# ME461_F28379D.net
KiCad netlist of a schematic drawn in EAGLE
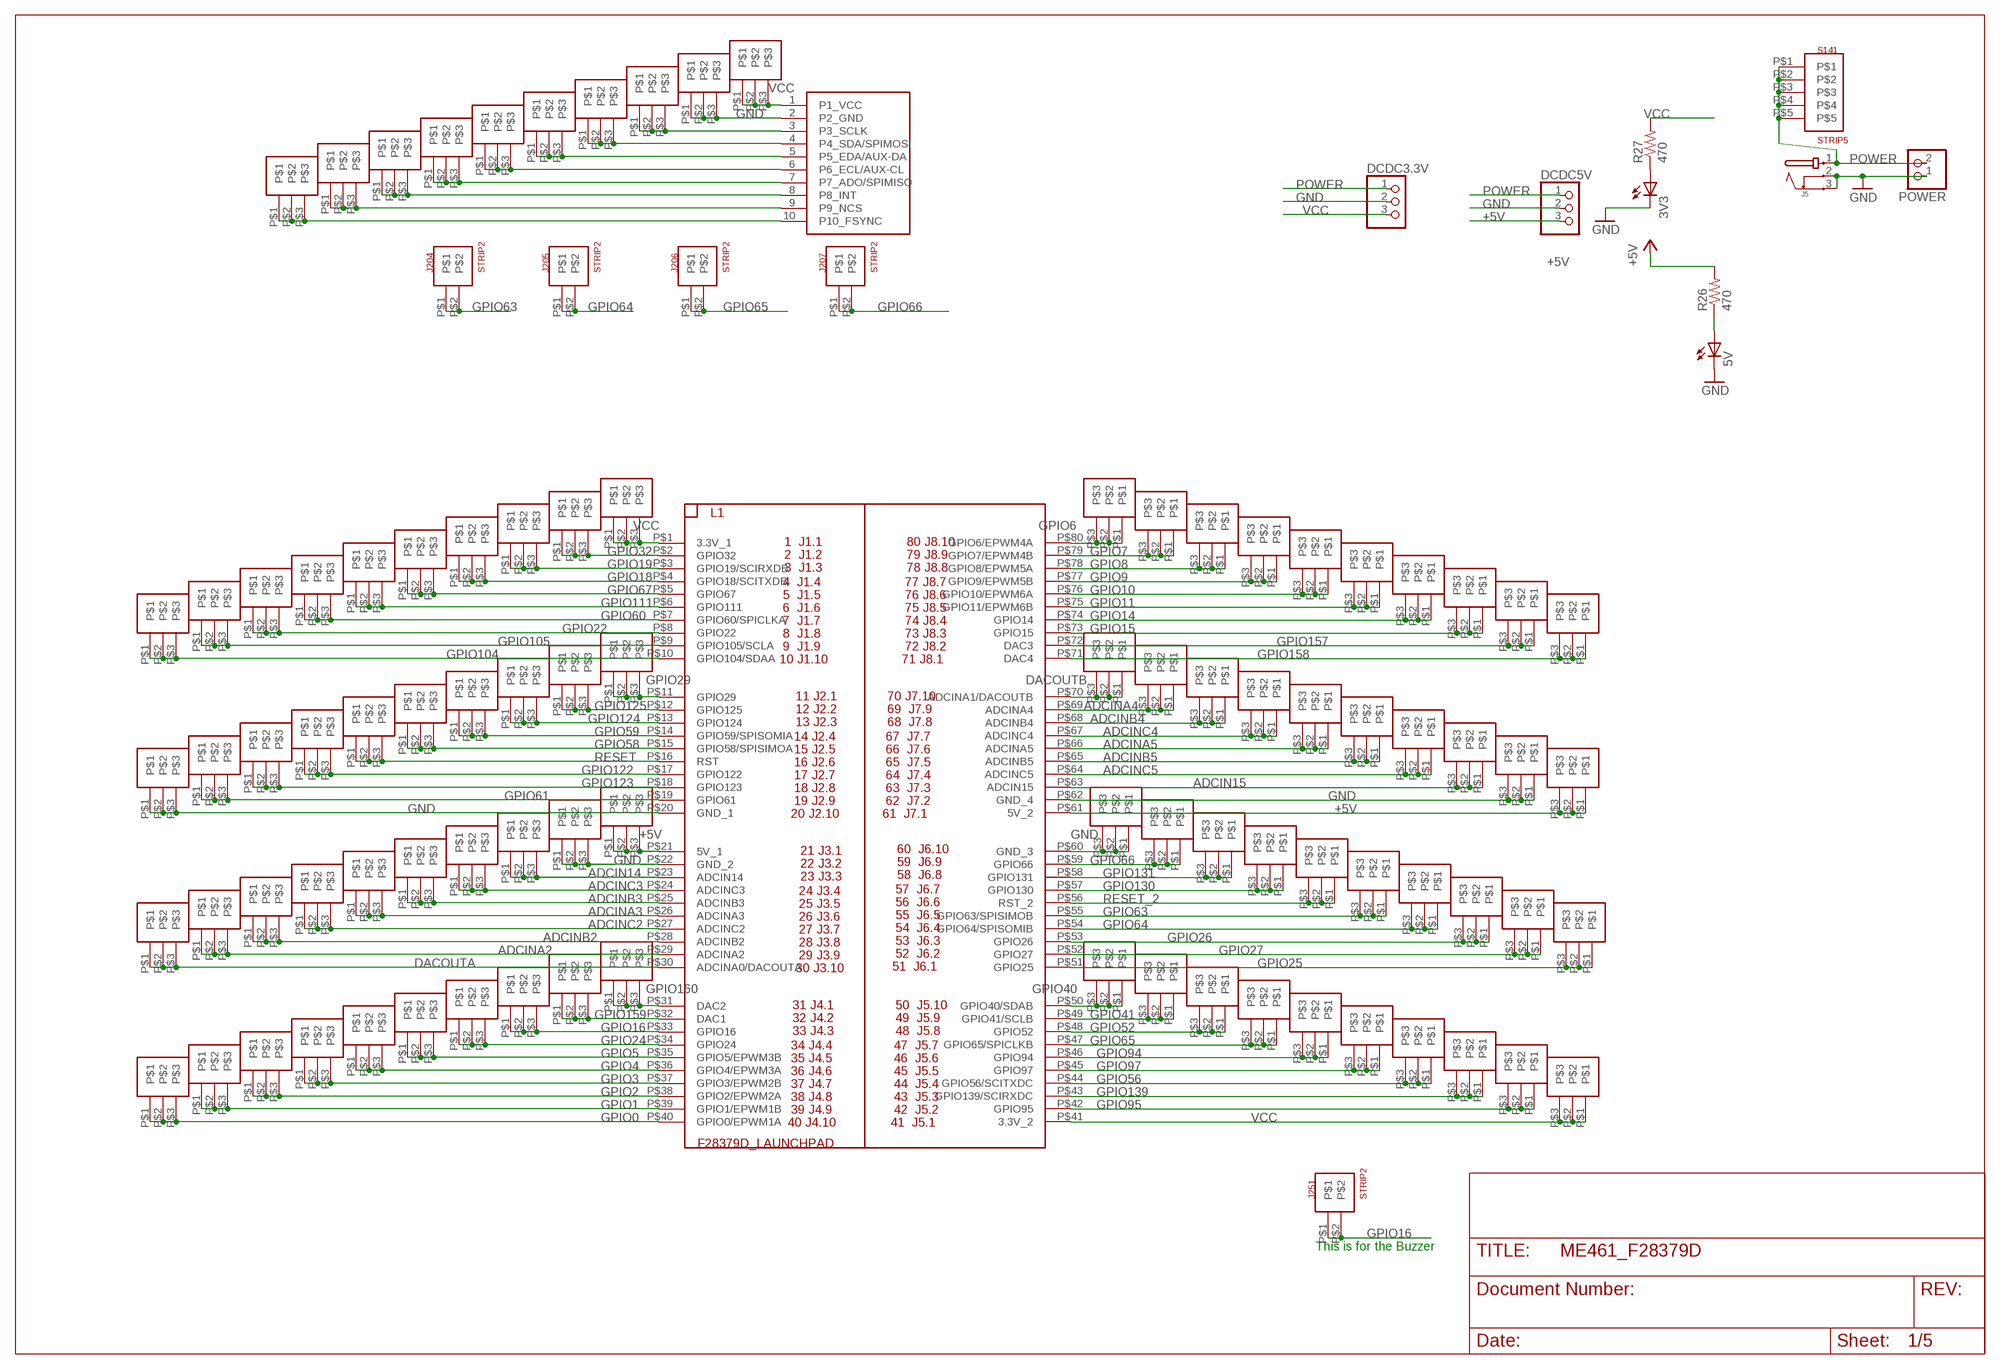
[diagram p0: schematic, sheet 1]
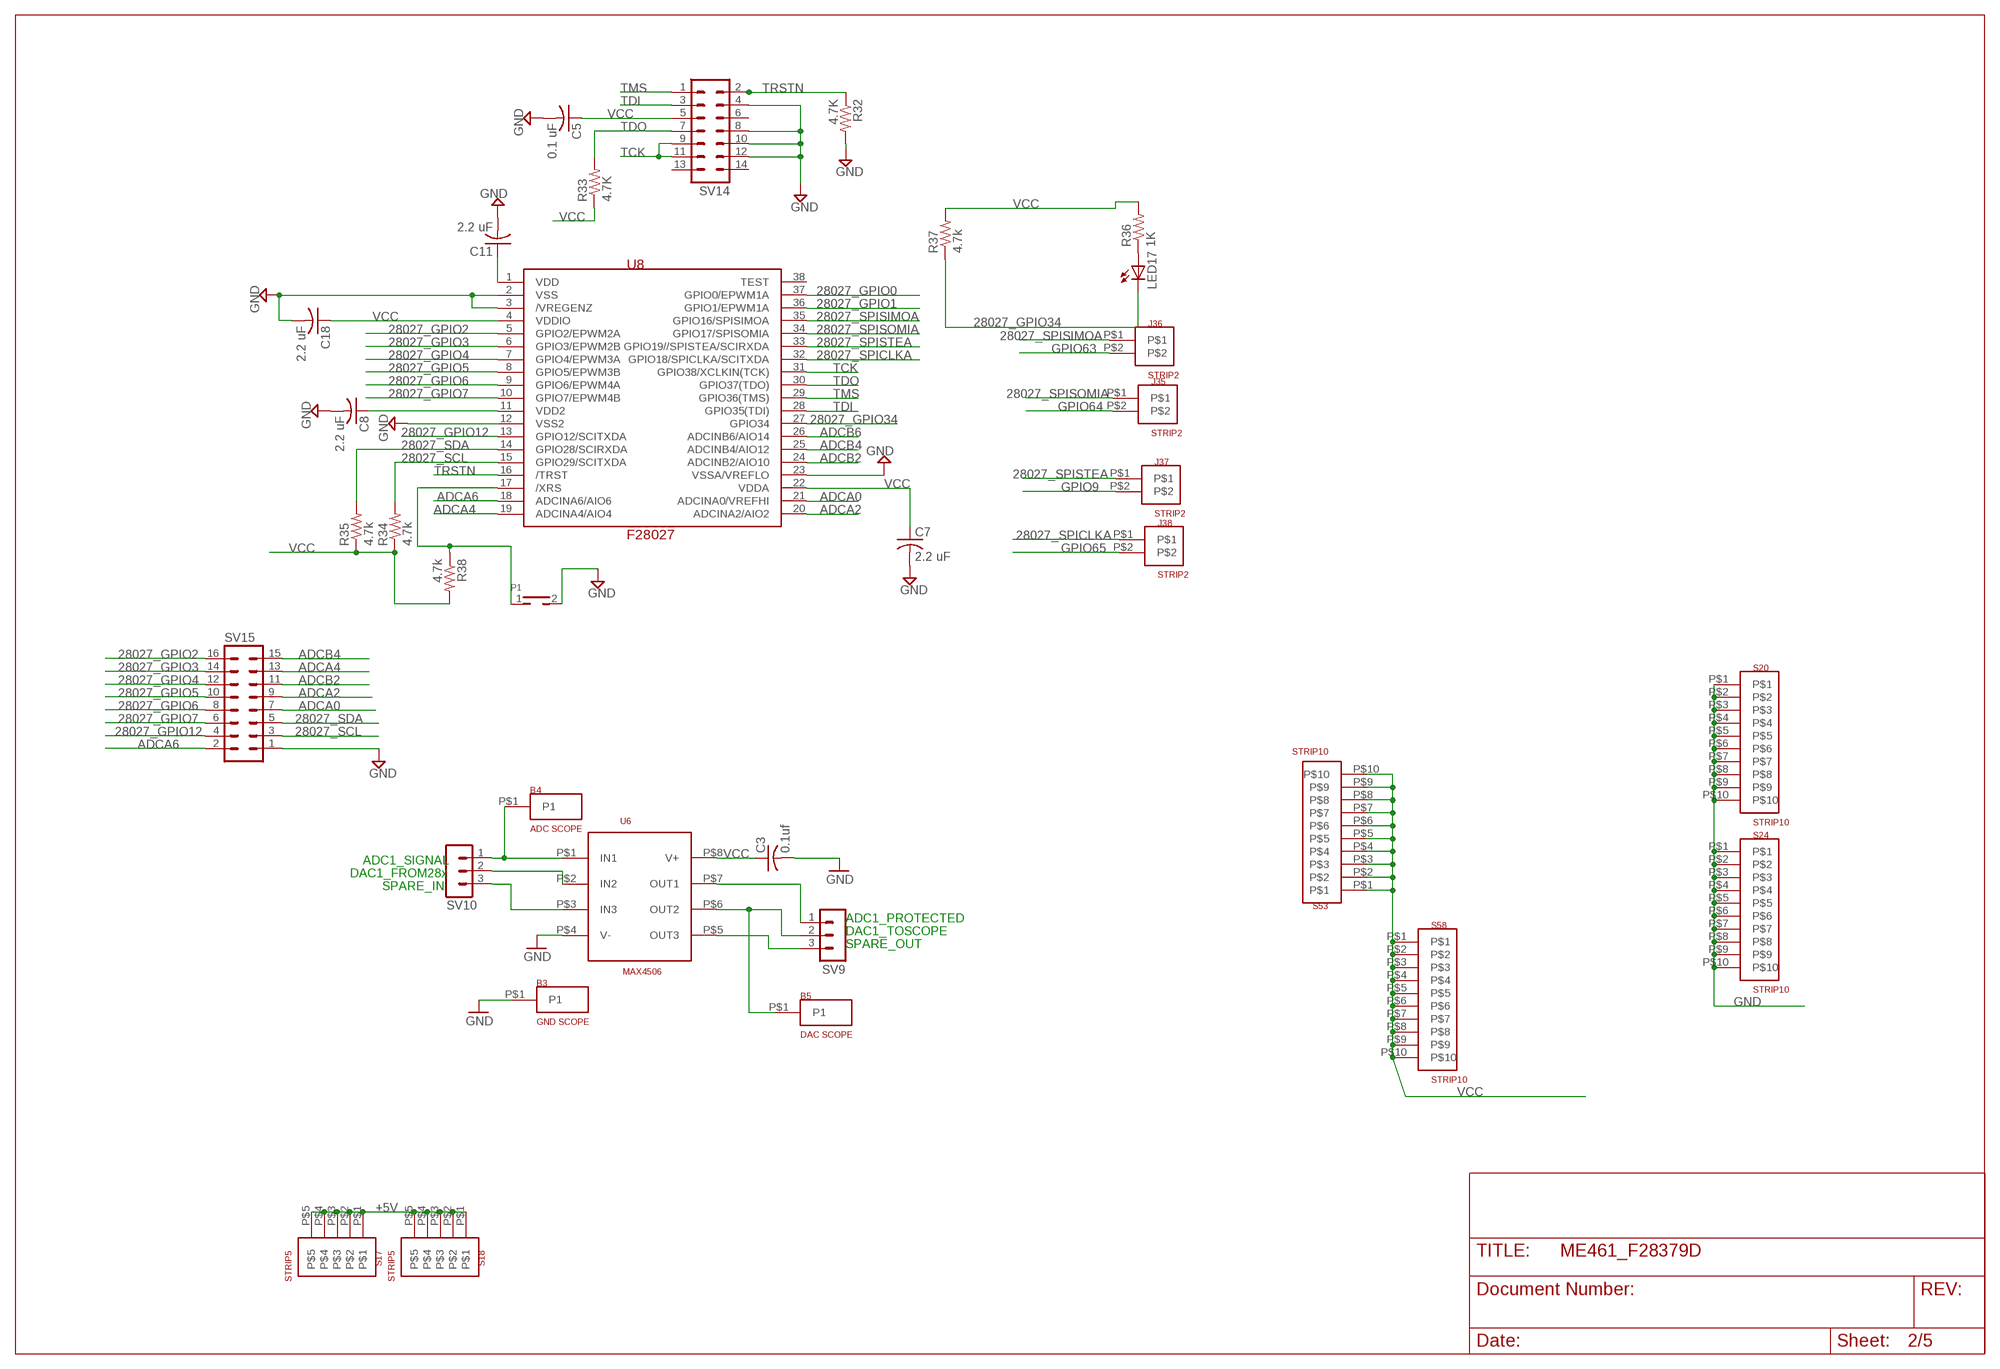
[diagram p1: schematic, sheet 2]
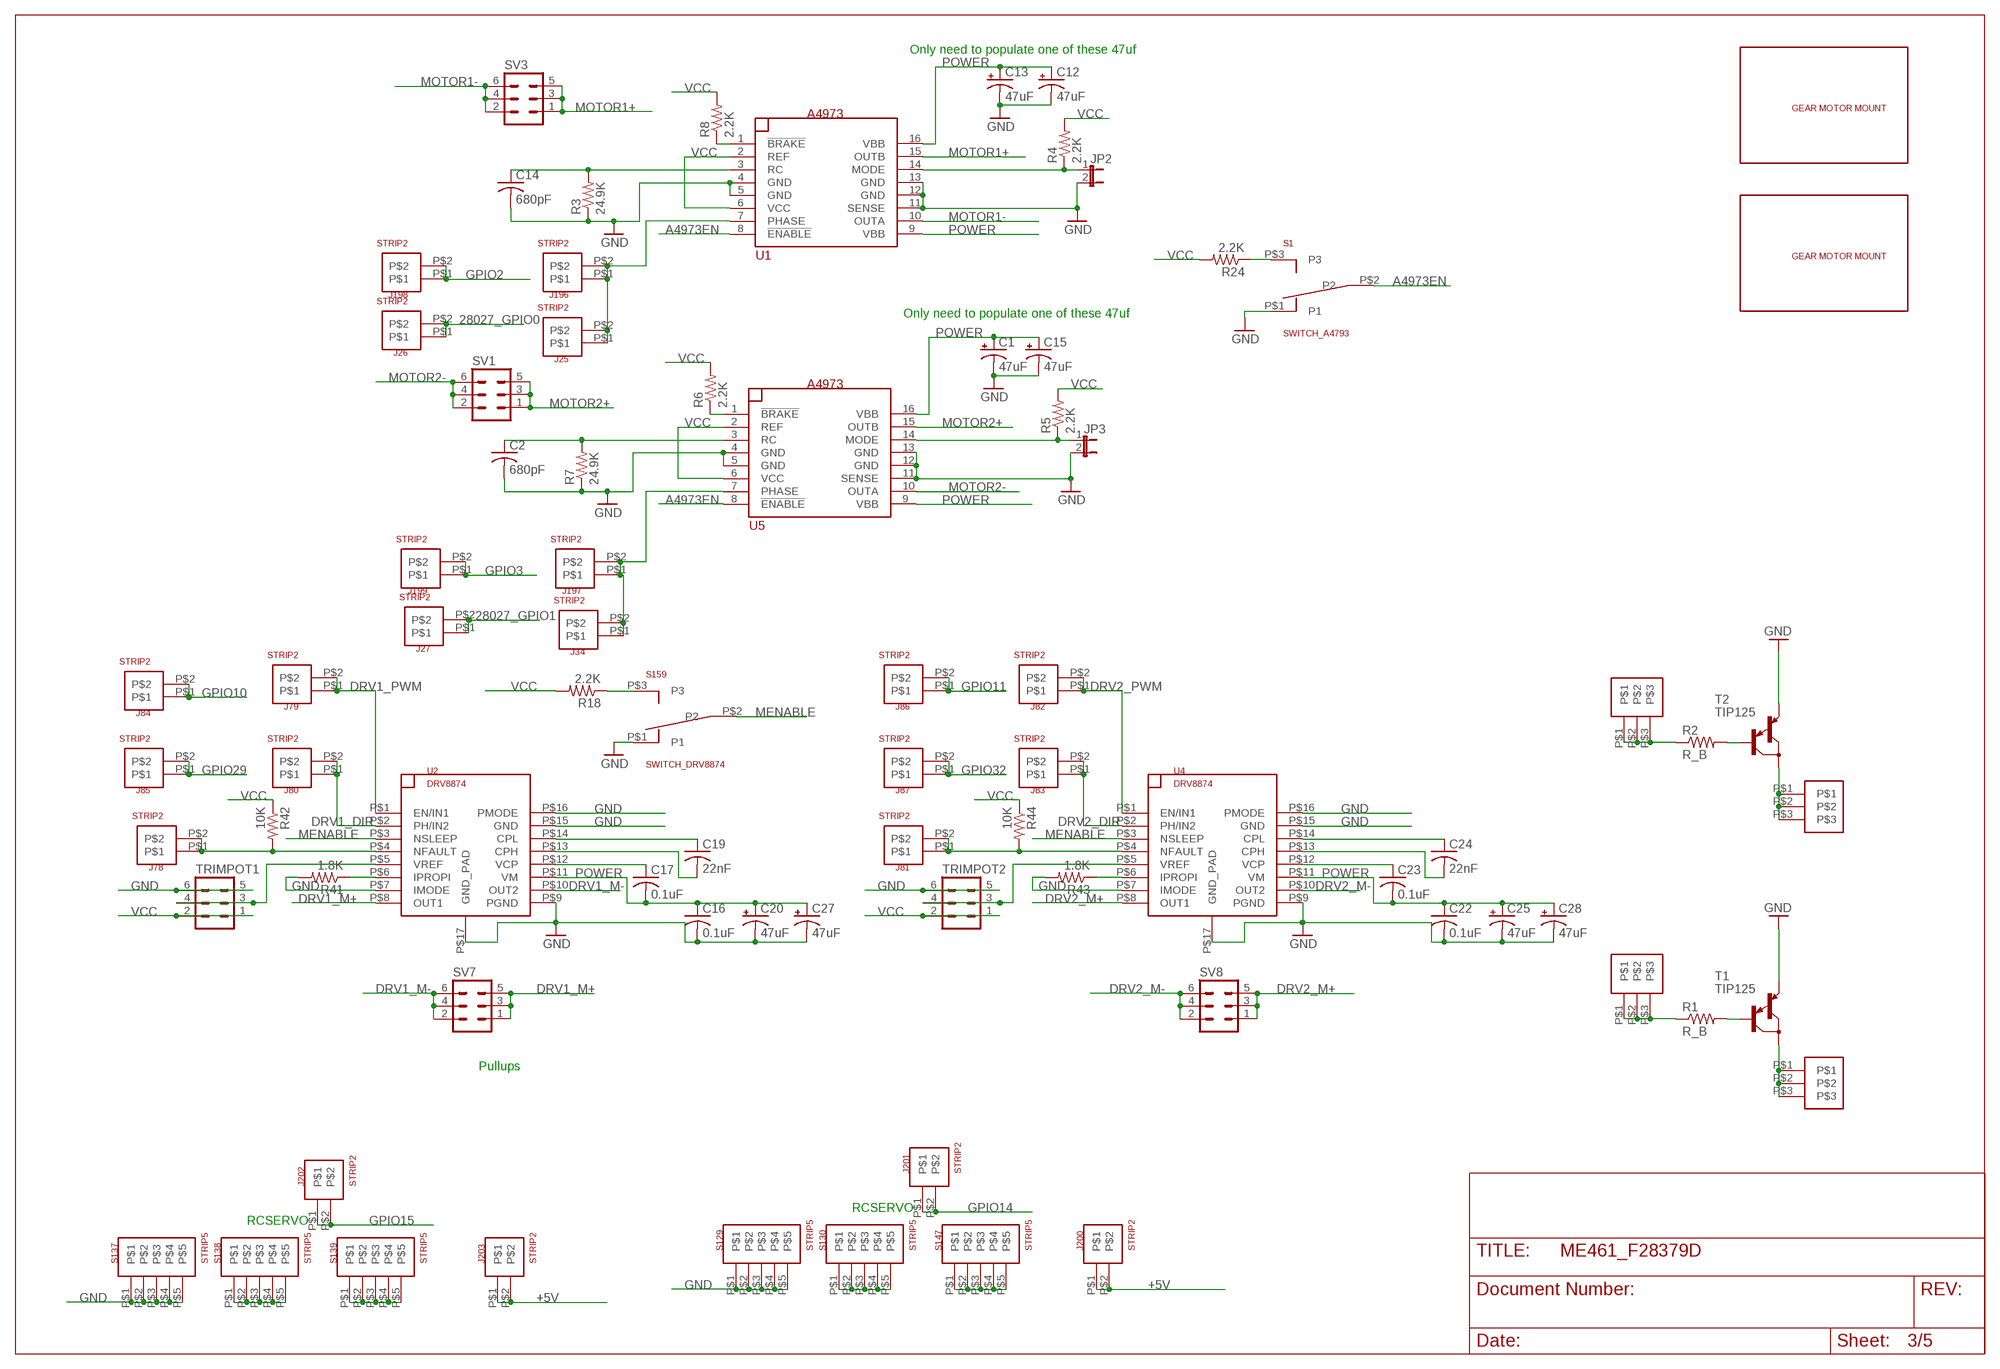
[diagram p2: schematic, sheet 3]
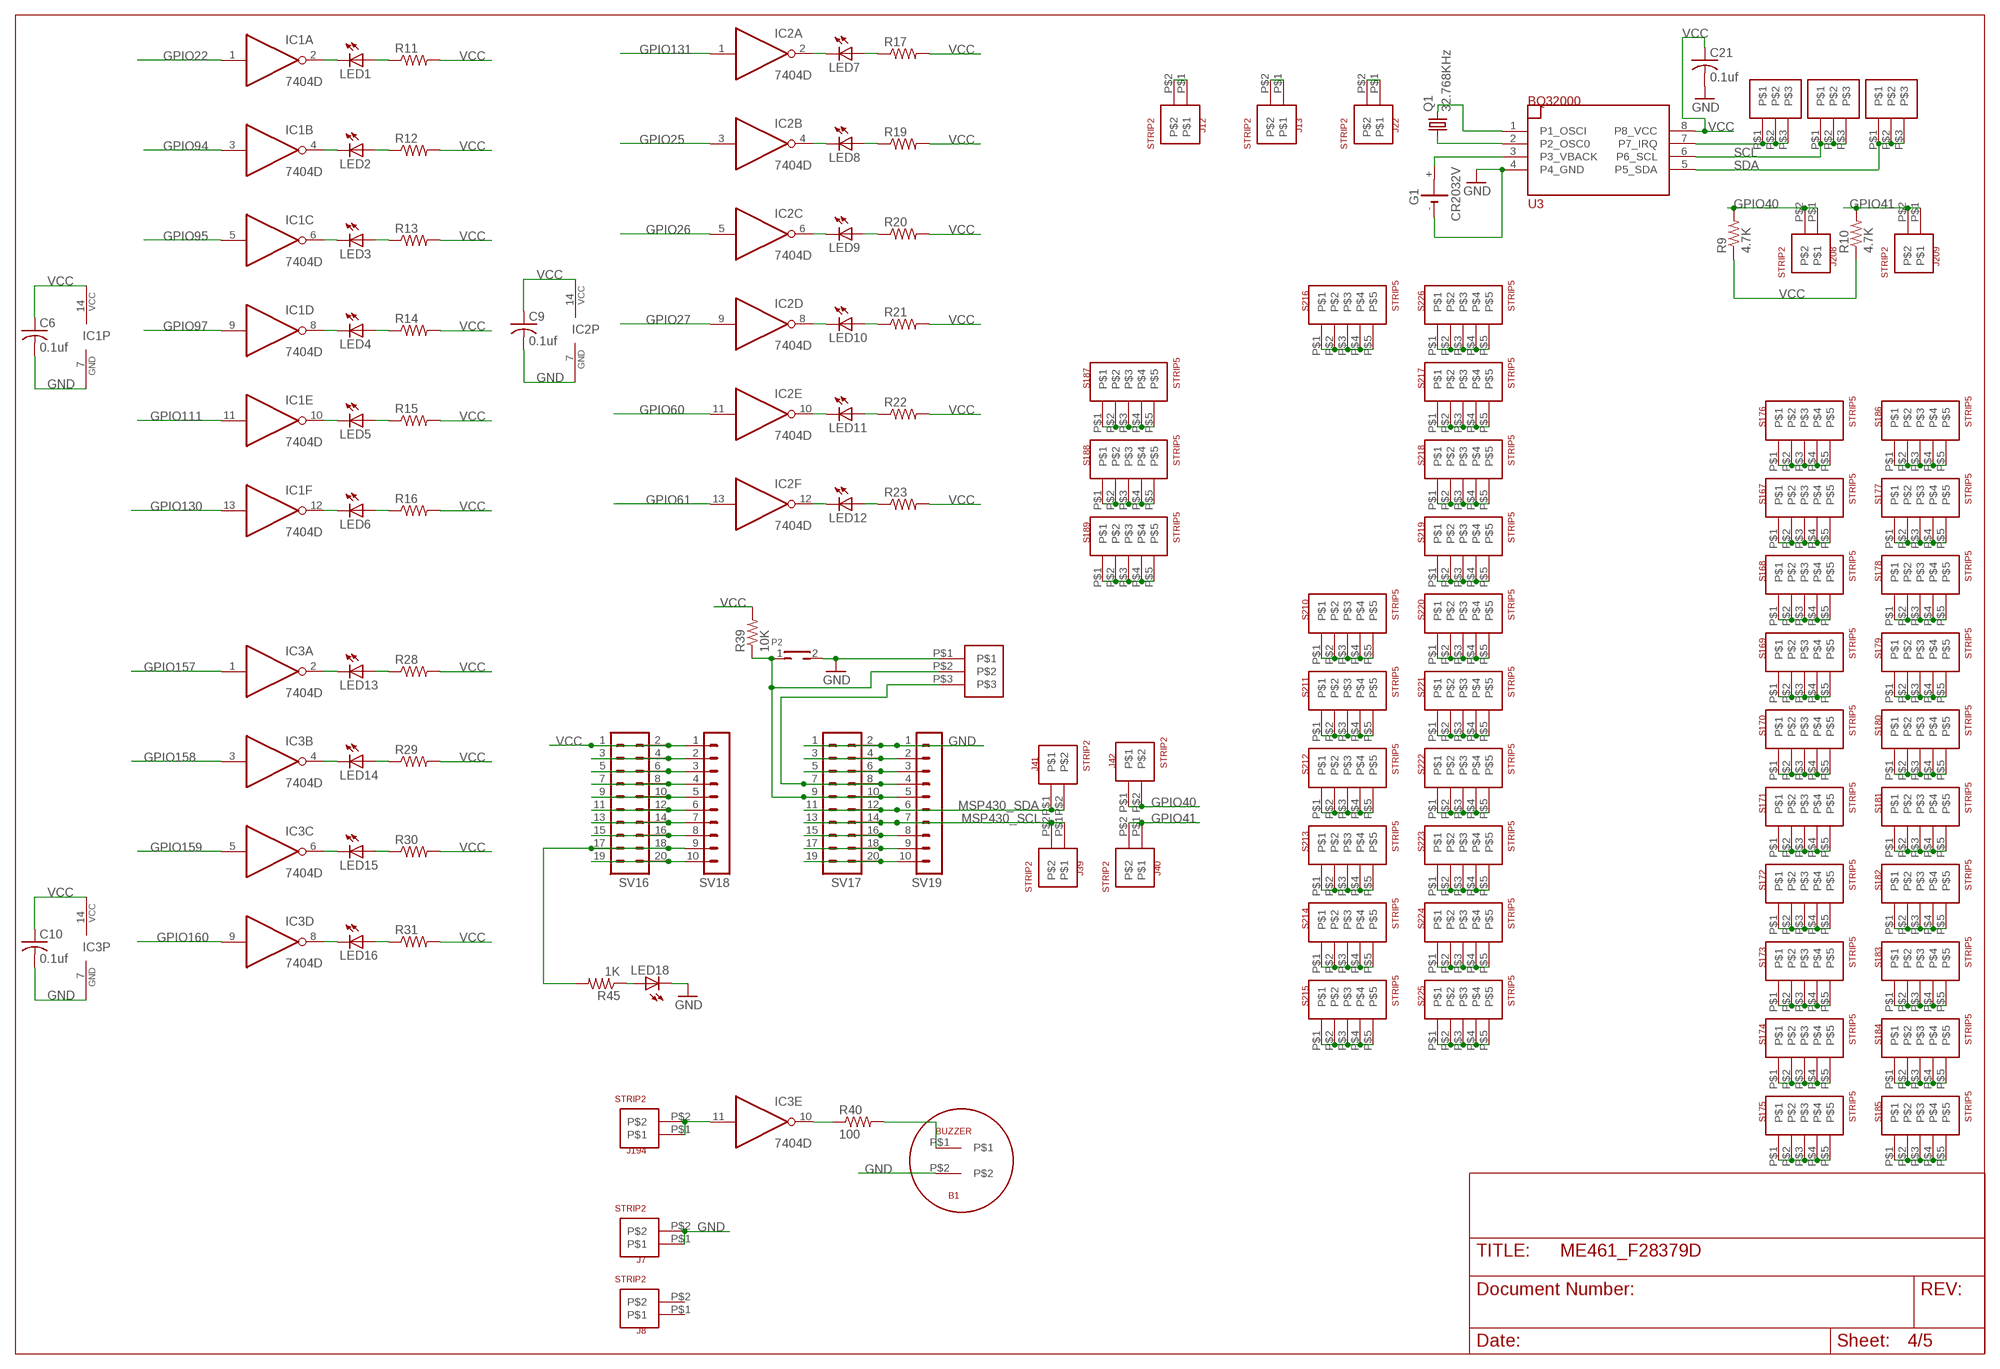
[diagram p3: schematic, sheet 4]
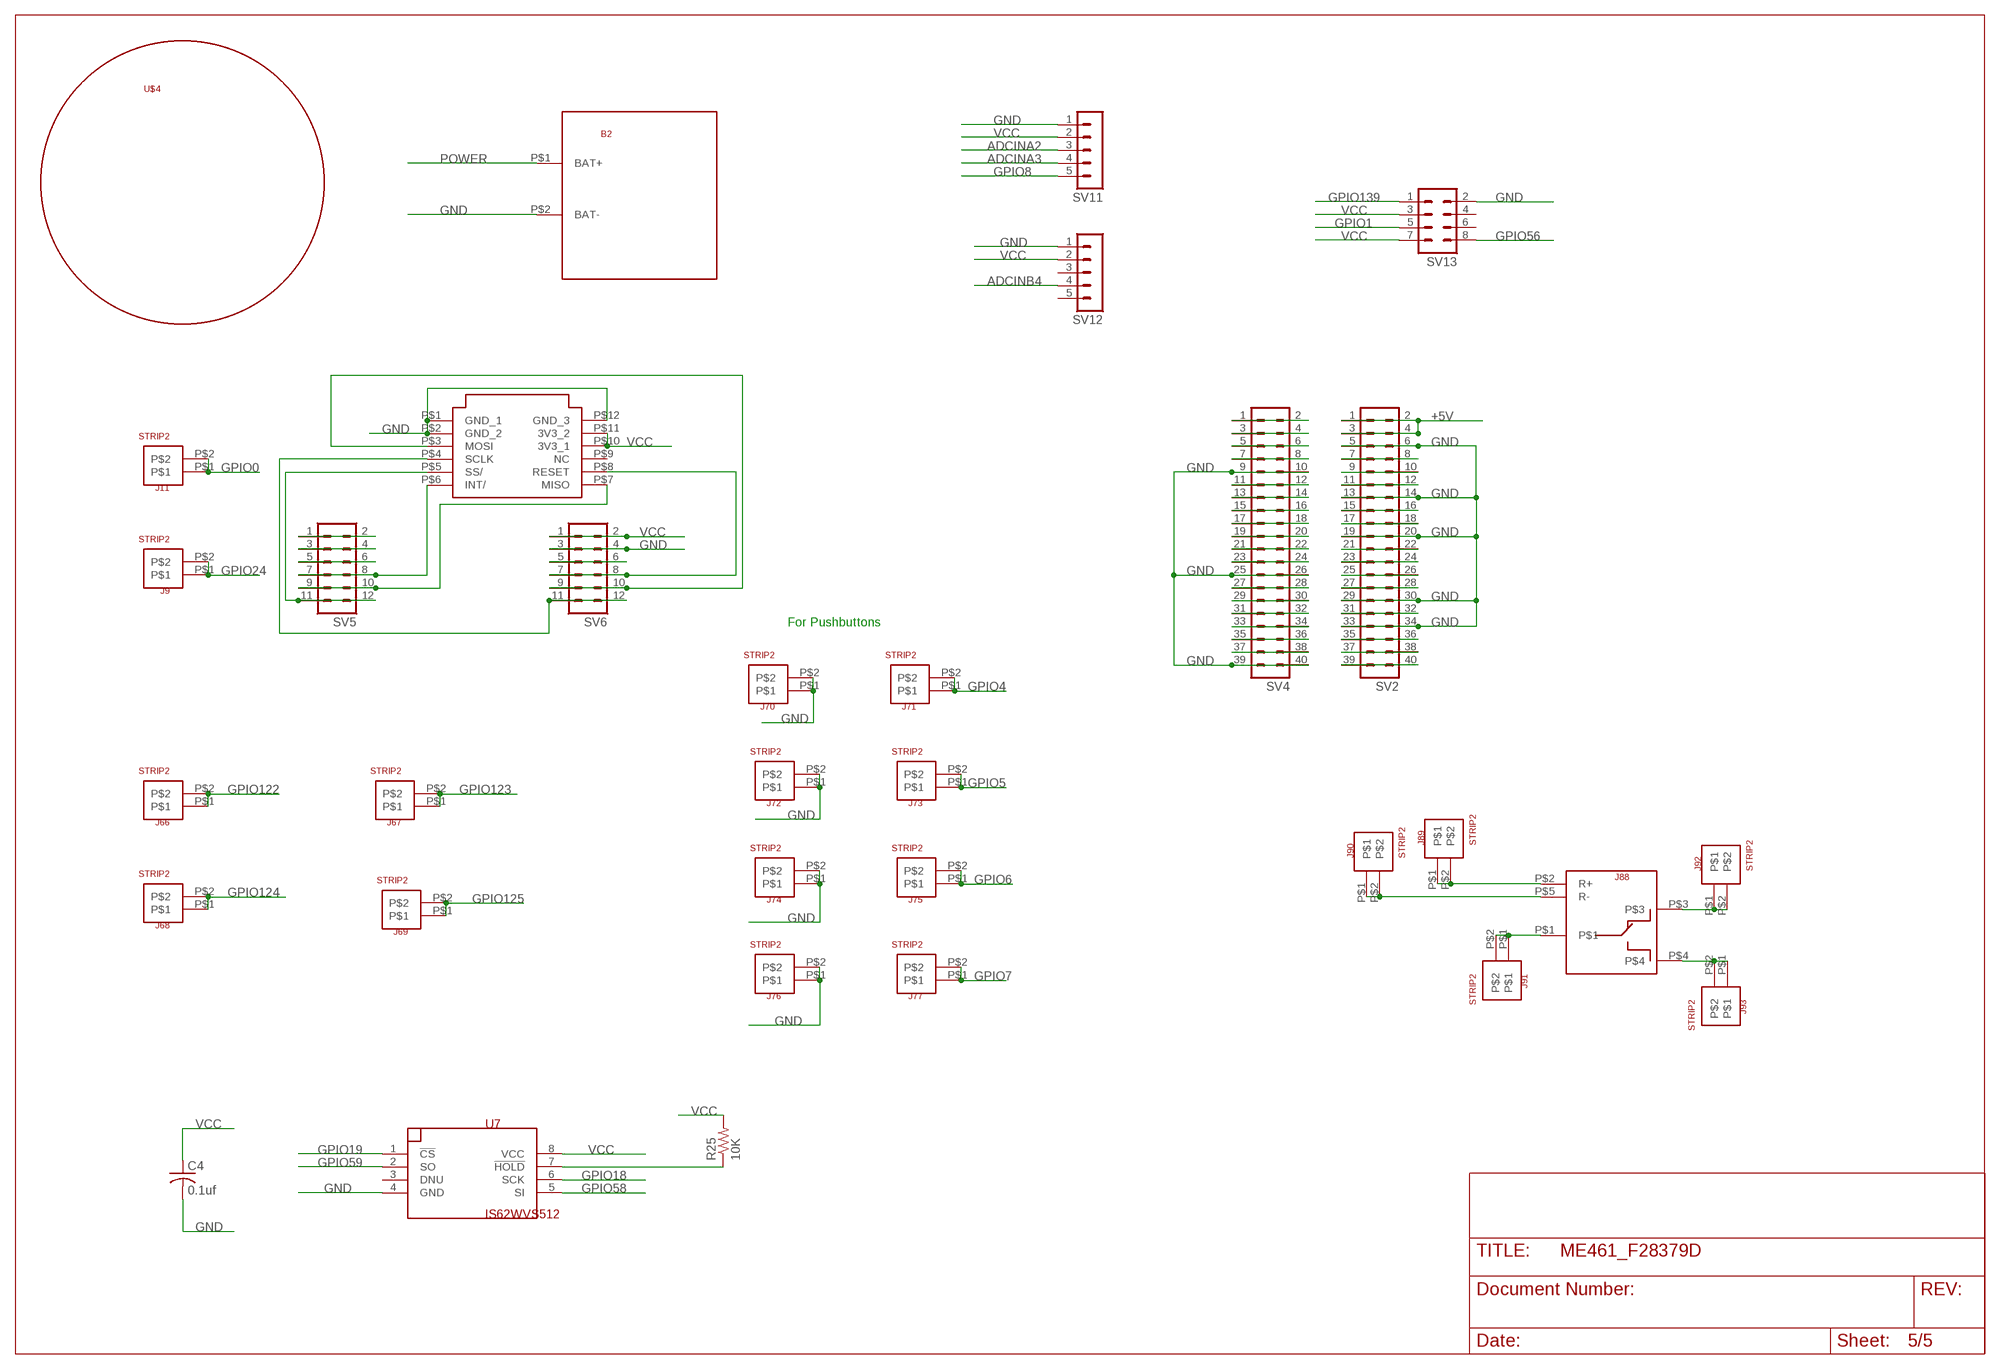
[diagram p4: schematic, sheet 5]

(export (version "E")
  (design (tool "Eeschema 10.0.6"))
  (components
    (comp (ref "B2")
      (value "BATTERY_4AA_HOLDER")
      (footprint "eagle-import:BATTERY_4AA_HOLDER")
      (libsource (lib "eagle-import") (part "BATTERY_4AA_HOLDER"))
    )
    (comp (ref "C4")
      (value "0.1uf")
      (footprint "eagle-import:C1206")
      (libsource (lib "eagle-import") (part "C-USC1206"))
    )
    (comp (ref "ETH1")
      (value "USR_ES1_W5500")
      (footprint "eagle-import:USR_ES1_W5500")
      (libsource (lib "eagle-import") (part "USR_ES1_W5500"))
    )
    (comp (ref "J9")
      (value "STRIP2")
      (footprint "eagle-import:STRIP2")
      (libsource (lib "eagle-import") (part "STRIP2"))
    )
    (comp (ref "J11")
      (value "STRIP2")
      (footprint "eagle-import:STRIP2")
      (libsource (lib "eagle-import") (part "STRIP2"))
    )
    (comp (ref "J66")
      (value "STRIP2")
      (footprint "eagle-import:STRIP2")
      (libsource (lib "eagle-import") (part "STRIP2"))
    )
    (comp (ref "J67")
      (value "STRIP2")
      (footprint "eagle-import:STRIP2")
      (libsource (lib "eagle-import") (part "STRIP2"))
    )
    (comp (ref "J68")
      (value "STRIP2")
      (footprint "eagle-import:STRIP2")
      (libsource (lib "eagle-import") (part "STRIP2"))
    )
    (comp (ref "J69")
      (value "STRIP2")
      (footprint "eagle-import:STRIP2")
      (libsource (lib "eagle-import") (part "STRIP2"))
    )
    (comp (ref "J70")
      (value "STRIP2")
      (footprint "eagle-import:STRIP2")
      (libsource (lib "eagle-import") (part "STRIP2"))
    )
    (comp (ref "J71")
      (value "STRIP2")
      (footprint "eagle-import:STRIP2")
      (libsource (lib "eagle-import") (part "STRIP2"))
    )
    (comp (ref "J72")
      (value "STRIP2")
      (footprint "eagle-import:STRIP2")
      (libsource (lib "eagle-import") (part "STRIP2"))
    )
    (comp (ref "J73")
      (value "STRIP2")
      (footprint "eagle-import:STRIP2")
      (libsource (lib "eagle-import") (part "STRIP2"))
    )
    (comp (ref "J74")
      (value "STRIP2")
      (footprint "eagle-import:STRIP2")
      (libsource (lib "eagle-import") (part "STRIP2"))
    )
    (comp (ref "J75")
      (value "STRIP2")
      (footprint "eagle-import:STRIP2")
      (libsource (lib "eagle-import") (part "STRIP2"))
    )
    (comp (ref "J76")
      (value "STRIP2")
      (footprint "eagle-import:STRIP2")
      (libsource (lib "eagle-import") (part "STRIP2"))
    )
    (comp (ref "J77")
      (value "STRIP2")
      (footprint "eagle-import:STRIP2")
      (libsource (lib "eagle-import") (part "STRIP2"))
    )
    (comp (ref "J88")
      (value "RELAY_JQC-3F_5V")
      (footprint "eagle-import:RELAY_JQC-3F_5V")
      (libsource (lib "eagle-import") (part "RELAY_JQC-3F_5V"))
    )
    (comp (ref "J89")
      (value "STRIP2")
      (footprint "eagle-import:STRIP2")
      (libsource (lib "eagle-import") (part "STRIP2"))
    )
    (comp (ref "J90")
      (value "STRIP2")
      (footprint "eagle-import:STRIP2")
      (libsource (lib "eagle-import") (part "STRIP2"))
    )
    (comp (ref "J91")
      (value "STRIP2")
      (footprint "eagle-import:STRIP2")
      (libsource (lib "eagle-import") (part "STRIP2"))
    )
    (comp (ref "J92")
      (value "STRIP2")
      (footprint "eagle-import:STRIP2")
      (libsource (lib "eagle-import") (part "STRIP2"))
    )
    (comp (ref "J93")
      (value "STRIP2")
      (footprint "eagle-import:STRIP2")
      (libsource (lib "eagle-import") (part "STRIP2"))
    )
    (comp (ref "R25")
      (value "10K")
      (footprint "eagle-import:M1206")
      (libsource (lib "eagle-import") (part "R-US_M1206"))
    )
    (comp (ref "SV2")
      (value "MA20-2")
      (footprint "eagle-import:MA20-2")
      (libsource (lib "eagle-import") (part "MA20-2"))
    )
    (comp (ref "SV4")
      (value "MA20-2")
      (footprint "eagle-import:MA20-2")
      (libsource (lib "eagle-import") (part "MA20-2"))
    )
    (comp (ref "SV5")
      (value "MA06-2")
      (footprint "eagle-import:MA06-2")
      (libsource (lib "eagle-import") (part "MA06-2"))
    )
    (comp (ref "SV6")
      (value "MA06-2")
      (footprint "eagle-import:MA06-2")
      (libsource (lib "eagle-import") (part "MA06-2"))
    )
    (comp (ref "SV11")
      (value "MA05-1")
      (footprint "eagle-import:MA05-1")
      (libsource (lib "eagle-import") (part "MA05-1"))
    )
    (comp (ref "SV12")
      (value "MA05-1")
      (footprint "eagle-import:MA05-1")
      (libsource (lib "eagle-import") (part "MA05-1"))
    )
    (comp (ref "SV13")
      (value "MA04-2")
      (footprint "eagle-import:MA04-2")
      (libsource (lib "eagle-import") (part "MA04-2"))
    )
    (comp (ref "U$4")
      (value "CASTERWHEEL")
      (footprint "eagle-import:CASTERWHEEL")
      (libsource (lib "eagle-import") (part "CASTERWHEEL"))
    )
    (comp (ref "U7")
      (value "IS62WVS512")
      (footprint "eagle-import:SO08")
      (libsource (lib "eagle-import") (part "IS62WVS512"))
    )
    (comp (ref "3V3")
      (value "LEDCHIPLED_1206")
      (footprint "eagle-import:CHIPLED_1206")
      (libsource (lib "eagle-import") (part "LEDCHIPLED_1206"))
    )
    (comp (ref "5V")
      (value "LEDCHIPLED_1206")
      (footprint "eagle-import:CHIPLED_1206")
      (libsource (lib "eagle-import") (part "LEDCHIPLED_1206"))
    )
    (comp (ref "DCDC3.3V")
      (value "PINHD-1X3")
      (footprint "eagle-import:1X03")
      (libsource (lib "eagle-import") (part "PINHD-1X3"))
    )
    (comp (ref "DCDC5V")
      (value "PINHD-1X3")
      (footprint "eagle-import:1X03")
      (libsource (lib "eagle-import") (part "PINHD-1X3"))
    )
    (comp (ref "J5")
      (value "JACK-PMS")
      (footprint "eagle-import:JACK-PMS")
      (libsource (lib "eagle-import") (part "JACK-PMS"))
    )
    (comp (ref "J10")
      (value "STRIP3")
      (footprint "eagle-import:STRIP3")
      (libsource (lib "eagle-import") (part "STRIP3"))
    )
    (comp (ref "J14")
      (value "STRIP3")
      (footprint "eagle-import:STRIP3")
      (libsource (lib "eagle-import") (part "STRIP3"))
    )
    (comp (ref "J15")
      (value "STRIP3")
      (footprint "eagle-import:STRIP3")
      (libsource (lib "eagle-import") (part "STRIP3"))
    )
    (comp (ref "J16")
      (value "STRIP3")
      (footprint "eagle-import:STRIP3")
      (libsource (lib "eagle-import") (part "STRIP3"))
    )
    (comp (ref "J17")
      (value "STRIP3")
      (footprint "eagle-import:STRIP3")
      (libsource (lib "eagle-import") (part "STRIP3"))
    )
    (comp (ref "J18")
      (value "STRIP3")
      (footprint "eagle-import:STRIP3")
      (libsource (lib "eagle-import") (part "STRIP3"))
    )
    (comp (ref "J19")
      (value "STRIP3")
      (footprint "eagle-import:STRIP3")
      (libsource (lib "eagle-import") (part "STRIP3"))
    )
    (comp (ref "J20")
      (value "STRIP3")
      (footprint "eagle-import:STRIP3")
      (libsource (lib "eagle-import") (part "STRIP3"))
    )
    (comp (ref "J21")
      (value "STRIP3")
      (footprint "eagle-import:STRIP3")
      (libsource (lib "eagle-import") (part "STRIP3"))
    )
    (comp (ref "J28")
      (value "STRIP3")
      (footprint "eagle-import:STRIP3")
      (libsource (lib "eagle-import") (part "STRIP3"))
    )
    (comp (ref "J29")
      (value "STRIP3")
      (footprint "eagle-import:STRIP3")
      (libsource (lib "eagle-import") (part "STRIP3"))
    )
    (comp (ref "J30")
      (value "STRIP3")
      (footprint "eagle-import:STRIP3")
      (libsource (lib "eagle-import") (part "STRIP3"))
    )
    (comp (ref "J31")
      (value "STRIP3")
      (footprint "eagle-import:STRIP3")
      (libsource (lib "eagle-import") (part "STRIP3"))
    )
    (comp (ref "J32")
      (value "STRIP3")
      (footprint "eagle-import:STRIP3")
      (libsource (lib "eagle-import") (part "STRIP3"))
    )
    (comp (ref "J33")
      (value "STRIP3")
      (footprint "eagle-import:STRIP3")
      (libsource (lib "eagle-import") (part "STRIP3"))
    )
    (comp (ref "J98")
      (value "STRIP3")
      (footprint "eagle-import:STRIP3")
      (libsource (lib "eagle-import") (part "STRIP3"))
    )
    (comp (ref "J99")
      (value "STRIP3")
      (footprint "eagle-import:STRIP3")
      (libsource (lib "eagle-import") (part "STRIP3"))
    )
    (comp (ref "J100")
      (value "STRIP3")
      (footprint "eagle-import:STRIP3")
      (libsource (lib "eagle-import") (part "STRIP3"))
    )
    (comp (ref "J101")
      (value "STRIP3")
      (footprint "eagle-import:STRIP3")
      (libsource (lib "eagle-import") (part "STRIP3"))
    )
    (comp (ref "J102")
      (value "STRIP3")
      (footprint "eagle-import:STRIP3")
      (libsource (lib "eagle-import") (part "STRIP3"))
    )
    (comp (ref "J103")
      (value "STRIP3")
      (footprint "eagle-import:STRIP3")
      (libsource (lib "eagle-import") (part "STRIP3"))
    )
    (comp (ref "J104")
      (value "STRIP3")
      (footprint "eagle-import:STRIP3")
      (libsource (lib "eagle-import") (part "STRIP3"))
    )
    (comp (ref "J105")
      (value "STRIP3")
      (footprint "eagle-import:STRIP3")
      (libsource (lib "eagle-import") (part "STRIP3"))
    )
    (comp (ref "J106")
      (value "STRIP3")
      (footprint "eagle-import:STRIP3")
      (libsource (lib "eagle-import") (part "STRIP3"))
    )
    (comp (ref "J107")
      (value "STRIP3")
      (footprint "eagle-import:STRIP3")
      (libsource (lib "eagle-import") (part "STRIP3"))
    )
    (comp (ref "J108")
      (value "STRIP3")
      (footprint "eagle-import:STRIP3")
      (libsource (lib "eagle-import") (part "STRIP3"))
    )
    (comp (ref "J109")
      (value "STRIP3")
      (footprint "eagle-import:STRIP3")
      (libsource (lib "eagle-import") (part "STRIP3"))
    )
    (comp (ref "J110")
      (value "STRIP3")
      (footprint "eagle-import:STRIP3")
      (libsource (lib "eagle-import") (part "STRIP3"))
    )
    (comp (ref "J111")
      (value "STRIP3")
      (footprint "eagle-import:STRIP3")
      (libsource (lib "eagle-import") (part "STRIP3"))
    )
    (comp (ref "J112")
      (value "STRIP3")
      (footprint "eagle-import:STRIP3")
      (libsource (lib "eagle-import") (part "STRIP3"))
    )
    (comp (ref "J113")
      (value "STRIP3")
      (footprint "eagle-import:STRIP3")
      (libsource (lib "eagle-import") (part "STRIP3"))
    )
    (comp (ref "J114")
      (value "STRIP3")
      (footprint "eagle-import:STRIP3")
      (libsource (lib "eagle-import") (part "STRIP3"))
    )
    (comp (ref "J115")
      (value "STRIP3")
      (footprint "eagle-import:STRIP3")
      (libsource (lib "eagle-import") (part "STRIP3"))
    )
    (comp (ref "J116")
      (value "STRIP3")
      (footprint "eagle-import:STRIP3")
      (libsource (lib "eagle-import") (part "STRIP3"))
    )
    (comp (ref "J117")
      (value "STRIP3")
      (footprint "eagle-import:STRIP3")
      (libsource (lib "eagle-import") (part "STRIP3"))
    )
    (comp (ref "J118")
      (value "STRIP3")
      (footprint "eagle-import:STRIP3")
      (libsource (lib "eagle-import") (part "STRIP3"))
    )
    (comp (ref "J119")
      (value "STRIP3")
      (footprint "eagle-import:STRIP3")
      (libsource (lib "eagle-import") (part "STRIP3"))
    )
    (comp (ref "J120")
      (value "STRIP3")
      (footprint "eagle-import:STRIP3")
      (libsource (lib "eagle-import") (part "STRIP3"))
    )
    (comp (ref "J121")
      (value "STRIP3")
      (footprint "eagle-import:STRIP3")
      (libsource (lib "eagle-import") (part "STRIP3"))
    )
    (comp (ref "J122")
      (value "STRIP3")
      (footprint "eagle-import:STRIP3")
      (libsource (lib "eagle-import") (part "STRIP3"))
    )
    (comp (ref "J123")
      (value "STRIP3")
      (footprint "eagle-import:STRIP3")
      (libsource (lib "eagle-import") (part "STRIP3"))
    )
    (comp (ref "J124")
      (value "STRIP3")
      (footprint "eagle-import:STRIP3")
      (libsource (lib "eagle-import") (part "STRIP3"))
    )
    (comp (ref "J125")
      (value "STRIP3")
      (footprint "eagle-import:STRIP3")
      (libsource (lib "eagle-import") (part "STRIP3"))
    )
    (comp (ref "J126")
      (value "STRIP3")
      (footprint "eagle-import:STRIP3")
      (libsource (lib "eagle-import") (part "STRIP3"))
    )
    (comp (ref "J127")
      (value "STRIP3")
      (footprint "eagle-import:STRIP3")
      (libsource (lib "eagle-import") (part "STRIP3"))
    )
    (comp (ref "J128")
      (value "STRIP3")
      (footprint "eagle-import:STRIP3")
      (libsource (lib "eagle-import") (part "STRIP3"))
    )
    (comp (ref "J129")
      (value "STRIP3")
      (footprint "eagle-import:STRIP3")
      (libsource (lib "eagle-import") (part "STRIP3"))
    )
    (comp (ref "J130")
      (value "STRIP3")
      (footprint "eagle-import:STRIP3")
      (libsource (lib "eagle-import") (part "STRIP3"))
    )
    (comp (ref "J131")
      (value "STRIP3")
      (footprint "eagle-import:STRIP3")
      (libsource (lib "eagle-import") (part "STRIP3"))
    )
    (comp (ref "J132")
      (value "STRIP3")
      (footprint "eagle-import:STRIP3")
      (libsource (lib "eagle-import") (part "STRIP3"))
    )
    (comp (ref "J133")
      (value "STRIP3")
      (footprint "eagle-import:STRIP3")
      (libsource (lib "eagle-import") (part "STRIP3"))
    )
    (comp (ref "J134")
      (value "STRIP3")
      (footprint "eagle-import:STRIP3")
      (libsource (lib "eagle-import") (part "STRIP3"))
    )
    (comp (ref "J135")
      (value "STRIP3")
      (footprint "eagle-import:STRIP3")
      (libsource (lib "eagle-import") (part "STRIP3"))
    )
    (comp (ref "J136")
      (value "STRIP3")
      (footprint "eagle-import:STRIP3")
      (libsource (lib "eagle-import") (part "STRIP3"))
    )
    (comp (ref "J137")
      (value "STRIP3")
      (footprint "eagle-import:STRIP3")
      (libsource (lib "eagle-import") (part "STRIP3"))
    )
    (comp (ref "J138")
      (value "STRIP3")
      (footprint "eagle-import:STRIP3")
      (libsource (lib "eagle-import") (part "STRIP3"))
    )
    (comp (ref "J139")
      (value "STRIP3")
      (footprint "eagle-import:STRIP3")
      (libsource (lib "eagle-import") (part "STRIP3"))
    )
    (comp (ref "J140")
      (value "STRIP3")
      (footprint "eagle-import:STRIP3")
      (libsource (lib "eagle-import") (part "STRIP3"))
    )
    (comp (ref "J141")
      (value "STRIP3")
      (footprint "eagle-import:STRIP3")
      (libsource (lib "eagle-import") (part "STRIP3"))
    )
    (comp (ref "J142")
      (value "STRIP3")
      (footprint "eagle-import:STRIP3")
      (libsource (lib "eagle-import") (part "STRIP3"))
    )
    (comp (ref "J143")
      (value "STRIP3")
      (footprint "eagle-import:STRIP3")
      (libsource (lib "eagle-import") (part "STRIP3"))
    )
    (comp (ref "J144")
      (value "STRIP3")
      (footprint "eagle-import:STRIP3")
      (libsource (lib "eagle-import") (part "STRIP3"))
    )
    (comp (ref "J145")
      (value "STRIP3")
      (footprint "eagle-import:STRIP3")
      (libsource (lib "eagle-import") (part "STRIP3"))
    )
    (comp (ref "J146")
      (value "STRIP3")
      (footprint "eagle-import:STRIP3")
      (libsource (lib "eagle-import") (part "STRIP3"))
    )
    (comp (ref "J147")
      (value "STRIP3")
      (footprint "eagle-import:STRIP3")
      (libsource (lib "eagle-import") (part "STRIP3"))
    )
    (comp (ref "J148")
      (value "STRIP3")
      (footprint "eagle-import:STRIP3")
      (libsource (lib "eagle-import") (part "STRIP3"))
    )
    (comp (ref "J149")
      (value "STRIP3")
      (footprint "eagle-import:STRIP3")
      (libsource (lib "eagle-import") (part "STRIP3"))
    )
    (comp (ref "J150")
      (value "STRIP3")
      (footprint "eagle-import:STRIP3")
      (libsource (lib "eagle-import") (part "STRIP3"))
    )
    (comp (ref "J151")
      (value "STRIP3")
      (footprint "eagle-import:STRIP3")
      (libsource (lib "eagle-import") (part "STRIP3"))
    )
    (comp (ref "J152")
      (value "STRIP3")
      (footprint "eagle-import:STRIP3")
      (libsource (lib "eagle-import") (part "STRIP3"))
    )
    (comp (ref "J153")
      (value "STRIP3")
      (footprint "eagle-import:STRIP3")
      (libsource (lib "eagle-import") (part "STRIP3"))
    )
    (comp (ref "J154")
      (value "STRIP3")
      (footprint "eagle-import:STRIP3")
      (libsource (lib "eagle-import") (part "STRIP3"))
    )
    (comp (ref "J155")
      (value "STRIP3")
      (footprint "eagle-import:STRIP3")
      (libsource (lib "eagle-import") (part "STRIP3"))
    )
    (comp (ref "J156")
      (value "STRIP3")
      (footprint "eagle-import:STRIP3")
      (libsource (lib "eagle-import") (part "STRIP3"))
    )
    (comp (ref "J157")
      (value "STRIP3")
      (footprint "eagle-import:STRIP3")
      (libsource (lib "eagle-import") (part "STRIP3"))
    )
    (comp (ref "J158")
      (value "STRIP3")
      (footprint "eagle-import:STRIP3")
      (libsource (lib "eagle-import") (part "STRIP3"))
    )
    (comp (ref "J159")
      (value "STRIP3")
      (footprint "eagle-import:STRIP3")
      (libsource (lib "eagle-import") (part "STRIP3"))
    )
    (comp (ref "J160")
      (value "STRIP3")
      (footprint "eagle-import:STRIP3")
      (libsource (lib "eagle-import") (part "STRIP3"))
    )
    (comp (ref "J161")
      (value "STRIP3")
      (footprint "eagle-import:STRIP3")
      (libsource (lib "eagle-import") (part "STRIP3"))
    )
    (comp (ref "J162")
      (value "STRIP3")
      (footprint "eagle-import:STRIP3")
      (libsource (lib "eagle-import") (part "STRIP3"))
    )
    (comp (ref "J163")
      (value "STRIP3")
      (footprint "eagle-import:STRIP3")
      (libsource (lib "eagle-import") (part "STRIP3"))
    )
    (comp (ref "J164")
      (value "STRIP3")
      (footprint "eagle-import:STRIP3")
      (libsource (lib "eagle-import") (part "STRIP3"))
    )
    (comp (ref "J165")
      (value "STRIP3")
      (footprint "eagle-import:STRIP3")
      (libsource (lib "eagle-import") (part "STRIP3"))
    )
    (comp (ref "J166")
      (value "STRIP3")
      (footprint "eagle-import:STRIP3")
      (libsource (lib "eagle-import") (part "STRIP3"))
    )
    (comp (ref "J167")
      (value "STRIP3")
      (footprint "eagle-import:STRIP3")
      (libsource (lib "eagle-import") (part "STRIP3"))
    )
    (comp (ref "J168")
      (value "STRIP3")
      (footprint "eagle-import:STRIP3")
      (libsource (lib "eagle-import") (part "STRIP3"))
    )
    (comp (ref "J169")
      (value "STRIP3")
      (footprint "eagle-import:STRIP3")
      (libsource (lib "eagle-import") (part "STRIP3"))
    )
    (comp (ref "J170")
      (value "STRIP3")
      (footprint "eagle-import:STRIP3")
      (libsource (lib "eagle-import") (part "STRIP3"))
    )
    (comp (ref "J176")
      (value "STRIP3")
      (footprint "eagle-import:STRIP3")
      (libsource (lib "eagle-import") (part "STRIP3"))
    )
    (comp (ref "J177")
      (value "STRIP3")
      (footprint "eagle-import:STRIP3")
      (libsource (lib "eagle-import") (part "STRIP3"))
    )
    (comp (ref "J204")
      (value "STRIP2")
      (footprint "eagle-import:STRIP2")
      (libsource (lib "eagle-import") (part "STRIP2"))
    )
    (comp (ref "J205")
      (value "STRIP2")
      (footprint "eagle-import:STRIP2")
      (libsource (lib "eagle-import") (part "STRIP2"))
    )
    (comp (ref "J206")
      (value "STRIP2")
      (footprint "eagle-import:STRIP2")
      (libsource (lib "eagle-import") (part "STRIP2"))
    )
    (comp (ref "J207")
      (value "STRIP2")
      (footprint "eagle-import:STRIP2")
      (libsource (lib "eagle-import") (part "STRIP2"))
    )
    (comp (ref "J251")
      (value "STRIP2")
      (footprint "eagle-import:STRIP2")
      (libsource (lib "eagle-import") (part "STRIP2"))
    )
    (comp (ref "L1")
      (value "F28379D_LAUNCHPAD")
      (footprint "eagle-import:F28379D_LAUNCHPAD")
      (libsource (lib "eagle-import") (part "F28379D_LAUNCHPAD"))
    )
    (comp (ref "POWER")
      (value "PINHD-1X2")
      (footprint "eagle-import:1X02")
      (libsource (lib "eagle-import") (part "PINHD-1X2"))
    )
    (comp (ref "R26")
      (value "470")
      (footprint "eagle-import:M1206")
      (libsource (lib "eagle-import") (part "R-US_M1206"))
    )
    (comp (ref "R27")
      (value "470")
      (footprint "eagle-import:M1206")
      (libsource (lib "eagle-import") (part "R-US_M1206"))
    )
    (comp (ref "S141")
      (value "STRIP5")
      (footprint "eagle-import:STRIP5")
      (libsource (lib "eagle-import") (part "STRIP5"))
    )
    (comp (ref "U$1")
      (value "MPU-9250-BB")
      (footprint "eagle-import:MPU-9250-BB")
      (libsource (lib "eagle-import") (part "MPU-9250-BB"))
    )
    (comp (ref "B3")
      (value "GND SCOPE")
      (footprint "eagle-import:BANANA_MALE")
      (libsource (lib "eagle-import") (part "BANANA_MALE"))
    )
    (comp (ref "B4")
      (value "ADC SCOPE")
      (footprint "eagle-import:BANANA_MALE")
      (libsource (lib "eagle-import") (part "BANANA_MALE"))
    )
    (comp (ref "B5")
      (value "DAC SCOPE")
      (footprint "eagle-import:BANANA_MALE")
      (libsource (lib "eagle-import") (part "BANANA_MALE"))
    )
    (comp (ref "C3")
      (value "0.1uf")
      (footprint "eagle-import:C1206")
      (libsource (lib "eagle-import") (part "C-USC1206"))
    )
    (comp (ref "C5")
      (value "0.1 uF")
      (footprint "eagle-import:C1206")
      (libsource (lib "eagle-import") (part "C-USC1206"))
    )
    (comp (ref "C7")
      (value "2.2 uF")
      (footprint "eagle-import:C1206")
      (libsource (lib "eagle-import") (part "C-USC1206"))
    )
    (comp (ref "C8")
      (value "2.2 uF")
      (footprint "eagle-import:C1206")
      (libsource (lib "eagle-import") (part "C-USC1206"))
    )
    (comp (ref "C11")
      (value "2.2 uF")
      (footprint "eagle-import:C1206")
      (libsource (lib "eagle-import") (part "C-USC1206"))
    )
    (comp (ref "C18")
      (value "2.2 uF")
      (footprint "eagle-import:C1206")
      (libsource (lib "eagle-import") (part "C-USC1206"))
    )
    (comp (ref "J35")
      (value "STRIP2")
      (footprint "eagle-import:STRIP2")
      (libsource (lib "eagle-import") (part "STRIP2"))
    )
    (comp (ref "J36")
      (value "STRIP2")
      (footprint "eagle-import:STRIP2")
      (libsource (lib "eagle-import") (part "STRIP2"))
    )
    (comp (ref "J37")
      (value "STRIP2")
      (footprint "eagle-import:STRIP2")
      (libsource (lib "eagle-import") (part "STRIP2"))
    )
    (comp (ref "J38")
      (value "STRIP2")
      (footprint "eagle-import:STRIP2")
      (libsource (lib "eagle-import") (part "STRIP2"))
    )
    (comp (ref "LED17")
      (value "LEDCHIPLED_1206")
      (footprint "eagle-import:CHIPLED_1206")
      (libsource (lib "eagle-import") (part "LEDCHIPLED_1206"))
    )
    (comp (ref "P1")
      (value "TH_PUSHBOTTON")
      (footprint "eagle-import:TH_PUSHBUTTON")
      (libsource (lib "eagle-import") (part "TH_PUSHBOTTON"))
    )
    (comp (ref "R32")
      (value "4.7K")
      (footprint "eagle-import:M1206")
      (libsource (lib "eagle-import") (part "R-US_M1206"))
    )
    (comp (ref "R33")
      (value "4.7K")
      (footprint "eagle-import:M1206")
      (libsource (lib "eagle-import") (part "R-US_M1206"))
    )
    (comp (ref "R34")
      (value "4.7k")
      (footprint "eagle-import:M1206")
      (libsource (lib "eagle-import") (part "R-US_M1206"))
    )
    (comp (ref "R35")
      (value "4.7k")
      (footprint "eagle-import:M1206")
      (libsource (lib "eagle-import") (part "R-US_M1206"))
    )
    (comp (ref "R36")
      (value "1K")
      (footprint "eagle-import:M1206")
      (libsource (lib "eagle-import") (part "R-US_M1206"))
    )
    (comp (ref "R37")
      (value "4.7k")
      (footprint "eagle-import:M1206")
      (libsource (lib "eagle-import") (part "R-US_M1206"))
    )
    (comp (ref "R38")
      (value "4.7k")
      (footprint "eagle-import:M1206")
      (libsource (lib "eagle-import") (part "R-US_M1206"))
    )
    (comp (ref "S17")
      (value "STRIP5")
      (footprint "eagle-import:STRIP5")
      (libsource (lib "eagle-import") (part "STRIP5"))
    )
    (comp (ref "S18")
      (value "STRIP5")
      (footprint "eagle-import:STRIP5")
      (libsource (lib "eagle-import") (part "STRIP5"))
    )
    (comp (ref "S20")
      (value "STRIP10")
      (footprint "eagle-import:STRIP10")
      (libsource (lib "eagle-import") (part "STRIP10"))
    )
    (comp (ref "S24")
      (value "STRIP10")
      (footprint "eagle-import:STRIP10")
      (libsource (lib "eagle-import") (part "STRIP10"))
    )
    (comp (ref "S53")
      (value "STRIP10")
      (footprint "eagle-import:STRIP10")
      (libsource (lib "eagle-import") (part "STRIP10"))
    )
    (comp (ref "S58")
      (value "STRIP10")
      (footprint "eagle-import:STRIP10")
      (libsource (lib "eagle-import") (part "STRIP10"))
    )
    (comp (ref "SV9")
      (value "MA03-1")
      (footprint "eagle-import:MA03-1")
      (libsource (lib "eagle-import") (part "MA03-1"))
    )
    (comp (ref "SV10")
      (value "MA03-1")
      (footprint "eagle-import:MA03-1")
      (libsource (lib "eagle-import") (part "MA03-1"))
    )
    (comp (ref "SV14")
      (value "MA07-2")
      (footprint "eagle-import:MA07-2")
      (libsource (lib "eagle-import") (part "MA07-2"))
    )
    (comp (ref "SV15")
      (value "MA08-2")
      (footprint "eagle-import:MA08-2")
      (libsource (lib "eagle-import") (part "MA08-2"))
    )
    (comp (ref "U6")
      (value "MAX4506")
      (footprint "eagle-import:SOIC-8")
      (libsource (lib "eagle-import") (part "MAX4506-SOIC8"))
    )
    (comp (ref "U8")
      (value "F28027")
      (footprint "eagle-import:DA38")
      (libsource (lib "eagle-import") (part "TMS320F28027DAS"))
    )
    (comp (ref "C1")
      (value "47uF")
      (footprint "eagle-import:153CLV-0810")
      (libsource (lib "eagle-import") (part "CPOL-US153CLV-0810"))
    )
    (comp (ref "C2")
      (value "680pF")
      (footprint "eagle-import:C1206")
      (libsource (lib "eagle-import") (part "C-USC1206"))
    )
    (comp (ref "C12")
      (value "47uF")
      (footprint "eagle-import:153CLV-0810")
      (libsource (lib "eagle-import") (part "CPOL-US153CLV-0810"))
    )
    (comp (ref "C13")
      (value "47uF")
      (footprint "eagle-import:153CLV-0810")
      (libsource (lib "eagle-import") (part "CPOL-US153CLV-0810"))
    )
    (comp (ref "C14")
      (value "680pF")
      (footprint "eagle-import:C1206")
      (libsource (lib "eagle-import") (part "C-USC1206"))
    )
    (comp (ref "C15")
      (value "47uF")
      (footprint "eagle-import:153CLV-0810")
      (libsource (lib "eagle-import") (part "CPOL-US153CLV-0810"))
    )
    (comp (ref "C16")
      (value "0.1uF")
      (footprint "eagle-import:C1206")
      (libsource (lib "eagle-import") (part "C-USC1206"))
    )
    (comp (ref "C17")
      (value "0.1uF")
      (footprint "eagle-import:C1206")
      (libsource (lib "eagle-import") (part "C-USC1206"))
    )
    (comp (ref "C19")
      (value "22nF")
      (footprint "eagle-import:C1206")
      (libsource (lib "eagle-import") (part "C-USC1206"))
    )
    (comp (ref "C20")
      (value "47uF")
      (footprint "eagle-import:153CLV-0810")
      (libsource (lib "eagle-import") (part "CPOL-US153CLV-0810"))
    )
    (comp (ref "C22")
      (value "0.1uF")
      (footprint "eagle-import:C1206")
      (libsource (lib "eagle-import") (part "C-USC1206"))
    )
    (comp (ref "C23")
      (value "0.1uF")
      (footprint "eagle-import:C1206")
      (libsource (lib "eagle-import") (part "C-USC1206"))
    )
    (comp (ref "C24")
      (value "22nF")
      (footprint "eagle-import:C1206")
      (libsource (lib "eagle-import") (part "C-USC1206"))
    )
    (comp (ref "C25")
      (value "47uF")
      (footprint "eagle-import:153CLV-0810")
      (libsource (lib "eagle-import") (part "CPOL-US153CLV-0810"))
    )
    (comp (ref "C27")
      (value "47uF")
      (footprint "eagle-import:153CLV-0810")
      (libsource (lib "eagle-import") (part "CPOL-US153CLV-0810"))
    )
    (comp (ref "C28")
      (value "47uF")
      (footprint "eagle-import:153CLV-0810")
      (libsource (lib "eagle-import") (part "CPOL-US153CLV-0810"))
    )
    (comp (ref "J4")
      (value "STRIP3")
      (footprint "eagle-import:STRIP3")
      (libsource (lib "eagle-import") (part "STRIP3"))
    )
    (comp (ref "J6")
      (value "STRIP3")
      (footprint "eagle-import:STRIP3")
      (libsource (lib "eagle-import") (part "STRIP3"))
    )
    (comp (ref "J23")
      (value "STRIP3")
      (footprint "eagle-import:STRIP3")
      (libsource (lib "eagle-import") (part "STRIP3"))
    )
    (comp (ref "J24")
      (value "STRIP3")
      (footprint "eagle-import:STRIP3")
      (libsource (lib "eagle-import") (part "STRIP3"))
    )
    (comp (ref "J25")
      (value "STRIP2")
      (footprint "eagle-import:STRIP2")
      (libsource (lib "eagle-import") (part "STRIP2"))
    )
    (comp (ref "J26")
      (value "STRIP2")
      (footprint "eagle-import:STRIP2")
      (libsource (lib "eagle-import") (part "STRIP2"))
    )
    (comp (ref "J27")
      (value "STRIP2")
      (footprint "eagle-import:STRIP2")
      (libsource (lib "eagle-import") (part "STRIP2"))
    )
    (comp (ref "J34")
      (value "STRIP2")
      (footprint "eagle-import:STRIP2")
      (libsource (lib "eagle-import") (part "STRIP2"))
    )
    (comp (ref "J78")
      (value "STRIP2")
      (footprint "eagle-import:STRIP2")
      (libsource (lib "eagle-import") (part "STRIP2"))
    )
    (comp (ref "J79")
      (value "STRIP2")
      (footprint "eagle-import:STRIP2")
      (libsource (lib "eagle-import") (part "STRIP2"))
    )
    (comp (ref "J80")
      (value "STRIP2")
      (footprint "eagle-import:STRIP2")
      (libsource (lib "eagle-import") (part "STRIP2"))
    )
    (comp (ref "J81")
      (value "STRIP2")
      (footprint "eagle-import:STRIP2")
      (libsource (lib "eagle-import") (part "STRIP2"))
    )
    (comp (ref "J82")
      (value "STRIP2")
      (footprint "eagle-import:STRIP2")
      (libsource (lib "eagle-import") (part "STRIP2"))
    )
    (comp (ref "J83")
      (value "STRIP2")
      (footprint "eagle-import:STRIP2")
      (libsource (lib "eagle-import") (part "STRIP2"))
    )
    (comp (ref "J84")
      (value "STRIP2")
      (footprint "eagle-import:STRIP2")
      (libsource (lib "eagle-import") (part "STRIP2"))
    )
    (comp (ref "J85")
      (value "STRIP2")
      (footprint "eagle-import:STRIP2")
      (libsource (lib "eagle-import") (part "STRIP2"))
    )
    (comp (ref "J86")
      (value "STRIP2")
      (footprint "eagle-import:STRIP2")
      (libsource (lib "eagle-import") (part "STRIP2"))
    )
    (comp (ref "J87")
      (value "STRIP2")
      (footprint "eagle-import:STRIP2")
      (libsource (lib "eagle-import") (part "STRIP2"))
    )
    (comp (ref "J196")
      (value "STRIP2")
      (footprint "eagle-import:STRIP2")
      (libsource (lib "eagle-import") (part "STRIP2"))
    )
    (comp (ref "J197")
      (value "STRIP2")
      (footprint "eagle-import:STRIP2")
      (libsource (lib "eagle-import") (part "STRIP2"))
    )
    (comp (ref "J198")
      (value "STRIP2")
      (footprint "eagle-import:STRIP2")
      (libsource (lib "eagle-import") (part "STRIP2"))
    )
    (comp (ref "J199")
      (value "STRIP2")
      (footprint "eagle-import:STRIP2")
      (libsource (lib "eagle-import") (part "STRIP2"))
    )
    (comp (ref "J200")
      (value "STRIP2")
      (footprint "eagle-import:STRIP2")
      (libsource (lib "eagle-import") (part "STRIP2"))
    )
    (comp (ref "J201")
      (value "STRIP2")
      (footprint "eagle-import:STRIP2")
      (libsource (lib "eagle-import") (part "STRIP2"))
    )
    (comp (ref "J202")
      (value "STRIP2")
      (footprint "eagle-import:STRIP2")
      (libsource (lib "eagle-import") (part "STRIP2"))
    )
    (comp (ref "J203")
      (value "STRIP2")
      (footprint "eagle-import:STRIP2")
      (libsource (lib "eagle-import") (part "STRIP2"))
    )
    (comp (ref "JP2")
      (value "JP1E")
      (footprint "eagle-import:JP1")
      (libsource (lib "eagle-import") (part "JP1E"))
    )
    (comp (ref "JP3")
      (value "JP1E")
      (footprint "eagle-import:JP1")
      (libsource (lib "eagle-import") (part "JP1E"))
    )
    (comp (ref "R1")
      (value "R_B")
      (footprint "eagle-import:0207_10")
      (libsource (lib "eagle-import") (part "R-US_0207/10"))
    )
    (comp (ref "R2")
      (value "R_B")
      (footprint "eagle-import:0207_10")
      (libsource (lib "eagle-import") (part "R-US_0207/10"))
    )
    (comp (ref "R3")
      (value "24.9K")
      (footprint "eagle-import:M1206")
      (libsource (lib "eagle-import") (part "R-US_M1206"))
    )
    (comp (ref "R4")
      (value "2.2K")
      (footprint "eagle-import:M1206")
      (libsource (lib "eagle-import") (part "R-US_M1206"))
    )
    (comp (ref "R5")
      (value "2.2K")
      (footprint "eagle-import:M1206")
      (libsource (lib "eagle-import") (part "R-US_M1206"))
    )
    (comp (ref "R6")
      (value "2.2K")
      (footprint "eagle-import:M1206")
      (libsource (lib "eagle-import") (part "R-US_M1206"))
    )
    (comp (ref "R7")
      (value "24.9K")
      (footprint "eagle-import:M1206")
      (libsource (lib "eagle-import") (part "R-US_M1206"))
    )
    (comp (ref "R8")
      (value "2.2K")
      (footprint "eagle-import:M1206")
      (libsource (lib "eagle-import") (part "R-US_M1206"))
    )
    (comp (ref "R18")
      (value "2.2K")
      (footprint "eagle-import:M1206")
      (libsource (lib "eagle-import") (part "R-US_M1206"))
    )
    (comp (ref "R24")
      (value "2.2K")
      (footprint "eagle-import:M1206")
      (libsource (lib "eagle-import") (part "R-US_M1206"))
    )
    (comp (ref "R41")
      (value "1.8K")
      (footprint "eagle-import:M1206")
      (libsource (lib "eagle-import") (part "R-US_M1206"))
    )
    (comp (ref "R42")
      (value "10K")
      (footprint "eagle-import:M1206")
      (libsource (lib "eagle-import") (part "R-US_M1206"))
    )
    (comp (ref "R43")
      (value "1.8K")
      (footprint "eagle-import:M1206")
      (libsource (lib "eagle-import") (part "R-US_M1206"))
    )
    (comp (ref "R44")
      (value "10K")
      (footprint "eagle-import:M1206")
      (libsource (lib "eagle-import") (part "R-US_M1206"))
    )
    (comp (ref "S1")
      (value "SWITCH_A4793")
      (footprint "eagle-import:SWITCH_SLIDE")
      (libsource (lib "eagle-import") (part "SWITCH_SLIDE"))
    )
    (comp (ref "S129")
      (value "STRIP5")
      (footprint "eagle-import:STRIP5")
      (libsource (lib "eagle-import") (part "STRIP5"))
    )
    (comp (ref "S130")
      (value "STRIP5")
      (footprint "eagle-import:STRIP5")
      (libsource (lib "eagle-import") (part "STRIP5"))
    )
    (comp (ref "S137")
      (value "STRIP5")
      (footprint "eagle-import:STRIP5")
      (libsource (lib "eagle-import") (part "STRIP5"))
    )
    (comp (ref "S138")
      (value "STRIP5")
      (footprint "eagle-import:STRIP5")
      (libsource (lib "eagle-import") (part "STRIP5"))
    )
    (comp (ref "S139")
      (value "STRIP5")
      (footprint "eagle-import:STRIP5")
      (libsource (lib "eagle-import") (part "STRIP5"))
    )
    (comp (ref "S147")
      (value "STRIP5")
      (footprint "eagle-import:STRIP5")
      (libsource (lib "eagle-import") (part "STRIP5"))
    )
    (comp (ref "S159")
      (value "SWITCH_DRV8874")
      (footprint "eagle-import:SWITCH_SLIDE")
      (libsource (lib "eagle-import") (part "SWITCH_SLIDE"))
    )
    (comp (ref "SV1")
      (value "MA03-2")
      (footprint "eagle-import:MA03-2")
      (libsource (lib "eagle-import") (part "MA03-2"))
    )
    (comp (ref "SV3")
      (value "MA03-2")
      (footprint "eagle-import:MA03-2")
      (libsource (lib "eagle-import") (part "MA03-2"))
    )
    (comp (ref "SV7")
      (value "MA03-2")
      (footprint "eagle-import:MA03-2")
      (libsource (lib "eagle-import") (part "MA03-2"))
    )
    (comp (ref "SV8")
      (value "MA03-2")
      (footprint "eagle-import:MA03-2")
      (libsource (lib "eagle-import") (part "MA03-2"))
    )
    (comp (ref "T1")
      (value "TIP125")
      (footprint "eagle-import:TO220")
      (libsource (lib "eagle-import") (part "TIP125"))
    )
    (comp (ref "T2")
      (value "TIP125")
      (footprint "eagle-import:TO220")
      (libsource (lib "eagle-import") (part "TIP125"))
    )
    (comp (ref "TRIMPOT1")
      (value "MA03-2")
      (footprint "eagle-import:MA03-2")
      (libsource (lib "eagle-import") (part "MA03-2"))
    )
    (comp (ref "TRIMPOT2")
      (value "MA03-2")
      (footprint "eagle-import:MA03-2")
      (libsource (lib "eagle-import") (part "MA03-2"))
    )
    (comp (ref "U$2")
      (value "GEARMOTOR_MOUNT")
      (footprint "eagle-import:GEARMOTOR_MOUNT")
      (libsource (lib "eagle-import") (part "GEARMOTOR_MOUNT"))
    )
    (comp (ref "U$3")
      (value "GEARMOTOR_MOUNT")
      (footprint "eagle-import:GEARMOTOR_MOUNT")
      (libsource (lib "eagle-import") (part "GEARMOTOR_MOUNT"))
    )
    (comp (ref "U1")
      (value "A4973")
      (footprint "eagle-import:SO16W_LONGERPINS")
      (libsource (lib "eagle-import") (part "A3953"))
    )
    (comp (ref "U2")
      (value "DRV8874")
      (footprint "eagle-import:HTSSOP16")
      (libsource (lib "eagle-import") (part "DRV8874"))
    )
    (comp (ref "U4")
      (value "DRV8874")
      (footprint "eagle-import:HTSSOP16")
      (libsource (lib "eagle-import") (part "DRV8874"))
    )
    (comp (ref "U5")
      (value "A4973")
      (footprint "eagle-import:SO16W_LONGERPINS")
      (libsource (lib "eagle-import") (part "A3953"))
    )
    (comp (ref "B1")
      (value "BUZZER")
      (footprint "eagle-import:BUZZER")
      (libsource (lib "eagle-import") (part "BUZZER"))
    )
    (comp (ref "C6")
      (value "0.1uf")
      (footprint "eagle-import:C1206")
      (libsource (lib "eagle-import") (part "C-USC1206"))
    )
    (comp (ref "C9")
      (value "0.1uf")
      (footprint "eagle-import:C1206")
      (libsource (lib "eagle-import") (part "C-USC1206"))
    )
    (comp (ref "C10")
      (value "0.1uf")
      (footprint "eagle-import:C1206")
      (libsource (lib "eagle-import") (part "C-USC1206"))
    )
    (comp (ref "C21")
      (value "0.1uf")
      (footprint "eagle-import:C1206")
      (libsource (lib "eagle-import") (part "C-USC1206"))
    )
    (comp (ref "G1")
      (value "CR2032V")
      (footprint "eagle-import:CR2032V")
      (libsource (lib "eagle-import") (part "CR2032V"))
    )
    (comp (ref "IC1")
      (value "7404D")
      (footprint "eagle-import:SO14")
      (libsource (lib "eagle-import") (part "7404D"))
    )
    (comp (ref "IC2")
      (value "7404D")
      (footprint "eagle-import:SO14")
      (libsource (lib "eagle-import") (part "7404D"))
    )
    (comp (ref "IC3")
      (value "7404D")
      (footprint "eagle-import:SO14")
      (libsource (lib "eagle-import") (part "7404D"))
    )
    (comp (ref "J1")
      (value "STRIP3")
      (footprint "eagle-import:STRIP3")
      (libsource (lib "eagle-import") (part "STRIP3"))
    )
    (comp (ref "J2")
      (value "STRIP3")
      (footprint "eagle-import:STRIP3")
      (libsource (lib "eagle-import") (part "STRIP3"))
    )
    (comp (ref "J3")
      (value "STRIP3")
      (footprint "eagle-import:STRIP3")
      (libsource (lib "eagle-import") (part "STRIP3"))
    )
    (comp (ref "J7")
      (value "STRIP2")
      (footprint "eagle-import:STRIP2")
      (libsource (lib "eagle-import") (part "STRIP2"))
    )
    (comp (ref "J8")
      (value "STRIP2")
      (footprint "eagle-import:STRIP2")
      (libsource (lib "eagle-import") (part "STRIP2"))
    )
    (comp (ref "J12")
      (value "STRIP2")
      (footprint "eagle-import:STRIP2")
      (libsource (lib "eagle-import") (part "STRIP2"))
    )
    (comp (ref "J13")
      (value "STRIP2")
      (footprint "eagle-import:STRIP2")
      (libsource (lib "eagle-import") (part "STRIP2"))
    )
    (comp (ref "J22")
      (value "STRIP2")
      (footprint "eagle-import:STRIP2")
      (libsource (lib "eagle-import") (part "STRIP2"))
    )
    (comp (ref "J39")
      (value "STRIP2")
      (footprint "eagle-import:STRIP2")
      (libsource (lib "eagle-import") (part "STRIP2"))
    )
    (comp (ref "J40")
      (value "STRIP2")
      (footprint "eagle-import:STRIP2")
      (libsource (lib "eagle-import") (part "STRIP2"))
    )
    (comp (ref "J41")
      (value "STRIP2")
      (footprint "eagle-import:STRIP2")
      (libsource (lib "eagle-import") (part "STRIP2"))
    )
    (comp (ref "J42")
      (value "STRIP2")
      (footprint "eagle-import:STRIP2")
      (libsource (lib "eagle-import") (part "STRIP2"))
    )
    (comp (ref "J43")
      (value "STRIP3")
      (footprint "eagle-import:STRIP3")
      (libsource (lib "eagle-import") (part "STRIP3"))
    )
    (comp (ref "J194")
      (value "STRIP2")
      (footprint "eagle-import:STRIP2")
      (libsource (lib "eagle-import") (part "STRIP2"))
    )
    (comp (ref "J208")
      (value "STRIP2")
      (footprint "eagle-import:STRIP2")
      (libsource (lib "eagle-import") (part "STRIP2"))
    )
    (comp (ref "J209")
      (value "STRIP2")
      (footprint "eagle-import:STRIP2")
      (libsource (lib "eagle-import") (part "STRIP2"))
    )
    (comp (ref "LED1")
      (value "LEDCHIPLED_1206")
      (footprint "eagle-import:CHIPLED_1206")
      (libsource (lib "eagle-import") (part "LEDCHIPLED_1206"))
    )
    (comp (ref "LED2")
      (value "LEDCHIPLED_1206")
      (footprint "eagle-import:CHIPLED_1206")
      (libsource (lib "eagle-import") (part "LEDCHIPLED_1206"))
    )
    (comp (ref "LED3")
      (value "LEDCHIPLED_1206")
      (footprint "eagle-import:CHIPLED_1206")
      (libsource (lib "eagle-import") (part "LEDCHIPLED_1206"))
    )
    (comp (ref "LED4")
      (value "LEDCHIPLED_1206")
      (footprint "eagle-import:CHIPLED_1206")
      (libsource (lib "eagle-import") (part "LEDCHIPLED_1206"))
    )
    (comp (ref "LED5")
      (value "LEDCHIPLED_1206")
      (footprint "eagle-import:CHIPLED_1206")
      (libsource (lib "eagle-import") (part "LEDCHIPLED_1206"))
    )
    (comp (ref "LED6")
      (value "LEDCHIPLED_1206")
      (footprint "eagle-import:CHIPLED_1206")
      (libsource (lib "eagle-import") (part "LEDCHIPLED_1206"))
    )
    (comp (ref "LED7")
      (value "LEDCHIPLED_1206")
      (footprint "eagle-import:CHIPLED_1206")
      (libsource (lib "eagle-import") (part "LEDCHIPLED_1206"))
    )
    (comp (ref "LED8")
      (value "LEDCHIPLED_1206")
      (footprint "eagle-import:CHIPLED_1206")
      (libsource (lib "eagle-import") (part "LEDCHIPLED_1206"))
    )
    (comp (ref "LED9")
      (value "LEDCHIPLED_1206")
      (footprint "eagle-import:CHIPLED_1206")
      (libsource (lib "eagle-import") (part "LEDCHIPLED_1206"))
    )
    (comp (ref "LED10")
      (value "LEDCHIPLED_1206")
      (footprint "eagle-import:CHIPLED_1206")
      (libsource (lib "eagle-import") (part "LEDCHIPLED_1206"))
    )
    (comp (ref "LED11")
      (value "LEDCHIPLED_1206")
      (footprint "eagle-import:CHIPLED_1206")
      (libsource (lib "eagle-import") (part "LEDCHIPLED_1206"))
    )
    (comp (ref "LED12")
      (value "LEDCHIPLED_1206")
      (footprint "eagle-import:CHIPLED_1206")
      (libsource (lib "eagle-import") (part "LEDCHIPLED_1206"))
    )
    (comp (ref "LED13")
      (value "LEDCHIPLED_1206")
      (footprint "eagle-import:CHIPLED_1206")
      (libsource (lib "eagle-import") (part "LEDCHIPLED_1206"))
    )
    (comp (ref "LED14")
      (value "LEDCHIPLED_1206")
      (footprint "eagle-import:CHIPLED_1206")
      (libsource (lib "eagle-import") (part "LEDCHIPLED_1206"))
    )
    (comp (ref "LED15")
      (value "LEDCHIPLED_1206")
      (footprint "eagle-import:CHIPLED_1206")
      (libsource (lib "eagle-import") (part "LEDCHIPLED_1206"))
    )
    (comp (ref "LED16")
      (value "LEDCHIPLED_1206")
      (footprint "eagle-import:CHIPLED_1206")
      (libsource (lib "eagle-import") (part "LEDCHIPLED_1206"))
    )
    (comp (ref "LED18")
      (value "LEDCHIPLED_1206")
      (footprint "eagle-import:CHIPLED_1206")
      (libsource (lib "eagle-import") (part "LEDCHIPLED_1206"))
    )
    (comp (ref "P2")
      (value "TH_PUSHBOTTON")
      (footprint "eagle-import:TH_PUSHBUTTON")
      (libsource (lib "eagle-import") (part "TH_PUSHBOTTON"))
    )
    (comp (ref "Q1")
      (value "32.768KHz")
      (footprint "eagle-import:TC26H")
      (libsource (lib "eagle-import") (part "CRYTALTC26H"))
    )
    (comp (ref "R9")
      (value "4.7K")
      (footprint "eagle-import:R1206")
      (libsource (lib "eagle-import") (part "R-US_R1206"))
    )
    (comp (ref "R10")
      (value "4.7K")
      (footprint "eagle-import:R1206")
      (libsource (lib "eagle-import") (part "R-US_R1206"))
    )
    (comp (ref "R11")
      (value "R-US_R1206")
      (footprint "eagle-import:R1206")
      (libsource (lib "eagle-import") (part "R-US_R1206"))
    )
    (comp (ref "R12")
      (value "R-US_R1206")
      (footprint "eagle-import:R1206")
      (libsource (lib "eagle-import") (part "R-US_R1206"))
    )
    (comp (ref "R13")
      (value "R-US_R1206")
      (footprint "eagle-import:R1206")
      (libsource (lib "eagle-import") (part "R-US_R1206"))
    )
    (comp (ref "R14")
      (value "R-US_R1206")
      (footprint "eagle-import:R1206")
      (libsource (lib "eagle-import") (part "R-US_R1206"))
    )
    (comp (ref "R15")
      (value "R-US_R1206")
      (footprint "eagle-import:R1206")
      (libsource (lib "eagle-import") (part "R-US_R1206"))
    )
    (comp (ref "R16")
      (value "R-US_R1206")
      (footprint "eagle-import:R1206")
      (libsource (lib "eagle-import") (part "R-US_R1206"))
    )
    (comp (ref "R17")
      (value "R-US_R1206")
      (footprint "eagle-import:R1206")
      (libsource (lib "eagle-import") (part "R-US_R1206"))
    )
    (comp (ref "R19")
      (value "R-US_R1206")
      (footprint "eagle-import:R1206")
      (libsource (lib "eagle-import") (part "R-US_R1206"))
    )
    (comp (ref "R20")
      (value "R-US_R1206")
      (footprint "eagle-import:R1206")
      (libsource (lib "eagle-import") (part "R-US_R1206"))
    )
    (comp (ref "R21")
      (value "R-US_R1206")
      (footprint "eagle-import:R1206")
      (libsource (lib "eagle-import") (part "R-US_R1206"))
    )
    (comp (ref "R22")
      (value "R-US_R1206")
      (footprint "eagle-import:R1206")
      (libsource (lib "eagle-import") (part "R-US_R1206"))
    )
    (comp (ref "R23")
      (value "R-US_R1206")
      (footprint "eagle-import:R1206")
      (libsource (lib "eagle-import") (part "R-US_R1206"))
    )
    (comp (ref "R28")
      (value "R-US_R1206")
      (footprint "eagle-import:R1206")
      (libsource (lib "eagle-import") (part "R-US_R1206"))
    )
    (comp (ref "R29")
      (value "R-US_R1206")
      (footprint "eagle-import:R1206")
      (libsource (lib "eagle-import") (part "R-US_R1206"))
    )
    (comp (ref "R30")
      (value "R-US_R1206")
      (footprint "eagle-import:R1206")
      (libsource (lib "eagle-import") (part "R-US_R1206"))
    )
    (comp (ref "R31")
      (value "R-US_R1206")
      (footprint "eagle-import:R1206")
      (libsource (lib "eagle-import") (part "R-US_R1206"))
    )
    (comp (ref "R39")
      (value "10K")
      (footprint "eagle-import:R1206")
      (libsource (lib "eagle-import") (part "R-US_R1206"))
    )
    (comp (ref "R40")
      (value "100")
      (footprint "eagle-import:R1206")
      (libsource (lib "eagle-import") (part "R-US_R1206"))
    )
    (comp (ref "R45")
      (value "1K")
      (footprint "eagle-import:R1206")
      (libsource (lib "eagle-import") (part "R-US_R1206"))
    )
    (comp (ref "S167")
      (value "STRIP5")
      (footprint "eagle-import:STRIP5")
      (libsource (lib "eagle-import") (part "STRIP5"))
    )
    (comp (ref "S168")
      (value "STRIP5")
      (footprint "eagle-import:STRIP5")
      (libsource (lib "eagle-import") (part "STRIP5"))
    )
    (comp (ref "S169")
      (value "STRIP5")
      (footprint "eagle-import:STRIP5")
      (libsource (lib "eagle-import") (part "STRIP5"))
    )
    (comp (ref "S170")
      (value "STRIP5")
      (footprint "eagle-import:STRIP5")
      (libsource (lib "eagle-import") (part "STRIP5"))
    )
    (comp (ref "S171")
      (value "STRIP5")
      (footprint "eagle-import:STRIP5")
      (libsource (lib "eagle-import") (part "STRIP5"))
    )
    (comp (ref "S172")
      (value "STRIP5")
      (footprint "eagle-import:STRIP5")
      (libsource (lib "eagle-import") (part "STRIP5"))
    )
    (comp (ref "S173")
      (value "STRIP5")
      (footprint "eagle-import:STRIP5")
      (libsource (lib "eagle-import") (part "STRIP5"))
    )
    (comp (ref "S174")
      (value "STRIP5")
      (footprint "eagle-import:STRIP5")
      (libsource (lib "eagle-import") (part "STRIP5"))
    )
    (comp (ref "S175")
      (value "STRIP5")
      (footprint "eagle-import:STRIP5")
      (libsource (lib "eagle-import") (part "STRIP5"))
    )
    (comp (ref "S176")
      (value "STRIP5")
      (footprint "eagle-import:STRIP5")
      (libsource (lib "eagle-import") (part "STRIP5"))
    )
    (comp (ref "S177")
      (value "STRIP5")
      (footprint "eagle-import:STRIP5")
      (libsource (lib "eagle-import") (part "STRIP5"))
    )
    (comp (ref "S178")
      (value "STRIP5")
      (footprint "eagle-import:STRIP5")
      (libsource (lib "eagle-import") (part "STRIP5"))
    )
    (comp (ref "S179")
      (value "STRIP5")
      (footprint "eagle-import:STRIP5")
      (libsource (lib "eagle-import") (part "STRIP5"))
    )
    (comp (ref "S180")
      (value "STRIP5")
      (footprint "eagle-import:STRIP5")
      (libsource (lib "eagle-import") (part "STRIP5"))
    )
    (comp (ref "S181")
      (value "STRIP5")
      (footprint "eagle-import:STRIP5")
      (libsource (lib "eagle-import") (part "STRIP5"))
    )
    (comp (ref "S182")
      (value "STRIP5")
      (footprint "eagle-import:STRIP5")
      (libsource (lib "eagle-import") (part "STRIP5"))
    )
    (comp (ref "S183")
      (value "STRIP5")
      (footprint "eagle-import:STRIP5")
      (libsource (lib "eagle-import") (part "STRIP5"))
    )
    (comp (ref "S184")
      (value "STRIP5")
      (footprint "eagle-import:STRIP5")
      (libsource (lib "eagle-import") (part "STRIP5"))
    )
    (comp (ref "S185")
      (value "STRIP5")
      (footprint "eagle-import:STRIP5")
      (libsource (lib "eagle-import") (part "STRIP5"))
    )
    (comp (ref "S186")
      (value "STRIP5")
      (footprint "eagle-import:STRIP5")
      (libsource (lib "eagle-import") (part "STRIP5"))
    )
    (comp (ref "S187")
      (value "STRIP5")
      (footprint "eagle-import:STRIP5")
      (libsource (lib "eagle-import") (part "STRIP5"))
    )
    (comp (ref "S188")
      (value "STRIP5")
      (footprint "eagle-import:STRIP5")
      (libsource (lib "eagle-import") (part "STRIP5"))
    )
    (comp (ref "S189")
      (value "STRIP5")
      (footprint "eagle-import:STRIP5")
      (libsource (lib "eagle-import") (part "STRIP5"))
    )
    (comp (ref "S210")
      (value "STRIP5")
      (footprint "eagle-import:STRIP5")
      (libsource (lib "eagle-import") (part "STRIP5"))
    )
    (comp (ref "S211")
      (value "STRIP5")
      (footprint "eagle-import:STRIP5")
      (libsource (lib "eagle-import") (part "STRIP5"))
    )
    (comp (ref "S212")
      (value "STRIP5")
      (footprint "eagle-import:STRIP5")
      (libsource (lib "eagle-import") (part "STRIP5"))
    )
    (comp (ref "S213")
      (value "STRIP5")
      (footprint "eagle-import:STRIP5")
      (libsource (lib "eagle-import") (part "STRIP5"))
    )
    (comp (ref "S214")
      (value "STRIP5")
      (footprint "eagle-import:STRIP5")
      (libsource (lib "eagle-import") (part "STRIP5"))
    )
    (comp (ref "S215")
      (value "STRIP5")
      (footprint "eagle-import:STRIP5")
      (libsource (lib "eagle-import") (part "STRIP5"))
    )
    (comp (ref "S216")
      (value "STRIP5")
      (footprint "eagle-import:STRIP5")
      (libsource (lib "eagle-import") (part "STRIP5"))
    )
    (comp (ref "S217")
      (value "STRIP5")
      (footprint "eagle-import:STRIP5")
      (libsource (lib "eagle-import") (part "STRIP5"))
    )
    (comp (ref "S218")
      (value "STRIP5")
      (footprint "eagle-import:STRIP5")
      (libsource (lib "eagle-import") (part "STRIP5"))
    )
    (comp (ref "S219")
      (value "STRIP5")
      (footprint "eagle-import:STRIP5")
      (libsource (lib "eagle-import") (part "STRIP5"))
    )
    (comp (ref "S220")
      (value "STRIP5")
      (footprint "eagle-import:STRIP5")
      (libsource (lib "eagle-import") (part "STRIP5"))
    )
    (comp (ref "S221")
      (value "STRIP5")
      (footprint "eagle-import:STRIP5")
      (libsource (lib "eagle-import") (part "STRIP5"))
    )
    (comp (ref "S222")
      (value "STRIP5")
      (footprint "eagle-import:STRIP5")
      (libsource (lib "eagle-import") (part "STRIP5"))
    )
    (comp (ref "S223")
      (value "STRIP5")
      (footprint "eagle-import:STRIP5")
      (libsource (lib "eagle-import") (part "STRIP5"))
    )
    (comp (ref "S224")
      (value "STRIP5")
      (footprint "eagle-import:STRIP5")
      (libsource (lib "eagle-import") (part "STRIP5"))
    )
    (comp (ref "S225")
      (value "STRIP5")
      (footprint "eagle-import:STRIP5")
      (libsource (lib "eagle-import") (part "STRIP5"))
    )
    (comp (ref "S226")
      (value "STRIP5")
      (footprint "eagle-import:STRIP5")
      (libsource (lib "eagle-import") (part "STRIP5"))
    )
    (comp (ref "SV16")
      (value "MA10-2")
      (footprint "eagle-import:MA10-2")
      (libsource (lib "eagle-import") (part "MA10-2"))
    )
    (comp (ref "SV17")
      (value "MA10-2")
      (footprint "eagle-import:MA10-2")
      (libsource (lib "eagle-import") (part "MA10-2"))
    )
    (comp (ref "SV18")
      (value "MA10-1")
      (footprint "eagle-import:MA10-1")
      (libsource (lib "eagle-import") (part "MA10-1"))
    )
    (comp (ref "SV19")
      (value "MA10-1")
      (footprint "eagle-import:MA10-1")
      (libsource (lib "eagle-import") (part "MA10-1"))
    )
    (comp (ref "U3")
      (value "BQ32000")
      (footprint "eagle-import:SO08")
      (libsource (lib "eagle-import") (part "BQ32000"))
    )
  )
  (nets
    (net (code "1") (name "+5V") (class "Default")
      (node (ref "DCDC5V") (pin "3") (pinfunction "3_3") (pintype "passive"))
      (node (ref "J103") (pin "P$1") (pinfunction "P$1_P$1") (pintype "bidirectional"))
      (node (ref "J103") (pin "P$2") (pinfunction "P$2_P$2") (pintype "bidirectional"))
      (node (ref "J103") (pin "P$3") (pinfunction "P$3_P$3") (pintype "bidirectional"))
      (node (ref "J152") (pin "P$1") (pinfunction "P$1_P$1") (pintype "bidirectional"))
      (node (ref "J152") (pin "P$2") (pinfunction "P$2_P$2") (pintype "bidirectional"))
      (node (ref "J152") (pin "P$3") (pinfunction "P$3_P$3") (pintype "bidirectional"))
      (node (ref "J200") (pin "P$1") (pinfunction "P$1_P$1") (pintype "bidirectional"))
      (node (ref "J200") (pin "P$2") (pinfunction "P$2_P$2") (pintype "bidirectional"))
      (node (ref "J203") (pin "P$1") (pinfunction "P$1_P$1") (pintype "bidirectional"))
      (node (ref "J203") (pin "P$2") (pinfunction "P$2_P$2") (pintype "bidirectional"))
      (node (ref "L1") (pin "P$21") (pinfunction "5V_1_P$21") (pintype "bidirectional"))
      (node (ref "L1") (pin "P$61") (pinfunction "5V_2_P$61") (pintype "bidirectional"))
      (node (ref "R26") (pin "2") (pinfunction "2_2") (pintype "passive"))
      (node (ref "S17") (pin "P$1") (pinfunction "P$1_P$1") (pintype "bidirectional"))
      (node (ref "S17") (pin "P$2") (pinfunction "P$2_P$2") (pintype "bidirectional"))
      (node (ref "S17") (pin "P$3") (pinfunction "P$3_P$3") (pintype "bidirectional"))
      (node (ref "S17") (pin "P$4") (pinfunction "P$4_P$4") (pintype "bidirectional"))
      (node (ref "S17") (pin "P$5") (pinfunction "P$5_P$5") (pintype "bidirectional"))
      (node (ref "S18") (pin "P$1") (pinfunction "P$1_P$1") (pintype "bidirectional"))
      (node (ref "S18") (pin "P$2") (pinfunction "P$2_P$2") (pintype "bidirectional"))
      (node (ref "S18") (pin "P$3") (pinfunction "P$3_P$3") (pintype "bidirectional"))
      (node (ref "S18") (pin "P$4") (pinfunction "P$4_P$4") (pintype "bidirectional"))
      (node (ref "S18") (pin "P$5") (pinfunction "P$5_P$5") (pintype "bidirectional"))
      (node (ref "SV2") (pin "1") (pinfunction "1_1") (pintype "passive"))
      (node (ref "SV2") (pin "2") (pinfunction "2_2") (pintype "passive"))
      (node (ref "SV2") (pin "3") (pinfunction "3_3") (pintype "passive"))
      (node (ref "SV2") (pin "4") (pinfunction "4_4") (pintype "passive"))
    )
    (net (code "2") (name "28027_GPIO0") (class "Default")
      (node (ref "J26") (pin "P$1") (pinfunction "P$1_P$1") (pintype "bidirectional"))
      (node (ref "J26") (pin "P$2") (pinfunction "P$2_P$2") (pintype "bidirectional"))
      (node (ref "U8") (pin "37") (pinfunction "GPIO0/EPWM1A_37") (pintype "bidirectional"))
    )
    (net (code "3") (name "28027_GPIO1") (class "Default")
      (node (ref "J27") (pin "P$1") (pinfunction "P$1_P$1") (pintype "bidirectional"))
      (node (ref "J27") (pin "P$2") (pinfunction "P$2_P$2") (pintype "bidirectional"))
      (node (ref "U8") (pin "36") (pinfunction "GPIO1/EPWM1A_36") (pintype "bidirectional"))
    )
    (net (code "4") (name "28027_GPIO2") (class "Default")
      (node (ref "SV15") (pin "16") (pinfunction "16_16") (pintype "passive"))
      (node (ref "U8") (pin "5") (pinfunction "GPIO2/EPWM2A_5") (pintype "bidirectional"))
    )
    (net (code "5") (name "28027_GPIO3") (class "Default")
      (node (ref "SV15") (pin "14") (pinfunction "14_14") (pintype "passive"))
      (node (ref "U8") (pin "6") (pinfunction "GPIO3/EPWM2B_6") (pintype "bidirectional"))
    )
    (net (code "6") (name "28027_GPIO4") (class "Default")
      (node (ref "SV15") (pin "12") (pinfunction "12_12") (pintype "passive"))
      (node (ref "U8") (pin "7") (pinfunction "GPIO4/EPWM3A_7") (pintype "bidirectional"))
    )
    (net (code "7") (name "28027_GPIO5") (class "Default")
      (node (ref "SV15") (pin "10") (pinfunction "10_10") (pintype "passive"))
      (node (ref "U8") (pin "8") (pinfunction "GPIO5/EPWM3B_8") (pintype "bidirectional"))
    )
    (net (code "8") (name "28027_GPIO6") (class "Default")
      (node (ref "SV15") (pin "8") (pinfunction "8_8") (pintype "passive"))
      (node (ref "U8") (pin "9") (pinfunction "GPIO6/EPWM4A_9") (pintype "bidirectional"))
    )
    (net (code "9") (name "28027_GPIO7") (class "Default")
      (node (ref "SV15") (pin "6") (pinfunction "6_6") (pintype "passive"))
      (node (ref "U8") (pin "10") (pinfunction "GPIO7/EPWM4B_10") (pintype "bidirectional"))
    )
    (net (code "10") (name "28027_GPIO12") (class "Default")
      (node (ref "SV15") (pin "4") (pinfunction "4_4") (pintype "passive"))
      (node (ref "U8") (pin "13") (pinfunction "GPIO12/SCITXDA_13") (pintype "bidirectional"))
    )
    (net (code "11") (name "28027_GPIO34") (class "Default")
      (node (ref "LED17") (pin "C") (pinfunction "C_C") (pintype "passive"))
      (node (ref "R37") (pin "1") (pinfunction "1_1") (pintype "passive"))
      (node (ref "U8") (pin "27") (pinfunction "GPIO34_27") (pintype "bidirectional"))
    )
    (net (code "12") (name "28027_SCL") (class "Default")
      (node (ref "R34") (pin "2") (pinfunction "2_2") (pintype "passive"))
      (node (ref "SV15") (pin "3") (pinfunction "3_3") (pintype "passive"))
      (node (ref "U8") (pin "15") (pinfunction "GPIO29/SCITXDA_15") (pintype "bidirectional"))
    )
    (net (code "13") (name "28027_SDA") (class "Default")
      (node (ref "R35") (pin "2") (pinfunction "2_2") (pintype "passive"))
      (node (ref "SV15") (pin "5") (pinfunction "5_5") (pintype "passive"))
      (node (ref "U8") (pin "14") (pinfunction "GPIO28/SCIRXDA_14") (pintype "bidirectional"))
    )
    (net (code "14") (name "28027_SPICLKA") (class "Default")
      (node (ref "J38") (pin "P$1") (pinfunction "P$1_P$1") (pintype "bidirectional"))
      (node (ref "U8") (pin "32") (pinfunction "GPIO18/SPICLKA/SCITXDA_32") (pintype "bidirectional"))
    )
    (net (code "15") (name "28027_SPISIMOA") (class "Default")
      (node (ref "J36") (pin "P$1") (pinfunction "P$1_P$1") (pintype "bidirectional"))
      (node (ref "U8") (pin "35") (pinfunction "GPIO16/SPISIMOA_35") (pintype "bidirectional"))
    )
    (net (code "16") (name "28027_SPISOMIA") (class "Default")
      (node (ref "J35") (pin "P$1") (pinfunction "P$1_P$1") (pintype "bidirectional"))
      (node (ref "U8") (pin "34") (pinfunction "GPIO17/SPISOMIA_34") (pintype "bidirectional"))
    )
    (net (code "17") (name "28027_SPISTEA") (class "Default")
      (node (ref "J37") (pin "P$1") (pinfunction "P$1_P$1") (pintype "bidirectional"))
      (node (ref "U8") (pin "33") (pinfunction "GPIO19//SPISTEA/SCIRXDA_33") (pintype "bidirectional"))
    )
    (net (code "18") (name "A4973EN") (class "Default")
      (node (ref "S1") (pin "P$2") (pinfunction "P2_P$2") (pintype "bidirectional"))
      (node (ref "U1") (pin "8") (pinfunction "~{ENABLE}_8") (pintype "bidirectional"))
      (node (ref "U5") (pin "8") (pinfunction "~{ENABLE}_8") (pintype "bidirectional"))
    )
    (net (code "19") (name "ADCA0") (class "Default")
      (node (ref "SV15") (pin "7") (pinfunction "7_7") (pintype "passive"))
      (node (ref "U8") (pin "21") (pinfunction "ADCINA0/VREFHI_21") (pintype "bidirectional"))
    )
    (net (code "20") (name "ADCA2") (class "Default")
      (node (ref "SV15") (pin "9") (pinfunction "9_9") (pintype "passive"))
      (node (ref "U8") (pin "20") (pinfunction "ADCINA2/AIO2_20") (pintype "bidirectional"))
    )
    (net (code "21") (name "ADCA4") (class "Default")
      (node (ref "SV15") (pin "13") (pinfunction "13_13") (pintype "passive"))
      (node (ref "U8") (pin "19") (pinfunction "ADCINA4/AIO4_19") (pintype "bidirectional"))
    )
    (net (code "22") (name "ADCA6") (class "Default")
      (node (ref "SV15") (pin "2") (pinfunction "2_2") (pintype "passive"))
      (node (ref "U8") (pin "18") (pinfunction "ADCINA6/AIO6_18") (pintype "bidirectional"))
    )
    (net (code "23") (name "ADCB2") (class "Default")
      (node (ref "SV15") (pin "11") (pinfunction "11_11") (pintype "passive"))
      (node (ref "U8") (pin "24") (pinfunction "ADCINB2/AIO10_24") (pintype "bidirectional"))
    )
    (net (code "24") (name "ADCB4") (class "Default")
      (node (ref "SV15") (pin "15") (pinfunction "15_15") (pintype "passive"))
      (node (ref "U8") (pin "25") (pinfunction "ADCINB4/AIO12_25") (pintype "bidirectional"))
    )
    (net (code "25") (name "ADCB6") (class "Default")
      (node (ref "U8") (pin "26") (pinfunction "ADCINB6/AIO14_26") (pintype "bidirectional"))
    )
    (net (code "26") (name "ADCIN14") (class "Default")
      (node (ref "J105") (pin "P$1") (pinfunction "P$1_P$1") (pintype "bidirectional"))
      (node (ref "J105") (pin "P$2") (pinfunction "P$2_P$2") (pintype "bidirectional"))
      (node (ref "J105") (pin "P$3") (pinfunction "P$3_P$3") (pintype "bidirectional"))
      (node (ref "L1") (pin "P$23") (pinfunction "ADCIN14_P$23") (pintype "bidirectional"))
    )
    (net (code "27") (name "ADCIN15") (class "Default")
      (node (ref "J150") (pin "P$1") (pinfunction "P$1_P$1") (pintype "bidirectional"))
      (node (ref "J150") (pin "P$2") (pinfunction "P$2_P$2") (pintype "bidirectional"))
      (node (ref "J150") (pin "P$3") (pinfunction "P$3_P$3") (pintype "bidirectional"))
      (node (ref "L1") (pin "P$63") (pinfunction "ADCIN15_P$63") (pintype "bidirectional"))
    )
    (net (code "28") (name "ADCINA2") (class "Default")
      (node (ref "J111") (pin "P$1") (pinfunction "P$1_P$1") (pintype "bidirectional"))
      (node (ref "J111") (pin "P$2") (pinfunction "P$2_P$2") (pintype "bidirectional"))
      (node (ref "J111") (pin "P$3") (pinfunction "P$3_P$3") (pintype "bidirectional"))
      (node (ref "L1") (pin "P$29") (pinfunction "ADCINA2_P$29") (pintype "bidirectional"))
      (node (ref "SV11") (pin "3") (pinfunction "3_3") (pintype "passive"))
    )
    (net (code "29") (name "ADCINA3") (class "Default")
      (node (ref "J108") (pin "P$1") (pinfunction "P$1_P$1") (pintype "bidirectional"))
      (node (ref "J108") (pin "P$2") (pinfunction "P$2_P$2") (pintype "bidirectional"))
      (node (ref "J108") (pin "P$3") (pinfunction "P$3_P$3") (pintype "bidirectional"))
      (node (ref "L1") (pin "P$26") (pinfunction "ADCINA3_P$26") (pintype "bidirectional"))
      (node (ref "SV11") (pin "4") (pinfunction "4_4") (pintype "passive"))
    )
    (net (code "30") (name "ADCINA4") (class "Default")
      (node (ref "J144") (pin "P$1") (pinfunction "P$1_P$1") (pintype "bidirectional"))
      (node (ref "J144") (pin "P$2") (pinfunction "P$2_P$2") (pintype "bidirectional"))
      (node (ref "J144") (pin "P$3") (pinfunction "P$3_P$3") (pintype "bidirectional"))
      (node (ref "L1") (pin "P$69") (pinfunction "ADCINA4_P$69") (pintype "bidirectional"))
    )
    (net (code "31") (name "ADCINA5") (class "Default")
      (node (ref "J147") (pin "P$1") (pinfunction "P$1_P$1") (pintype "bidirectional"))
      (node (ref "J147") (pin "P$2") (pinfunction "P$2_P$2") (pintype "bidirectional"))
      (node (ref "J147") (pin "P$3") (pinfunction "P$3_P$3") (pintype "bidirectional"))
      (node (ref "L1") (pin "P$66") (pinfunction "ADCINA5_P$66") (pintype "bidirectional"))
    )
    (net (code "32") (name "ADCINB2") (class "Default")
      (node (ref "J110") (pin "P$1") (pinfunction "P$1_P$1") (pintype "bidirectional"))
      (node (ref "J110") (pin "P$2") (pinfunction "P$2_P$2") (pintype "bidirectional"))
      (node (ref "J110") (pin "P$3") (pinfunction "P$3_P$3") (pintype "bidirectional"))
      (node (ref "L1") (pin "P$28") (pinfunction "ADCINB2_P$28") (pintype "bidirectional"))
    )
    (net (code "33") (name "ADCINB3") (class "Default")
      (node (ref "J107") (pin "P$1") (pinfunction "P$1_P$1") (pintype "bidirectional"))
      (node (ref "J107") (pin "P$2") (pinfunction "P$2_P$2") (pintype "bidirectional"))
      (node (ref "J107") (pin "P$3") (pinfunction "P$3_P$3") (pintype "bidirectional"))
      (node (ref "L1") (pin "P$25") (pinfunction "ADCINB3_P$25") (pintype "bidirectional"))
    )
    (net (code "34") (name "ADCINB4") (class "Default")
      (node (ref "J145") (pin "P$1") (pinfunction "P$1_P$1") (pintype "bidirectional"))
      (node (ref "J145") (pin "P$2") (pinfunction "P$2_P$2") (pintype "bidirectional"))
      (node (ref "J145") (pin "P$3") (pinfunction "P$3_P$3") (pintype "bidirectional"))
      (node (ref "L1") (pin "P$68") (pinfunction "ADCINB4_P$68") (pintype "bidirectional"))
      (node (ref "SV12") (pin "4") (pinfunction "4_4") (pintype "passive"))
    )
    (net (code "35") (name "ADCINB5") (class "Default")
      (node (ref "J148") (pin "P$1") (pinfunction "P$1_P$1") (pintype "bidirectional"))
      (node (ref "J148") (pin "P$2") (pinfunction "P$2_P$2") (pintype "bidirectional"))
      (node (ref "J148") (pin "P$3") (pinfunction "P$3_P$3") (pintype "bidirectional"))
      (node (ref "L1") (pin "P$65") (pinfunction "ADCINB5_P$65") (pintype "bidirectional"))
    )
    (net (code "36") (name "ADCINC2") (class "Default")
      (node (ref "J109") (pin "P$1") (pinfunction "P$1_P$1") (pintype "bidirectional"))
      (node (ref "J109") (pin "P$2") (pinfunction "P$2_P$2") (pintype "bidirectional"))
      (node (ref "J109") (pin "P$3") (pinfunction "P$3_P$3") (pintype "bidirectional"))
      (node (ref "L1") (pin "P$27") (pinfunction "ADCINC2_P$27") (pintype "bidirectional"))
    )
    (net (code "37") (name "ADCINC3") (class "Default")
      (node (ref "J106") (pin "P$1") (pinfunction "P$1_P$1") (pintype "bidirectional"))
      (node (ref "J106") (pin "P$2") (pinfunction "P$2_P$2") (pintype "bidirectional"))
      (node (ref "J106") (pin "P$3") (pinfunction "P$3_P$3") (pintype "bidirectional"))
      (node (ref "L1") (pin "P$24") (pinfunction "ADCINC3_P$24") (pintype "bidirectional"))
    )
    (net (code "38") (name "ADCINC4") (class "Default")
      (node (ref "J146") (pin "P$1") (pinfunction "P$1_P$1") (pintype "bidirectional"))
      (node (ref "J146") (pin "P$2") (pinfunction "P$2_P$2") (pintype "bidirectional"))
      (node (ref "J146") (pin "P$3") (pinfunction "P$3_P$3") (pintype "bidirectional"))
      (node (ref "L1") (pin "P$67") (pinfunction "ADCINC4_P$67") (pintype "bidirectional"))
    )
    (net (code "39") (name "ADCINC5") (class "Default")
      (node (ref "J149") (pin "P$1") (pinfunction "P$1_P$1") (pintype "bidirectional"))
      (node (ref "J149") (pin "P$2") (pinfunction "P$2_P$2") (pintype "bidirectional"))
      (node (ref "J149") (pin "P$3") (pinfunction "P$3_P$3") (pintype "bidirectional"))
      (node (ref "L1") (pin "P$64") (pinfunction "ADCINC5_P$64") (pintype "bidirectional"))
    )
    (net (code "40") (name "DACOUTA") (class "Default")
      (node (ref "J112") (pin "P$1") (pinfunction "P$1_P$1") (pintype "bidirectional"))
      (node (ref "J112") (pin "P$2") (pinfunction "P$2_P$2") (pintype "bidirectional"))
      (node (ref "J112") (pin "P$3") (pinfunction "P$3_P$3") (pintype "bidirectional"))
      (node (ref "L1") (pin "P$30") (pinfunction "ADCINA0/DACOUTA_P$30") (pintype "bidirectional"))
    )
    (net (code "41") (name "DACOUTB") (class "Default")
      (node (ref "J143") (pin "P$1") (pinfunction "P$1_P$1") (pintype "bidirectional"))
      (node (ref "J143") (pin "P$2") (pinfunction "P$2_P$2") (pintype "bidirectional"))
      (node (ref "J143") (pin "P$3") (pinfunction "P$3_P$3") (pintype "bidirectional"))
      (node (ref "L1") (pin "P$70") (pinfunction "ADCINA1/DACOUTB_P$70") (pintype "bidirectional"))
    )
    (net (code "42") (name "DRV1_DIR") (class "Default")
      (node (ref "J80") (pin "P$1") (pinfunction "P$1_P$1") (pintype "bidirectional"))
      (node (ref "J80") (pin "P$2") (pinfunction "P$2_P$2") (pintype "bidirectional"))
      (node (ref "U2") (pin "P$2") (pinfunction "PH/IN2_P$2") (pintype "bidirectional"))
    )
    (net (code "43") (name "DRV1_M+") (class "Default")
      (node (ref "SV7") (pin "1") (pinfunction "1_1") (pintype "passive"))
      (node (ref "SV7") (pin "3") (pinfunction "3_3") (pintype "passive"))
      (node (ref "SV7") (pin "5") (pinfunction "5_5") (pintype "passive"))
      (node (ref "U2") (pin "P$8") (pinfunction "OUT1_P$8") (pintype "bidirectional"))
    )
    (net (code "44") (name "DRV1_M-") (class "Default")
      (node (ref "SV7") (pin "2") (pinfunction "2_2") (pintype "passive"))
      (node (ref "SV7") (pin "4") (pinfunction "4_4") (pintype "passive"))
      (node (ref "SV7") (pin "6") (pinfunction "6_6") (pintype "passive"))
      (node (ref "U2") (pin "P$10") (pinfunction "OUT2_P$10") (pintype "bidirectional"))
    )
    (net (code "45") (name "DRV1_PWM") (class "Default")
      (node (ref "J79") (pin "P$1") (pinfunction "P$1_P$1") (pintype "bidirectional"))
      (node (ref "J79") (pin "P$2") (pinfunction "P$2_P$2") (pintype "bidirectional"))
      (node (ref "U2") (pin "P$1") (pinfunction "EN/IN1_P$1") (pintype "bidirectional"))
    )
    (net (code "46") (name "DRV2_DIR") (class "Default")
      (node (ref "J83") (pin "P$1") (pinfunction "P$1_P$1") (pintype "bidirectional"))
      (node (ref "J83") (pin "P$2") (pinfunction "P$2_P$2") (pintype "bidirectional"))
      (node (ref "U4") (pin "P$2") (pinfunction "PH/IN2_P$2") (pintype "bidirectional"))
    )
    (net (code "47") (name "DRV2_M+") (class "Default")
      (node (ref "SV8") (pin "1") (pinfunction "1_1") (pintype "passive"))
      (node (ref "SV8") (pin "3") (pinfunction "3_3") (pintype "passive"))
      (node (ref "SV8") (pin "5") (pinfunction "5_5") (pintype "passive"))
      (node (ref "U4") (pin "P$8") (pinfunction "OUT1_P$8") (pintype "bidirectional"))
    )
    (net (code "48") (name "DRV2_M-") (class "Default")
      (node (ref "SV8") (pin "2") (pinfunction "2_2") (pintype "passive"))
      (node (ref "SV8") (pin "4") (pinfunction "4_4") (pintype "passive"))
      (node (ref "SV8") (pin "6") (pinfunction "6_6") (pintype "passive"))
      (node (ref "U4") (pin "P$10") (pinfunction "OUT2_P$10") (pintype "bidirectional"))
    )
    (net (code "49") (name "DRV2_PWM") (class "Default")
      (node (ref "J82") (pin "P$1") (pinfunction "P$1_P$1") (pintype "bidirectional"))
      (node (ref "J82") (pin "P$2") (pinfunction "P$2_P$2") (pintype "bidirectional"))
      (node (ref "U4") (pin "P$1") (pinfunction "EN/IN1_P$1") (pintype "bidirectional"))
    )
    (net (code "50") (name "GND") (class "Default")
      (node (ref "3V3") (pin "C") (pinfunction "C_C") (pintype "passive"))
      (node (ref "5V") (pin "C") (pinfunction "C_C") (pintype "passive"))
      (node (ref "B1") (pin "P$2") (pinfunction "P$2_P$2") (pintype "bidirectional"))
      (node (ref "B2") (pin "P$2") (pinfunction "BAT-_P$2") (pintype "bidirectional"))
      (node (ref "B3") (pin "P$1") (pinfunction "P1_P$1") (pintype "bidirectional"))
      (node (ref "C1") (pin "-") (pinfunction "-_-") (pintype "passive"))
      (node (ref "C10") (pin "2") (pinfunction "2_2") (pintype "passive"))
      (node (ref "C11") (pin "2") (pinfunction "2_2") (pintype "passive"))
      (node (ref "C12") (pin "-") (pinfunction "-_-") (pintype "passive"))
      (node (ref "C13") (pin "-") (pinfunction "-_-") (pintype "passive"))
      (node (ref "C14") (pin "2") (pinfunction "2_2") (pintype "passive"))
      (node (ref "C15") (pin "-") (pinfunction "-_-") (pintype "passive"))
      (node (ref "C16") (pin "2") (pinfunction "2_2") (pintype "passive"))
      (node (ref "C18") (pin "2") (pinfunction "2_2") (pintype "passive"))
      (node (ref "C2") (pin "2") (pinfunction "2_2") (pintype "passive"))
      (node (ref "C20") (pin "-") (pinfunction "-_-") (pintype "passive"))
      (node (ref "C21") (pin "2") (pinfunction "2_2") (pintype "passive"))
      (node (ref "C22") (pin "2") (pinfunction "2_2") (pintype "passive"))
      (node (ref "C25") (pin "-") (pinfunction "-_-") (pintype "passive"))
      (node (ref "C27") (pin "-") (pinfunction "-_-") (pintype "passive"))
      (node (ref "C28") (pin "-") (pinfunction "-_-") (pintype "passive"))
      (node (ref "C3") (pin "2") (pinfunction "2_2") (pintype "passive"))
      (node (ref "C4") (pin "2") (pinfunction "2_2") (pintype "passive"))
      (node (ref "C5") (pin "2") (pinfunction "2_2") (pintype "passive"))
      (node (ref "C6") (pin "2") (pinfunction "2_2") (pintype "passive"))
      (node (ref "C7") (pin "2") (pinfunction "2_2") (pintype "passive"))
      (node (ref "C8") (pin "2") (pinfunction "2_2") (pintype "passive"))
      (node (ref "C9") (pin "2") (pinfunction "2_2") (pintype "passive"))
      (node (ref "DCDC3.3V") (pin "2") (pinfunction "2_2") (pintype "passive"))
      (node (ref "DCDC5V") (pin "2") (pinfunction "2_2") (pintype "passive"))
      (node (ref "ETH1") (pin "P$1") (pinfunction "GND_1_P$1") (pintype "bidirectional"))
      (node (ref "ETH1") (pin "P$12") (pinfunction "GND_3_P$12") (pintype "bidirectional"))
      (node (ref "ETH1") (pin "P$2") (pinfunction "GND_2_P$2") (pintype "bidirectional"))
      (node (ref "G1") (pin "-") (pinfunction "-_-") (pintype "passive"))
      (node (ref "IC1") (pin "7") (pinfunction "GND_7") (pintype "power_in"))
      (node (ref "IC2") (pin "7") (pinfunction "GND_7") (pintype "power_in"))
      (node (ref "IC3") (pin "7") (pinfunction "GND_7") (pintype "power_in"))
      (node (ref "J102") (pin "P$1") (pinfunction "P$1_P$1") (pintype "bidirectional"))
      (node (ref "J102") (pin "P$2") (pinfunction "P$2_P$2") (pintype "bidirectional"))
      (node (ref "J102") (pin "P$3") (pinfunction "P$3_P$3") (pintype "bidirectional"))
      (node (ref "J104") (pin "P$1") (pinfunction "P$1_P$1") (pintype "bidirectional"))
      (node (ref "J104") (pin "P$2") (pinfunction "P$2_P$2") (pintype "bidirectional"))
      (node (ref "J104") (pin "P$3") (pinfunction "P$3_P$3") (pintype "bidirectional"))
      (node (ref "J124") (pin "P$1") (pinfunction "P$1_P$1") (pintype "bidirectional"))
      (node (ref "J124") (pin "P$2") (pinfunction "P$2_P$2") (pintype "bidirectional"))
      (node (ref "J124") (pin "P$3") (pinfunction "P$3_P$3") (pintype "bidirectional"))
      (node (ref "J151") (pin "P$1") (pinfunction "P$1_P$1") (pintype "bidirectional"))
      (node (ref "J151") (pin "P$2") (pinfunction "P$2_P$2") (pintype "bidirectional"))
      (node (ref "J151") (pin "P$3") (pinfunction "P$3_P$3") (pintype "bidirectional"))
      (node (ref "J153") (pin "P$1") (pinfunction "P$1_P$1") (pintype "bidirectional"))
      (node (ref "J153") (pin "P$2") (pinfunction "P$2_P$2") (pintype "bidirectional"))
      (node (ref "J153") (pin "P$3") (pinfunction "P$3_P$3") (pintype "bidirectional"))
      (node (ref "J43") (pin "P$1") (pinfunction "P$1_P$1") (pintype "bidirectional"))
      (node (ref "J5") (pin "2") (pinfunction "2_2") (pintype "passive"))
      (node (ref "J5") (pin "3") (pinfunction "3_3") (pintype "passive"))
      (node (ref "J7") (pin "P$1") (pinfunction "P$1_P$1") (pintype "bidirectional"))
      (node (ref "J7") (pin "P$2") (pinfunction "P$2_P$2") (pintype "bidirectional"))
      (node (ref "J70") (pin "P$1") (pinfunction "P$1_P$1") (pintype "bidirectional"))
      (node (ref "J70") (pin "P$2") (pinfunction "P$2_P$2") (pintype "bidirectional"))
      (node (ref "J72") (pin "P$1") (pinfunction "P$1_P$1") (pintype "bidirectional"))
      (node (ref "J72") (pin "P$2") (pinfunction "P$2_P$2") (pintype "bidirectional"))
      (node (ref "J74") (pin "P$1") (pinfunction "P$1_P$1") (pintype "bidirectional"))
      (node (ref "J74") (pin "P$2") (pinfunction "P$2_P$2") (pintype "bidirectional"))
      (node (ref "J76") (pin "P$1") (pinfunction "P$1_P$1") (pintype "bidirectional"))
      (node (ref "J76") (pin "P$2") (pinfunction "P$2_P$2") (pintype "bidirectional"))
      (node (ref "JP2") (pin "2") (pinfunction "2_2") (pintype "passive"))
      (node (ref "JP3") (pin "2") (pinfunction "2_2") (pintype "passive"))
      (node (ref "L1") (pin "P$20") (pinfunction "GND_1_P$20") (pintype "bidirectional"))
      (node (ref "L1") (pin "P$22") (pinfunction "GND_2_P$22") (pintype "bidirectional"))
      (node (ref "L1") (pin "P$60") (pinfunction "GND_3_P$60") (pintype "bidirectional"))
      (node (ref "L1") (pin "P$62") (pinfunction "GND_4_P$62") (pintype "bidirectional"))
      (node (ref "LED18") (pin "C") (pinfunction "C_C") (pintype "passive"))
      (node (ref "P1") (pin "2") (pinfunction "2_2") (pintype "bidirectional"))
      (node (ref "P2") (pin "2") (pinfunction "2_2") (pintype "bidirectional"))
      (node (ref "POWER") (pin "1") (pinfunction "1_1") (pintype "passive"))
      (node (ref "R3") (pin "1") (pinfunction "1_1") (pintype "passive"))
      (node (ref "R32") (pin "2") (pinfunction "2_2") (pintype "passive"))
      (node (ref "R41") (pin "2") (pinfunction "2_2") (pintype "passive"))
      (node (ref "R43") (pin "2") (pinfunction "2_2") (pintype "passive"))
      (node (ref "R7") (pin "1") (pinfunction "1_1") (pintype "passive"))
      (node (ref "S1") (pin "P$1") (pinfunction "P1_P$1") (pintype "bidirectional"))
      (node (ref "S129") (pin "P$1") (pinfunction "P$1_P$1") (pintype "bidirectional"))
      (node (ref "S129") (pin "P$2") (pinfunction "P$2_P$2") (pintype "bidirectional"))
      (node (ref "S129") (pin "P$3") (pinfunction "P$3_P$3") (pintype "bidirectional"))
      (node (ref "S129") (pin "P$4") (pinfunction "P$4_P$4") (pintype "bidirectional"))
      (node (ref "S129") (pin "P$5") (pinfunction "P$5_P$5") (pintype "bidirectional"))
      (node (ref "S137") (pin "P$1") (pinfunction "P$1_P$1") (pintype "bidirectional"))
      (node (ref "S137") (pin "P$2") (pinfunction "P$2_P$2") (pintype "bidirectional"))
      (node (ref "S137") (pin "P$3") (pinfunction "P$3_P$3") (pintype "bidirectional"))
      (node (ref "S137") (pin "P$4") (pinfunction "P$4_P$4") (pintype "bidirectional"))
      (node (ref "S137") (pin "P$5") (pinfunction "P$5_P$5") (pintype "bidirectional"))
      (node (ref "S159") (pin "P$1") (pinfunction "P1_P$1") (pintype "bidirectional"))
      (node (ref "S20") (pin "P$1") (pinfunction "P$1_P$1") (pintype "bidirectional"))
      (node (ref "S20") (pin "P$10") (pinfunction "P$10_P$10") (pintype "bidirectional"))
      (node (ref "S20") (pin "P$2") (pinfunction "P$2_P$2") (pintype "bidirectional"))
      (node (ref "S20") (pin "P$3") (pinfunction "P$3_P$3") (pintype "bidirectional"))
      (node (ref "S20") (pin "P$4") (pinfunction "P$4_P$4") (pintype "bidirectional"))
      (node (ref "S20") (pin "P$5") (pinfunction "P$5_P$5") (pintype "bidirectional"))
      (node (ref "S20") (pin "P$6") (pinfunction "P$6_P$6") (pintype "bidirectional"))
      (node (ref "S20") (pin "P$7") (pinfunction "P$7_P$7") (pintype "bidirectional"))
      (node (ref "S20") (pin "P$8") (pinfunction "P$8_P$8") (pintype "bidirectional"))
      (node (ref "S20") (pin "P$9") (pinfunction "P$9_P$9") (pintype "bidirectional"))
      (node (ref "S24") (pin "P$1") (pinfunction "P$1_P$1") (pintype "bidirectional"))
      (node (ref "S24") (pin "P$10") (pinfunction "P$10_P$10") (pintype "bidirectional"))
      (node (ref "S24") (pin "P$2") (pinfunction "P$2_P$2") (pintype "bidirectional"))
      (node (ref "S24") (pin "P$3") (pinfunction "P$3_P$3") (pintype "bidirectional"))
      (node (ref "S24") (pin "P$4") (pinfunction "P$4_P$4") (pintype "bidirectional"))
      (node (ref "S24") (pin "P$5") (pinfunction "P$5_P$5") (pintype "bidirectional"))
      (node (ref "S24") (pin "P$6") (pinfunction "P$6_P$6") (pintype "bidirectional"))
      (node (ref "S24") (pin "P$7") (pinfunction "P$7_P$7") (pintype "bidirectional"))
      (node (ref "S24") (pin "P$8") (pinfunction "P$8_P$8") (pintype "bidirectional"))
      (node (ref "S24") (pin "P$9") (pinfunction "P$9_P$9") (pintype "bidirectional"))
      (node (ref "SV11") (pin "1") (pinfunction "1_1") (pintype "passive"))
      (node (ref "SV12") (pin "1") (pinfunction "1_1") (pintype "passive"))
      (node (ref "SV13") (pin "2") (pinfunction "2_2") (pintype "passive"))
      (node (ref "SV14") (pin "10") (pinfunction "10_10") (pintype "passive"))
      (node (ref "SV14") (pin "12") (pinfunction "12_12") (pintype "passive"))
      (node (ref "SV14") (pin "4") (pinfunction "4_4") (pintype "passive"))
      (node (ref "SV14") (pin "8") (pinfunction "8_8") (pintype "passive"))
      (node (ref "SV15") (pin "1") (pinfunction "1_1") (pintype "passive"))
      (node (ref "SV17") (pin "1") (pinfunction "1_1") (pintype "passive"))
      (node (ref "SV17") (pin "2") (pinfunction "2_2") (pintype "passive"))
      (node (ref "SV19") (pin "1") (pinfunction "1_1") (pintype "passive"))
      (node (ref "SV2") (pin "13") (pinfunction "13_13") (pintype "passive"))
      (node (ref "SV2") (pin "14") (pinfunction "14_14") (pintype "passive"))
      (node (ref "SV2") (pin "19") (pinfunction "19_19") (pintype "passive"))
      (node (ref "SV2") (pin "20") (pinfunction "20_20") (pintype "passive"))
      (node (ref "SV2") (pin "29") (pinfunction "29_29") (pintype "passive"))
      (node (ref "SV2") (pin "30") (pinfunction "30_30") (pintype "passive"))
      (node (ref "SV2") (pin "33") (pinfunction "33_33") (pintype "passive"))
      (node (ref "SV2") (pin "34") (pinfunction "34_34") (pintype "passive"))
      (node (ref "SV2") (pin "5") (pinfunction "5_5") (pintype "passive"))
      (node (ref "SV2") (pin "6") (pinfunction "6_6") (pintype "passive"))
      (node (ref "SV4") (pin "10") (pinfunction "10_10") (pintype "passive"))
      (node (ref "SV4") (pin "25") (pinfunction "25_25") (pintype "passive"))
      (node (ref "SV4") (pin "26") (pinfunction "26_26") (pintype "passive"))
      (node (ref "SV4") (pin "39") (pinfunction "39_39") (pintype "passive"))
      (node (ref "SV4") (pin "40") (pinfunction "40_40") (pintype "passive"))
      (node (ref "SV4") (pin "9") (pinfunction "9_9") (pintype "passive"))
      (node (ref "SV6") (pin "3") (pinfunction "3_3") (pintype "passive"))
      (node (ref "SV6") (pin "4") (pinfunction "4_4") (pintype "passive"))
      (node (ref "T1") (pin "3") (pinfunction "E_3") (pintype "passive"))
      (node (ref "T2") (pin "3") (pinfunction "E_3") (pintype "passive"))
      (node (ref "TRIMPOT1") (pin "5") (pinfunction "5_5") (pintype "passive"))
      (node (ref "TRIMPOT1") (pin "6") (pinfunction "6_6") (pintype "passive"))
      (node (ref "TRIMPOT2") (pin "5") (pinfunction "5_5") (pintype "passive"))
      (node (ref "TRIMPOT2") (pin "6") (pinfunction "6_6") (pintype "passive"))
      (node (ref "U$1") (pin "2") (pinfunction "P2_GND_2") (pintype "bidirectional"))
      (node (ref "U1") (pin "11") (pinfunction "SENSE_11") (pintype "bidirectional"))
      (node (ref "U1") (pin "12") (pinfunction "GND_12") (pintype "bidirectional"))
      (node (ref "U1") (pin "13") (pinfunction "GND_13") (pintype "bidirectional"))
      (node (ref "U1") (pin "4") (pinfunction "GND_4") (pintype "bidirectional"))
      (node (ref "U1") (pin "5") (pinfunction "GND_5") (pintype "bidirectional"))
      (node (ref "U2") (pin "P$15") (pinfunction "GND_P$15") (pintype "bidirectional"))
      (node (ref "U2") (pin "P$16") (pinfunction "PMODE_P$16") (pintype "bidirectional"))
      (node (ref "U2") (pin "P$17") (pinfunction "GND_PAD_P$17") (pintype "bidirectional"))
      (node (ref "U2") (pin "P$7") (pinfunction "IMODE_P$7") (pintype "bidirectional"))
      (node (ref "U2") (pin "P$9") (pinfunction "PGND_P$9") (pintype "bidirectional"))
      (node (ref "U3") (pin "4") (pinfunction "P4_GND_4") (pintype "bidirectional"))
      (node (ref "U4") (pin "P$15") (pinfunction "GND_P$15") (pintype "bidirectional"))
      (node (ref "U4") (pin "P$16") (pinfunction "PMODE_P$16") (pintype "bidirectional"))
      (node (ref "U4") (pin "P$17") (pinfunction "GND_PAD_P$17") (pintype "bidirectional"))
      (node (ref "U4") (pin "P$7") (pinfunction "IMODE_P$7") (pintype "bidirectional"))
      (node (ref "U4") (pin "P$9") (pinfunction "PGND_P$9") (pintype "bidirectional"))
      (node (ref "U5") (pin "11") (pinfunction "SENSE_11") (pintype "bidirectional"))
      (node (ref "U5") (pin "12") (pinfunction "GND_12") (pintype "bidirectional"))
      (node (ref "U5") (pin "13") (pinfunction "GND_13") (pintype "bidirectional"))
      (node (ref "U5") (pin "4") (pinfunction "GND_4") (pintype "bidirectional"))
      (node (ref "U5") (pin "5") (pinfunction "GND_5") (pintype "bidirectional"))
      (node (ref "U6") (pin "P$4") (pinfunction "V-_P$4") (pintype "bidirectional"))
      (node (ref "U7") (pin "4") (pinfunction "GND_4") (pintype "bidirectional"))
      (node (ref "U8") (pin "12") (pinfunction "VSS2_12") (pintype "bidirectional"))
      (node (ref "U8") (pin "2") (pinfunction "VSS_2") (pintype "bidirectional"))
      (node (ref "U8") (pin "23") (pinfunction "VSSA/VREFLO_23") (pintype "bidirectional"))
      (node (ref "U8") (pin "3") (pinfunction "/VREGENZ_3") (pintype "bidirectional"))
    )
    (net (code "51") (name "GPIO0") (class "Default")
      (node (ref "J11") (pin "P$1") (pinfunction "P$1_P$1") (pintype "bidirectional"))
      (node (ref "J11") (pin "P$2") (pinfunction "P$2_P$2") (pintype "bidirectional"))
      (node (ref "J122") (pin "P$1") (pinfunction "P$1_P$1") (pintype "bidirectional"))
      (node (ref "J122") (pin "P$2") (pinfunction "P$2_P$2") (pintype "bidirectional"))
      (node (ref "J122") (pin "P$3") (pinfunction "P$3_P$3") (pintype "bidirectional"))
      (node (ref "L1") (pin "P$40") (pinfunction "GPIO0/EPWM1A_P$40") (pintype "bidirectional"))
    )
    (net (code "52") (name "GPIO1") (class "Default")
      (node (ref "J121") (pin "P$1") (pinfunction "P$1_P$1") (pintype "bidirectional"))
      (node (ref "J121") (pin "P$2") (pinfunction "P$2_P$2") (pintype "bidirectional"))
      (node (ref "J121") (pin "P$3") (pinfunction "P$3_P$3") (pintype "bidirectional"))
      (node (ref "L1") (pin "P$39") (pinfunction "GPIO1/EPWM1B_P$39") (pintype "bidirectional"))
      (node (ref "SV13") (pin "5") (pinfunction "5_5") (pintype "passive"))
    )
    (net (code "53") (name "GPIO2") (class "Default")
      (node (ref "J120") (pin "P$1") (pinfunction "P$1_P$1") (pintype "bidirectional"))
      (node (ref "J120") (pin "P$2") (pinfunction "P$2_P$2") (pintype "bidirectional"))
      (node (ref "J120") (pin "P$3") (pinfunction "P$3_P$3") (pintype "bidirectional"))
      (node (ref "J198") (pin "P$1") (pinfunction "P$1_P$1") (pintype "bidirectional"))
      (node (ref "J198") (pin "P$2") (pinfunction "P$2_P$2") (pintype "bidirectional"))
      (node (ref "L1") (pin "P$38") (pinfunction "GPIO2/EPWM2A_P$38") (pintype "bidirectional"))
    )
    (net (code "54") (name "GPIO3") (class "Default")
      (node (ref "J119") (pin "P$1") (pinfunction "P$1_P$1") (pintype "bidirectional"))
      (node (ref "J119") (pin "P$2") (pinfunction "P$2_P$2") (pintype "bidirectional"))
      (node (ref "J119") (pin "P$3") (pinfunction "P$3_P$3") (pintype "bidirectional"))
      (node (ref "J199") (pin "P$1") (pinfunction "P$1_P$1") (pintype "bidirectional"))
      (node (ref "J199") (pin "P$2") (pinfunction "P$2_P$2") (pintype "bidirectional"))
      (node (ref "L1") (pin "P$37") (pinfunction "GPIO3/EPWM2B_P$37") (pintype "bidirectional"))
    )
    (net (code "55") (name "GPIO4") (class "Default")
      (node (ref "J118") (pin "P$1") (pinfunction "P$1_P$1") (pintype "bidirectional"))
      (node (ref "J118") (pin "P$2") (pinfunction "P$2_P$2") (pintype "bidirectional"))
      (node (ref "J118") (pin "P$3") (pinfunction "P$3_P$3") (pintype "bidirectional"))
      (node (ref "J71") (pin "P$1") (pinfunction "P$1_P$1") (pintype "bidirectional"))
      (node (ref "J71") (pin "P$2") (pinfunction "P$2_P$2") (pintype "bidirectional"))
      (node (ref "L1") (pin "P$36") (pinfunction "GPIO4/EPWM3A_P$36") (pintype "bidirectional"))
    )
    (net (code "56") (name "GPIO5") (class "Default")
      (node (ref "J117") (pin "P$1") (pinfunction "P$1_P$1") (pintype "bidirectional"))
      (node (ref "J117") (pin "P$2") (pinfunction "P$2_P$2") (pintype "bidirectional"))
      (node (ref "J117") (pin "P$3") (pinfunction "P$3_P$3") (pintype "bidirectional"))
      (node (ref "J73") (pin "P$1") (pinfunction "P$1_P$1") (pintype "bidirectional"))
      (node (ref "J73") (pin "P$2") (pinfunction "P$2_P$2") (pintype "bidirectional"))
      (node (ref "L1") (pin "P$35") (pinfunction "GPIO5/EPWM3B_P$35") (pintype "bidirectional"))
    )
    (net (code "57") (name "GPIO6") (class "Default")
      (node (ref "J133") (pin "P$1") (pinfunction "P$1_P$1") (pintype "bidirectional"))
      (node (ref "J133") (pin "P$2") (pinfunction "P$2_P$2") (pintype "bidirectional"))
      (node (ref "J133") (pin "P$3") (pinfunction "P$3_P$3") (pintype "bidirectional"))
      (node (ref "J75") (pin "P$1") (pinfunction "P$1_P$1") (pintype "bidirectional"))
      (node (ref "J75") (pin "P$2") (pinfunction "P$2_P$2") (pintype "bidirectional"))
      (node (ref "L1") (pin "P$80") (pinfunction "GPIO6/EPWM4A_P$80") (pintype "bidirectional"))
    )
    (net (code "58") (name "GPIO7") (class "Default")
      (node (ref "J134") (pin "P$1") (pinfunction "P$1_P$1") (pintype "bidirectional"))
      (node (ref "J134") (pin "P$2") (pinfunction "P$2_P$2") (pintype "bidirectional"))
      (node (ref "J134") (pin "P$3") (pinfunction "P$3_P$3") (pintype "bidirectional"))
      (node (ref "J77") (pin "P$1") (pinfunction "P$1_P$1") (pintype "bidirectional"))
      (node (ref "J77") (pin "P$2") (pinfunction "P$2_P$2") (pintype "bidirectional"))
      (node (ref "L1") (pin "P$79") (pinfunction "GPIO7/EPWM4B_P$79") (pintype "bidirectional"))
    )
    (net (code "59") (name "GPIO8") (class "Default")
      (node (ref "J135") (pin "P$1") (pinfunction "P$1_P$1") (pintype "bidirectional"))
      (node (ref "J135") (pin "P$2") (pinfunction "P$2_P$2") (pintype "bidirectional"))
      (node (ref "J135") (pin "P$3") (pinfunction "P$3_P$3") (pintype "bidirectional"))
      (node (ref "L1") (pin "P$78") (pinfunction "GPIO8/EPWM5A_P$78") (pintype "bidirectional"))
      (node (ref "SV11") (pin "5") (pinfunction "5_5") (pintype "passive"))
    )
    (net (code "60") (name "GPIO9") (class "Default")
      (node (ref "J136") (pin "P$1") (pinfunction "P$1_P$1") (pintype "bidirectional"))
      (node (ref "J136") (pin "P$2") (pinfunction "P$2_P$2") (pintype "bidirectional"))
      (node (ref "J136") (pin "P$3") (pinfunction "P$3_P$3") (pintype "bidirectional"))
      (node (ref "J37") (pin "P$2") (pinfunction "P$2_P$2") (pintype "bidirectional"))
      (node (ref "L1") (pin "P$77") (pinfunction "GPIO9/EPWM5B_P$77") (pintype "bidirectional"))
    )
    (net (code "61") (name "GPIO10") (class "Default")
      (node (ref "J137") (pin "P$1") (pinfunction "P$1_P$1") (pintype "bidirectional"))
      (node (ref "J137") (pin "P$2") (pinfunction "P$2_P$2") (pintype "bidirectional"))
      (node (ref "J137") (pin "P$3") (pinfunction "P$3_P$3") (pintype "bidirectional"))
      (node (ref "J84") (pin "P$1") (pinfunction "P$1_P$1") (pintype "bidirectional"))
      (node (ref "J84") (pin "P$2") (pinfunction "P$2_P$2") (pintype "bidirectional"))
      (node (ref "L1") (pin "P$76") (pinfunction "GPIO10/EPWM6A_P$76") (pintype "bidirectional"))
    )
    (net (code "62") (name "GPIO11") (class "Default")
      (node (ref "J138") (pin "P$1") (pinfunction "P$1_P$1") (pintype "bidirectional"))
      (node (ref "J138") (pin "P$2") (pinfunction "P$2_P$2") (pintype "bidirectional"))
      (node (ref "J138") (pin "P$3") (pinfunction "P$3_P$3") (pintype "bidirectional"))
      (node (ref "J86") (pin "P$1") (pinfunction "P$1_P$1") (pintype "bidirectional"))
      (node (ref "J86") (pin "P$2") (pinfunction "P$2_P$2") (pintype "bidirectional"))
      (node (ref "L1") (pin "P$75") (pinfunction "GPIO11/EPWM6B_P$75") (pintype "bidirectional"))
    )
    (net (code "63") (name "GPIO14") (class "Default")
      (node (ref "J139") (pin "P$1") (pinfunction "P$1_P$1") (pintype "bidirectional"))
      (node (ref "J139") (pin "P$2") (pinfunction "P$2_P$2") (pintype "bidirectional"))
      (node (ref "J139") (pin "P$3") (pinfunction "P$3_P$3") (pintype "bidirectional"))
      (node (ref "J201") (pin "P$1") (pinfunction "P$1_P$1") (pintype "bidirectional"))
      (node (ref "J201") (pin "P$2") (pinfunction "P$2_P$2") (pintype "bidirectional"))
      (node (ref "L1") (pin "P$74") (pinfunction "GPIO14_P$74") (pintype "bidirectional"))
    )
    (net (code "64") (name "GPIO15") (class "Default")
      (node (ref "J140") (pin "P$1") (pinfunction "P$1_P$1") (pintype "bidirectional"))
      (node (ref "J140") (pin "P$2") (pinfunction "P$2_P$2") (pintype "bidirectional"))
      (node (ref "J140") (pin "P$3") (pinfunction "P$3_P$3") (pintype "bidirectional"))
      (node (ref "J202") (pin "P$1") (pinfunction "P$1_P$1") (pintype "bidirectional"))
      (node (ref "J202") (pin "P$2") (pinfunction "P$2_P$2") (pintype "bidirectional"))
      (node (ref "L1") (pin "P$73") (pinfunction "GPIO15_P$73") (pintype "bidirectional"))
    )
    (net (code "65") (name "GPIO16") (class "Default")
      (node (ref "J115") (pin "P$1") (pinfunction "P$1_P$1") (pintype "bidirectional"))
      (node (ref "J115") (pin "P$2") (pinfunction "P$2_P$2") (pintype "bidirectional"))
      (node (ref "J115") (pin "P$3") (pinfunction "P$3_P$3") (pintype "bidirectional"))
      (node (ref "J251") (pin "P$1") (pinfunction "P$1_P$1") (pintype "bidirectional"))
      (node (ref "J251") (pin "P$2") (pinfunction "P$2_P$2") (pintype "bidirectional"))
      (node (ref "L1") (pin "P$33") (pinfunction "GPIO16_P$33") (pintype "bidirectional"))
    )
    (net (code "66") (name "GPIO18") (class "Default")
      (node (ref "J16") (pin "P$1") (pinfunction "P$1_P$1") (pintype "bidirectional"))
      (node (ref "J16") (pin "P$2") (pinfunction "P$2_P$2") (pintype "bidirectional"))
      (node (ref "J16") (pin "P$3") (pinfunction "P$3_P$3") (pintype "bidirectional"))
      (node (ref "L1") (pin "P$4") (pinfunction "GPIO18/SCITXDB_P$4") (pintype "bidirectional"))
      (node (ref "U7") (pin "6") (pinfunction "SCK_6") (pintype "bidirectional"))
    )
    (net (code "67") (name "GPIO19") (class "Default")
      (node (ref "J15") (pin "P$1") (pinfunction "P$1_P$1") (pintype "bidirectional"))
      (node (ref "J15") (pin "P$2") (pinfunction "P$2_P$2") (pintype "bidirectional"))
      (node (ref "J15") (pin "P$3") (pinfunction "P$3_P$3") (pintype "bidirectional"))
      (node (ref "L1") (pin "P$3") (pinfunction "GPIO19/SCIRXDB_P$3") (pintype "bidirectional"))
      (node (ref "U7") (pin "1") (pinfunction "~{CS}_1") (pintype "bidirectional"))
    )
    (net (code "68") (name "GPIO22") (class "Default")
      (node (ref "IC1") (pin "1") (pinfunction "I_1") (pintype "input"))
      (node (ref "J20") (pin "P$1") (pinfunction "P$1_P$1") (pintype "bidirectional"))
      (node (ref "J20") (pin "P$2") (pinfunction "P$2_P$2") (pintype "bidirectional"))
      (node (ref "J20") (pin "P$3") (pinfunction "P$3_P$3") (pintype "bidirectional"))
      (node (ref "L1") (pin "P$8") (pinfunction "GPIO22_P$8") (pintype "bidirectional"))
    )
    (net (code "69") (name "GPIO24") (class "Default")
      (node (ref "J116") (pin "P$1") (pinfunction "P$1_P$1") (pintype "bidirectional"))
      (node (ref "J116") (pin "P$2") (pinfunction "P$2_P$2") (pintype "bidirectional"))
      (node (ref "J116") (pin "P$3") (pinfunction "P$3_P$3") (pintype "bidirectional"))
      (node (ref "J9") (pin "P$1") (pinfunction "P$1_P$1") (pintype "bidirectional"))
      (node (ref "J9") (pin "P$2") (pinfunction "P$2_P$2") (pintype "bidirectional"))
      (node (ref "L1") (pin "P$34") (pinfunction "GPIO24_P$34") (pintype "bidirectional"))
    )
    (net (code "70") (name "GPIO25") (class "Default")
      (node (ref "IC2") (pin "3") (pinfunction "I_3") (pintype "input"))
      (node (ref "J162") (pin "P$1") (pinfunction "P$1_P$1") (pintype "bidirectional"))
      (node (ref "J162") (pin "P$2") (pinfunction "P$2_P$2") (pintype "bidirectional"))
      (node (ref "J162") (pin "P$3") (pinfunction "P$3_P$3") (pintype "bidirectional"))
      (node (ref "L1") (pin "P$51") (pinfunction "GPIO25_P$51") (pintype "bidirectional"))
    )
    (net (code "71") (name "GPIO26") (class "Default")
      (node (ref "IC2") (pin "5") (pinfunction "I_5") (pintype "input"))
      (node (ref "J160") (pin "P$1") (pinfunction "P$1_P$1") (pintype "bidirectional"))
      (node (ref "J160") (pin "P$2") (pinfunction "P$2_P$2") (pintype "bidirectional"))
      (node (ref "J160") (pin "P$3") (pinfunction "P$3_P$3") (pintype "bidirectional"))
      (node (ref "L1") (pin "P$53") (pinfunction "GPIO26_P$53") (pintype "bidirectional"))
    )
    (net (code "72") (name "GPIO27") (class "Default")
      (node (ref "IC2") (pin "9") (pinfunction "I_9") (pintype "input"))
      (node (ref "J161") (pin "P$1") (pinfunction "P$1_P$1") (pintype "bidirectional"))
      (node (ref "J161") (pin "P$2") (pinfunction "P$2_P$2") (pintype "bidirectional"))
      (node (ref "J161") (pin "P$3") (pinfunction "P$3_P$3") (pintype "bidirectional"))
      (node (ref "L1") (pin "P$52") (pinfunction "GPIO27_P$52") (pintype "bidirectional"))
    )
    (net (code "73") (name "GPIO29") (class "Default")
      (node (ref "J29") (pin "P$1") (pinfunction "P$1_P$1") (pintype "bidirectional"))
      (node (ref "J29") (pin "P$2") (pinfunction "P$2_P$2") (pintype "bidirectional"))
      (node (ref "J29") (pin "P$3") (pinfunction "P$3_P$3") (pintype "bidirectional"))
      (node (ref "J85") (pin "P$1") (pinfunction "P$1_P$1") (pintype "bidirectional"))
      (node (ref "J85") (pin "P$2") (pinfunction "P$2_P$2") (pintype "bidirectional"))
      (node (ref "L1") (pin "P$11") (pinfunction "GPIO29_P$11") (pintype "bidirectional"))
    )
    (net (code "74") (name "GPIO32") (class "Default")
      (node (ref "J14") (pin "P$1") (pinfunction "P$1_P$1") (pintype "bidirectional"))
      (node (ref "J14") (pin "P$2") (pinfunction "P$2_P$2") (pintype "bidirectional"))
      (node (ref "J14") (pin "P$3") (pinfunction "P$3_P$3") (pintype "bidirectional"))
      (node (ref "J87") (pin "P$1") (pinfunction "P$1_P$1") (pintype "bidirectional"))
      (node (ref "J87") (pin "P$2") (pinfunction "P$2_P$2") (pintype "bidirectional"))
      (node (ref "L1") (pin "P$2") (pinfunction "GPIO32_P$2") (pintype "bidirectional"))
    )
    (net (code "75") (name "GPIO40") (class "Default")
      (node (ref "J163") (pin "P$1") (pinfunction "P$1_P$1") (pintype "bidirectional"))
      (node (ref "J163") (pin "P$2") (pinfunction "P$2_P$2") (pintype "bidirectional"))
      (node (ref "J163") (pin "P$3") (pinfunction "P$3_P$3") (pintype "bidirectional"))
      (node (ref "J208") (pin "P$1") (pinfunction "P$1_P$1") (pintype "bidirectional"))
      (node (ref "J208") (pin "P$2") (pinfunction "P$2_P$2") (pintype "bidirectional"))
      (node (ref "J42") (pin "P$1") (pinfunction "P$1_P$1") (pintype "bidirectional"))
      (node (ref "J42") (pin "P$2") (pinfunction "P$2_P$2") (pintype "bidirectional"))
      (node (ref "L1") (pin "P$50") (pinfunction "GPIO40/SDAB_P$50") (pintype "bidirectional"))
      (node (ref "R9") (pin "2") (pinfunction "2_2") (pintype "passive"))
    )
    (net (code "76") (name "GPIO41") (class "Default")
      (node (ref "J164") (pin "P$1") (pinfunction "P$1_P$1") (pintype "bidirectional"))
      (node (ref "J164") (pin "P$2") (pinfunction "P$2_P$2") (pintype "bidirectional"))
      (node (ref "J164") (pin "P$3") (pinfunction "P$3_P$3") (pintype "bidirectional"))
      (node (ref "J209") (pin "P$1") (pinfunction "P$1_P$1") (pintype "bidirectional"))
      (node (ref "J209") (pin "P$2") (pinfunction "P$2_P$2") (pintype "bidirectional"))
      (node (ref "J40") (pin "P$1") (pinfunction "P$1_P$1") (pintype "bidirectional"))
      (node (ref "J40") (pin "P$2") (pinfunction "P$2_P$2") (pintype "bidirectional"))
      (node (ref "L1") (pin "P$49") (pinfunction "GPIO41/SCLB_P$49") (pintype "bidirectional"))
      (node (ref "R10") (pin "2") (pinfunction "2_2") (pintype "passive"))
    )
    (net (code "77") (name "GPIO52") (class "Default")
      (node (ref "J165") (pin "P$1") (pinfunction "P$1_P$1") (pintype "bidirectional"))
      (node (ref "J165") (pin "P$2") (pinfunction "P$2_P$2") (pintype "bidirectional"))
      (node (ref "J165") (pin "P$3") (pinfunction "P$3_P$3") (pintype "bidirectional"))
      (node (ref "L1") (pin "P$48") (pinfunction "GPIO52_P$48") (pintype "bidirectional"))
    )
    (net (code "78") (name "GPIO56") (class "Default")
      (node (ref "J169") (pin "P$1") (pinfunction "P$1_P$1") (pintype "bidirectional"))
      (node (ref "J169") (pin "P$2") (pinfunction "P$2_P$2") (pintype "bidirectional"))
      (node (ref "J169") (pin "P$3") (pinfunction "P$3_P$3") (pintype "bidirectional"))
      (node (ref "L1") (pin "P$44") (pinfunction "GPIO56/SCITXDC_P$44") (pintype "bidirectional"))
      (node (ref "SV13") (pin "8") (pinfunction "8_8") (pintype "passive"))
    )
    (net (code "79") (name "GPIO58") (class "Default")
      (node (ref "J33") (pin "P$1") (pinfunction "P$1_P$1") (pintype "bidirectional"))
      (node (ref "J33") (pin "P$2") (pinfunction "P$2_P$2") (pintype "bidirectional"))
      (node (ref "J33") (pin "P$3") (pinfunction "P$3_P$3") (pintype "bidirectional"))
      (node (ref "L1") (pin "P$15") (pinfunction "GPIO58/SPISIMOA_P$15") (pintype "bidirectional"))
      (node (ref "U7") (pin "5") (pinfunction "SI_5") (pintype "bidirectional"))
    )
    (net (code "80") (name "GPIO59") (class "Default")
      (node (ref "J32") (pin "P$1") (pinfunction "P$1_P$1") (pintype "bidirectional"))
      (node (ref "J32") (pin "P$2") (pinfunction "P$2_P$2") (pintype "bidirectional"))
      (node (ref "J32") (pin "P$3") (pinfunction "P$3_P$3") (pintype "bidirectional"))
      (node (ref "L1") (pin "P$14") (pinfunction "GPIO59/SPISOMIA_P$14") (pintype "bidirectional"))
      (node (ref "U7") (pin "2") (pinfunction "SO_2") (pintype "bidirectional"))
    )
    (net (code "81") (name "GPIO60") (class "Default")
      (node (ref "IC2") (pin "11") (pinfunction "I_11") (pintype "input"))
      (node (ref "J19") (pin "P$1") (pinfunction "P$1_P$1") (pintype "bidirectional"))
      (node (ref "J19") (pin "P$2") (pinfunction "P$2_P$2") (pintype "bidirectional"))
      (node (ref "J19") (pin "P$3") (pinfunction "P$3_P$3") (pintype "bidirectional"))
      (node (ref "L1") (pin "P$7") (pinfunction "GPIO60/SPICLKA_P$7") (pintype "bidirectional"))
    )
    (net (code "82") (name "GPIO61") (class "Default")
      (node (ref "IC2") (pin "13") (pinfunction "I_13") (pintype "input"))
      (node (ref "J101") (pin "P$1") (pinfunction "P$1_P$1") (pintype "bidirectional"))
      (node (ref "J101") (pin "P$2") (pinfunction "P$2_P$2") (pintype "bidirectional"))
      (node (ref "J101") (pin "P$3") (pinfunction "P$3_P$3") (pintype "bidirectional"))
      (node (ref "L1") (pin "P$19") (pinfunction "GPIO61_P$19") (pintype "bidirectional"))
    )
    (net (code "83") (name "GPIO63") (class "Default")
      (node (ref "J158") (pin "P$1") (pinfunction "P$1_P$1") (pintype "bidirectional"))
      (node (ref "J158") (pin "P$2") (pinfunction "P$2_P$2") (pintype "bidirectional"))
      (node (ref "J158") (pin "P$3") (pinfunction "P$3_P$3") (pintype "bidirectional"))
      (node (ref "J204") (pin "P$1") (pinfunction "P$1_P$1") (pintype "bidirectional"))
      (node (ref "J204") (pin "P$2") (pinfunction "P$2_P$2") (pintype "bidirectional"))
      (node (ref "J36") (pin "P$2") (pinfunction "P$2_P$2") (pintype "bidirectional"))
      (node (ref "L1") (pin "P$55") (pinfunction "GPIO63/SPISIMOB_P$55") (pintype "bidirectional"))
    )
    (net (code "84") (name "GPIO64") (class "Default")
      (node (ref "J159") (pin "P$1") (pinfunction "P$1_P$1") (pintype "bidirectional"))
      (node (ref "J159") (pin "P$2") (pinfunction "P$2_P$2") (pintype "bidirectional"))
      (node (ref "J159") (pin "P$3") (pinfunction "P$3_P$3") (pintype "bidirectional"))
      (node (ref "J205") (pin "P$1") (pinfunction "P$1_P$1") (pintype "bidirectional"))
      (node (ref "J205") (pin "P$2") (pinfunction "P$2_P$2") (pintype "bidirectional"))
      (node (ref "J35") (pin "P$2") (pinfunction "P$2_P$2") (pintype "bidirectional"))
      (node (ref "L1") (pin "P$54") (pinfunction "GPIO64/SPISOMIB_P$54") (pintype "bidirectional"))
    )
    (net (code "85") (name "GPIO65") (class "Default")
      (node (ref "J166") (pin "P$1") (pinfunction "P$1_P$1") (pintype "bidirectional"))
      (node (ref "J166") (pin "P$2") (pinfunction "P$2_P$2") (pintype "bidirectional"))
      (node (ref "J166") (pin "P$3") (pinfunction "P$3_P$3") (pintype "bidirectional"))
      (node (ref "J206") (pin "P$1") (pinfunction "P$1_P$1") (pintype "bidirectional"))
      (node (ref "J206") (pin "P$2") (pinfunction "P$2_P$2") (pintype "bidirectional"))
      (node (ref "J38") (pin "P$2") (pinfunction "P$2_P$2") (pintype "bidirectional"))
      (node (ref "L1") (pin "P$47") (pinfunction "GPIO65/SPICLKB_P$47") (pintype "bidirectional"))
    )
    (net (code "86") (name "GPIO66") (class "Default")
      (node (ref "J154") (pin "P$1") (pinfunction "P$1_P$1") (pintype "bidirectional"))
      (node (ref "J154") (pin "P$2") (pinfunction "P$2_P$2") (pintype "bidirectional"))
      (node (ref "J154") (pin "P$3") (pinfunction "P$3_P$3") (pintype "bidirectional"))
      (node (ref "J207") (pin "P$1") (pinfunction "P$1_P$1") (pintype "bidirectional"))
      (node (ref "J207") (pin "P$2") (pinfunction "P$2_P$2") (pintype "bidirectional"))
      (node (ref "L1") (pin "P$59") (pinfunction "GPIO66_P$59") (pintype "bidirectional"))
    )
    (net (code "87") (name "GPIO67") (class "Default")
      (node (ref "J17") (pin "P$1") (pinfunction "P$1_P$1") (pintype "bidirectional"))
      (node (ref "J17") (pin "P$2") (pinfunction "P$2_P$2") (pintype "bidirectional"))
      (node (ref "J17") (pin "P$3") (pinfunction "P$3_P$3") (pintype "bidirectional"))
      (node (ref "L1") (pin "P$5") (pinfunction "GPIO67_P$5") (pintype "bidirectional"))
    )
    (net (code "88") (name "GPIO94") (class "Default")
      (node (ref "IC1") (pin "3") (pinfunction "I_3") (pintype "input"))
      (node (ref "J167") (pin "P$1") (pinfunction "P$1_P$1") (pintype "bidirectional"))
      (node (ref "J167") (pin "P$2") (pinfunction "P$2_P$2") (pintype "bidirectional"))
      (node (ref "J167") (pin "P$3") (pinfunction "P$3_P$3") (pintype "bidirectional"))
      (node (ref "L1") (pin "P$46") (pinfunction "GPIO94_P$46") (pintype "bidirectional"))
    )
    (net (code "89") (name "GPIO95") (class "Default")
      (node (ref "IC1") (pin "5") (pinfunction "I_5") (pintype "input"))
      (node (ref "J176") (pin "P$1") (pinfunction "P$1_P$1") (pintype "bidirectional"))
      (node (ref "J176") (pin "P$2") (pinfunction "P$2_P$2") (pintype "bidirectional"))
      (node (ref "J176") (pin "P$3") (pinfunction "P$3_P$3") (pintype "bidirectional"))
      (node (ref "L1") (pin "P$42") (pinfunction "GPIO95_P$42") (pintype "bidirectional"))
    )
    (net (code "90") (name "GPIO97") (class "Default")
      (node (ref "IC1") (pin "9") (pinfunction "I_9") (pintype "input"))
      (node (ref "J168") (pin "P$1") (pinfunction "P$1_P$1") (pintype "bidirectional"))
      (node (ref "J168") (pin "P$2") (pinfunction "P$2_P$2") (pintype "bidirectional"))
      (node (ref "J168") (pin "P$3") (pinfunction "P$3_P$3") (pintype "bidirectional"))
      (node (ref "L1") (pin "P$45") (pinfunction "GPIO97_P$45") (pintype "bidirectional"))
    )
    (net (code "91") (name "GPIO104") (class "Default")
      (node (ref "J28") (pin "P$1") (pinfunction "P$1_P$1") (pintype "bidirectional"))
      (node (ref "J28") (pin "P$2") (pinfunction "P$2_P$2") (pintype "bidirectional"))
      (node (ref "J28") (pin "P$3") (pinfunction "P$3_P$3") (pintype "bidirectional"))
      (node (ref "L1") (pin "P$10") (pinfunction "GPIO104/SDAA_P$10") (pintype "bidirectional"))
    )
    (net (code "92") (name "GPIO105") (class "Default")
      (node (ref "J21") (pin "P$1") (pinfunction "P$1_P$1") (pintype "bidirectional"))
      (node (ref "J21") (pin "P$2") (pinfunction "P$2_P$2") (pintype "bidirectional"))
      (node (ref "J21") (pin "P$3") (pinfunction "P$3_P$3") (pintype "bidirectional"))
      (node (ref "L1") (pin "P$9") (pinfunction "GPIO105/SCLA_P$9") (pintype "bidirectional"))
    )
    (net (code "93") (name "GPIO111") (class "Default")
      (node (ref "IC1") (pin "11") (pinfunction "I_11") (pintype "input"))
      (node (ref "J18") (pin "P$1") (pinfunction "P$1_P$1") (pintype "bidirectional"))
      (node (ref "J18") (pin "P$2") (pinfunction "P$2_P$2") (pintype "bidirectional"))
      (node (ref "J18") (pin "P$3") (pinfunction "P$3_P$3") (pintype "bidirectional"))
      (node (ref "L1") (pin "P$6") (pinfunction "GPIO111_P$6") (pintype "bidirectional"))
    )
    (net (code "94") (name "GPIO122") (class "Default")
      (node (ref "J66") (pin "P$1") (pinfunction "P$1_P$1") (pintype "bidirectional"))
      (node (ref "J66") (pin "P$2") (pinfunction "P$2_P$2") (pintype "bidirectional"))
      (node (ref "J99") (pin "P$1") (pinfunction "P$1_P$1") (pintype "bidirectional"))
      (node (ref "J99") (pin "P$2") (pinfunction "P$2_P$2") (pintype "bidirectional"))
      (node (ref "J99") (pin "P$3") (pinfunction "P$3_P$3") (pintype "bidirectional"))
      (node (ref "L1") (pin "P$17") (pinfunction "GPIO122_P$17") (pintype "bidirectional"))
    )
    (net (code "95") (name "GPIO123") (class "Default")
      (node (ref "J100") (pin "P$1") (pinfunction "P$1_P$1") (pintype "bidirectional"))
      (node (ref "J100") (pin "P$2") (pinfunction "P$2_P$2") (pintype "bidirectional"))
      (node (ref "J100") (pin "P$3") (pinfunction "P$3_P$3") (pintype "bidirectional"))
      (node (ref "J67") (pin "P$1") (pinfunction "P$1_P$1") (pintype "bidirectional"))
      (node (ref "J67") (pin "P$2") (pinfunction "P$2_P$2") (pintype "bidirectional"))
      (node (ref "L1") (pin "P$18") (pinfunction "GPIO123_P$18") (pintype "bidirectional"))
    )
    (net (code "96") (name "GPIO124") (class "Default")
      (node (ref "J31") (pin "P$1") (pinfunction "P$1_P$1") (pintype "bidirectional"))
      (node (ref "J31") (pin "P$2") (pinfunction "P$2_P$2") (pintype "bidirectional"))
      (node (ref "J31") (pin "P$3") (pinfunction "P$3_P$3") (pintype "bidirectional"))
      (node (ref "J68") (pin "P$1") (pinfunction "P$1_P$1") (pintype "bidirectional"))
      (node (ref "J68") (pin "P$2") (pinfunction "P$2_P$2") (pintype "bidirectional"))
      (node (ref "L1") (pin "P$13") (pinfunction "GPIO124_P$13") (pintype "bidirectional"))
    )
    (net (code "97") (name "GPIO125") (class "Default")
      (node (ref "J30") (pin "P$1") (pinfunction "P$1_P$1") (pintype "bidirectional"))
      (node (ref "J30") (pin "P$2") (pinfunction "P$2_P$2") (pintype "bidirectional"))
      (node (ref "J30") (pin "P$3") (pinfunction "P$3_P$3") (pintype "bidirectional"))
      (node (ref "J69") (pin "P$1") (pinfunction "P$1_P$1") (pintype "bidirectional"))
      (node (ref "J69") (pin "P$2") (pinfunction "P$2_P$2") (pintype "bidirectional"))
      (node (ref "L1") (pin "P$12") (pinfunction "GPIO125_P$12") (pintype "bidirectional"))
    )
    (net (code "98") (name "GPIO130") (class "Default")
      (node (ref "IC1") (pin "13") (pinfunction "I_13") (pintype "input"))
      (node (ref "J156") (pin "P$1") (pinfunction "P$1_P$1") (pintype "bidirectional"))
      (node (ref "J156") (pin "P$2") (pinfunction "P$2_P$2") (pintype "bidirectional"))
      (node (ref "J156") (pin "P$3") (pinfunction "P$3_P$3") (pintype "bidirectional"))
      (node (ref "L1") (pin "P$57") (pinfunction "GPIO130_P$57") (pintype "bidirectional"))
    )
    (net (code "99") (name "GPIO131") (class "Default")
      (node (ref "IC2") (pin "1") (pinfunction "I_1") (pintype "input"))
      (node (ref "J155") (pin "P$1") (pinfunction "P$1_P$1") (pintype "bidirectional"))
      (node (ref "J155") (pin "P$2") (pinfunction "P$2_P$2") (pintype "bidirectional"))
      (node (ref "J155") (pin "P$3") (pinfunction "P$3_P$3") (pintype "bidirectional"))
      (node (ref "L1") (pin "P$58") (pinfunction "GPIO131_P$58") (pintype "bidirectional"))
    )
    (net (code "100") (name "GPIO139") (class "Default")
      (node (ref "J170") (pin "P$1") (pinfunction "P$1_P$1") (pintype "bidirectional"))
      (node (ref "J170") (pin "P$2") (pinfunction "P$2_P$2") (pintype "bidirectional"))
      (node (ref "J170") (pin "P$3") (pinfunction "P$3_P$3") (pintype "bidirectional"))
      (node (ref "L1") (pin "P$43") (pinfunction "GPIO139/SCIRXDC_P$43") (pintype "bidirectional"))
      (node (ref "SV13") (pin "1") (pinfunction "1_1") (pintype "passive"))
    )
    (net (code "101") (name "GPIO157") (class "Default")
      (node (ref "IC3") (pin "1") (pinfunction "I_1") (pintype "input"))
      (node (ref "J141") (pin "P$1") (pinfunction "P$1_P$1") (pintype "bidirectional"))
      (node (ref "J141") (pin "P$2") (pinfunction "P$2_P$2") (pintype "bidirectional"))
      (node (ref "J141") (pin "P$3") (pinfunction "P$3_P$3") (pintype "bidirectional"))
      (node (ref "L1") (pin "P$72") (pinfunction "DAC3_P$72") (pintype "bidirectional"))
    )
    (net (code "102") (name "GPIO158") (class "Default")
      (node (ref "IC3") (pin "3") (pinfunction "I_3") (pintype "input"))
      (node (ref "J142") (pin "P$1") (pinfunction "P$1_P$1") (pintype "bidirectional"))
      (node (ref "J142") (pin "P$2") (pinfunction "P$2_P$2") (pintype "bidirectional"))
      (node (ref "J142") (pin "P$3") (pinfunction "P$3_P$3") (pintype "bidirectional"))
      (node (ref "L1") (pin "P$71") (pinfunction "DAC4_P$71") (pintype "bidirectional"))
    )
    (net (code "103") (name "GPIO159") (class "Default")
      (node (ref "IC3") (pin "5") (pinfunction "I_5") (pintype "input"))
      (node (ref "J114") (pin "P$1") (pinfunction "P$1_P$1") (pintype "bidirectional"))
      (node (ref "J114") (pin "P$2") (pinfunction "P$2_P$2") (pintype "bidirectional"))
      (node (ref "J114") (pin "P$3") (pinfunction "P$3_P$3") (pintype "bidirectional"))
      (node (ref "L1") (pin "P$32") (pinfunction "DAC1_P$32") (pintype "bidirectional"))
    )
    (net (code "104") (name "GPIO160") (class "Default")
      (node (ref "IC3") (pin "9") (pinfunction "I_9") (pintype "input"))
      (node (ref "J113") (pin "P$1") (pinfunction "P$1_P$1") (pintype "bidirectional"))
      (node (ref "J113") (pin "P$2") (pinfunction "P$2_P$2") (pintype "bidirectional"))
      (node (ref "J113") (pin "P$3") (pinfunction "P$3_P$3") (pintype "bidirectional"))
      (node (ref "L1") (pin "P$31") (pinfunction "DAC2_P$31") (pintype "bidirectional"))
    )
    (net (code "105") (name "MENABLE") (class "Default")
      (node (ref "S159") (pin "P$2") (pinfunction "P2_P$2") (pintype "bidirectional"))
      (node (ref "U2") (pin "P$3") (pinfunction "NSLEEP_P$3") (pintype "bidirectional"))
      (node (ref "U4") (pin "P$3") (pinfunction "NSLEEP_P$3") (pintype "bidirectional"))
    )
    (net (code "106") (name "MOTOR1+") (class "Default")
      (node (ref "SV3") (pin "1") (pinfunction "1_1") (pintype "passive"))
      (node (ref "SV3") (pin "3") (pinfunction "3_3") (pintype "passive"))
      (node (ref "SV3") (pin "5") (pinfunction "5_5") (pintype "passive"))
      (node (ref "U1") (pin "15") (pinfunction "OUTB_15") (pintype "bidirectional"))
    )
    (net (code "107") (name "MOTOR1-") (class "Default")
      (node (ref "SV3") (pin "2") (pinfunction "2_2") (pintype "passive"))
      (node (ref "SV3") (pin "4") (pinfunction "4_4") (pintype "passive"))
      (node (ref "SV3") (pin "6") (pinfunction "6_6") (pintype "passive"))
      (node (ref "U1") (pin "10") (pinfunction "OUTA_10") (pintype "bidirectional"))
    )
    (net (code "108") (name "MOTOR2+") (class "Default")
      (node (ref "SV1") (pin "1") (pinfunction "1_1") (pintype "passive"))
      (node (ref "SV1") (pin "3") (pinfunction "3_3") (pintype "passive"))
      (node (ref "SV1") (pin "5") (pinfunction "5_5") (pintype "passive"))
      (node (ref "U5") (pin "15") (pinfunction "OUTB_15") (pintype "bidirectional"))
    )
    (net (code "109") (name "MOTOR2-") (class "Default")
      (node (ref "SV1") (pin "2") (pinfunction "2_2") (pintype "passive"))
      (node (ref "SV1") (pin "4") (pinfunction "4_4") (pintype "passive"))
      (node (ref "SV1") (pin "6") (pinfunction "6_6") (pintype "passive"))
      (node (ref "U5") (pin "10") (pinfunction "OUTA_10") (pintype "bidirectional"))
    )
    (net (code "110") (name "MSP430_SCL") (class "Default")
      (node (ref "J39") (pin "P$1") (pinfunction "P$1_P$1") (pintype "bidirectional"))
      (node (ref "J39") (pin "P$2") (pinfunction "P$2_P$2") (pintype "bidirectional"))
      (node (ref "SV17") (pin "13") (pinfunction "13_13") (pintype "passive"))
      (node (ref "SV17") (pin "14") (pinfunction "14_14") (pintype "passive"))
      (node (ref "SV19") (pin "7") (pinfunction "7_7") (pintype "passive"))
    )
    (net (code "111") (name "MSP430_SDA") (class "Default")
      (node (ref "J41") (pin "P$1") (pinfunction "P$1_P$1") (pintype "bidirectional"))
      (node (ref "J41") (pin "P$2") (pinfunction "P$2_P$2") (pintype "bidirectional"))
      (node (ref "SV17") (pin "11") (pinfunction "11_11") (pintype "passive"))
      (node (ref "SV17") (pin "12") (pinfunction "12_12") (pintype "passive"))
      (node (ref "SV19") (pin "6") (pinfunction "6_6") (pintype "passive"))
    )
    (net (code "112") (name "Net-(3V3-PadA)") (class "Default")
      (node (ref "3V3") (pin "A") (pinfunction "A_A") (pintype "passive"))
      (node (ref "R27") (pin "1") (pinfunction "1_1") (pintype "passive"))
    )
    (net (code "113") (name "Net-(5V-PadA)") (class "Default")
      (node (ref "5V") (pin "A") (pinfunction "A_A") (pintype "passive"))
      (node (ref "R26") (pin "1") (pinfunction "1_1") (pintype "passive"))
    )
    (net (code "114") (name "Net-(B1-PadP$1)") (class "Default")
      (node (ref "B1") (pin "P$1") (pinfunction "P$1_P$1") (pintype "bidirectional"))
      (node (ref "R40") (pin "2") (pinfunction "2_2") (pintype "passive"))
    )
    (net (code "115") (name "Net-(B4-P1)") (class "Default")
      (node (ref "B4") (pin "P$1") (pinfunction "P1_P$1") (pintype "bidirectional"))
      (node (ref "SV10") (pin "1") (pinfunction "1_1") (pintype "passive"))
      (node (ref "U6") (pin "P$1") (pinfunction "IN1_P$1") (pintype "bidirectional"))
    )
    (net (code "116") (name "Net-(B5-P1)") (class "Default")
      (node (ref "B5") (pin "P$1") (pinfunction "P1_P$1") (pintype "bidirectional"))
      (node (ref "SV9") (pin "2") (pinfunction "2_2") (pintype "passive"))
      (node (ref "U6") (pin "P$6") (pinfunction "OUT2_P$6") (pintype "bidirectional"))
    )
    (net (code "117") (name "Net-(ETH1-INT{slash})") (class "Default")
      (node (ref "ETH1") (pin "P$6") (pinfunction "INT/_P$6") (pintype "bidirectional"))
      (node (ref "SV5") (pin "7") (pinfunction "7_7") (pintype "passive"))
      (node (ref "SV5") (pin "8") (pinfunction "8_8") (pintype "passive"))
    )
    (net (code "118") (name "Net-(ETH1-MISO)") (class "Default")
      (node (ref "ETH1") (pin "P$7") (pinfunction "MISO_P$7") (pintype "bidirectional"))
      (node (ref "SV5") (pin "10") (pinfunction "10_10") (pintype "passive"))
      (node (ref "SV5") (pin "9") (pinfunction "9_9") (pintype "passive"))
    )
    (net (code "119") (name "Net-(ETH1-MOSI)") (class "Default")
      (node (ref "ETH1") (pin "P$3") (pinfunction "MOSI_P$3") (pintype "bidirectional"))
      (node (ref "SV6") (pin "10") (pinfunction "10_10") (pintype "passive"))
      (node (ref "SV6") (pin "9") (pinfunction "9_9") (pintype "passive"))
    )
    (net (code "120") (name "Net-(ETH1-RESET)") (class "Default")
      (node (ref "ETH1") (pin "P$8") (pinfunction "RESET_P$8") (pintype "bidirectional"))
      (node (ref "SV6") (pin "7") (pinfunction "7_7") (pintype "passive"))
      (node (ref "SV6") (pin "8") (pinfunction "8_8") (pintype "passive"))
    )
    (net (code "121") (name "Net-(ETH1-SCLK)") (class "Default")
      (node (ref "ETH1") (pin "P$4") (pinfunction "SCLK_P$4") (pintype "bidirectional"))
      (node (ref "SV6") (pin "11") (pinfunction "11_11") (pintype "passive"))
      (node (ref "SV6") (pin "12") (pinfunction "12_12") (pintype "passive"))
    )
    (net (code "122") (name "Net-(ETH1-SS{slash})") (class "Default")
      (node (ref "ETH1") (pin "P$5") (pinfunction "SS/_P$5") (pintype "bidirectional"))
      (node (ref "SV5") (pin "11") (pinfunction "11_11") (pintype "passive"))
      (node (ref "SV5") (pin "12") (pinfunction "12_12") (pintype "passive"))
    )
    (net (code "123") (name "Net-(IC1A-O)") (class "Default")
      (node (ref "IC1") (pin "2") (pinfunction "O_2") (pintype "output"))
      (node (ref "LED1") (pin "C") (pinfunction "C_C") (pintype "passive"))
    )
    (net (code "124") (name "Net-(IC1B-O)") (class "Default")
      (node (ref "IC1") (pin "4") (pinfunction "O_4") (pintype "output"))
      (node (ref "LED2") (pin "C") (pinfunction "C_C") (pintype "passive"))
    )
    (net (code "125") (name "Net-(IC1C-O)") (class "Default")
      (node (ref "IC1") (pin "6") (pinfunction "O_6") (pintype "output"))
      (node (ref "LED3") (pin "C") (pinfunction "C_C") (pintype "passive"))
    )
    (net (code "126") (name "Net-(IC1D-O)") (class "Default")
      (node (ref "IC1") (pin "8") (pinfunction "O_8") (pintype "output"))
      (node (ref "LED4") (pin "C") (pinfunction "C_C") (pintype "passive"))
    )
    (net (code "127") (name "Net-(IC1E-O)") (class "Default")
      (node (ref "IC1") (pin "10") (pinfunction "O_10") (pintype "output"))
      (node (ref "LED5") (pin "C") (pinfunction "C_C") (pintype "passive"))
    )
    (net (code "128") (name "Net-(IC1F-O)") (class "Default")
      (node (ref "IC1") (pin "12") (pinfunction "O_12") (pintype "output"))
      (node (ref "LED6") (pin "C") (pinfunction "C_C") (pintype "passive"))
    )
    (net (code "129") (name "Net-(IC2A-O)") (class "Default")
      (node (ref "IC2") (pin "2") (pinfunction "O_2") (pintype "output"))
      (node (ref "LED7") (pin "C") (pinfunction "C_C") (pintype "passive"))
    )
    (net (code "130") (name "Net-(IC2B-O)") (class "Default")
      (node (ref "IC2") (pin "4") (pinfunction "O_4") (pintype "output"))
      (node (ref "LED8") (pin "C") (pinfunction "C_C") (pintype "passive"))
    )
    (net (code "131") (name "Net-(IC2C-O)") (class "Default")
      (node (ref "IC2") (pin "6") (pinfunction "O_6") (pintype "output"))
      (node (ref "LED9") (pin "C") (pinfunction "C_C") (pintype "passive"))
    )
    (net (code "132") (name "Net-(IC2D-O)") (class "Default")
      (node (ref "IC2") (pin "8") (pinfunction "O_8") (pintype "output"))
      (node (ref "LED10") (pin "C") (pinfunction "C_C") (pintype "passive"))
    )
    (net (code "133") (name "Net-(IC2E-O)") (class "Default")
      (node (ref "IC2") (pin "10") (pinfunction "O_10") (pintype "output"))
      (node (ref "LED11") (pin "C") (pinfunction "C_C") (pintype "passive"))
    )
    (net (code "134") (name "Net-(IC2F-O)") (class "Default")
      (node (ref "IC2") (pin "12") (pinfunction "O_12") (pintype "output"))
      (node (ref "LED12") (pin "C") (pinfunction "C_C") (pintype "passive"))
    )
    (net (code "135") (name "Net-(IC3A-O)") (class "Default")
      (node (ref "IC3") (pin "2") (pinfunction "O_2") (pintype "output"))
      (node (ref "LED13") (pin "C") (pinfunction "C_C") (pintype "passive"))
    )
    (net (code "136") (name "Net-(IC3B-O)") (class "Default")
      (node (ref "IC3") (pin "4") (pinfunction "O_4") (pintype "output"))
      (node (ref "LED14") (pin "C") (pinfunction "C_C") (pintype "passive"))
    )
    (net (code "137") (name "Net-(IC3C-O)") (class "Default")
      (node (ref "IC3") (pin "6") (pinfunction "O_6") (pintype "output"))
      (node (ref "LED15") (pin "C") (pinfunction "C_C") (pintype "passive"))
    )
    (net (code "138") (name "Net-(IC3D-O)") (class "Default")
      (node (ref "IC3") (pin "8") (pinfunction "O_8") (pintype "output"))
      (node (ref "LED16") (pin "C") (pinfunction "C_C") (pintype "passive"))
    )
    (net (code "139") (name "Net-(IC3E-I)") (class "Default")
      (node (ref "IC3") (pin "11") (pinfunction "I_11") (pintype "input"))
      (node (ref "J194") (pin "P$1") (pinfunction "P$1_P$1") (pintype "bidirectional"))
      (node (ref "J194") (pin "P$2") (pinfunction "P$2_P$2") (pintype "bidirectional"))
    )
    (net (code "140") (name "Net-(IC3E-O)") (class "Default")
      (node (ref "IC3") (pin "10") (pinfunction "O_10") (pintype "output"))
      (node (ref "R40") (pin "1") (pinfunction "1_1") (pintype "passive"))
    )
    (net (code "141") (name "Net-(J6-PadP$1)") (class "Default")
      (node (ref "J6") (pin "P$1") (pinfunction "P$1_P$1") (pintype "bidirectional"))
      (node (ref "J6") (pin "P$2") (pinfunction "P$2_P$2") (pintype "bidirectional"))
      (node (ref "J6") (pin "P$3") (pinfunction "P$3_P$3") (pintype "bidirectional"))
      (node (ref "R1") (pin "1") (pinfunction "1_1") (pintype "passive"))
    )
    (net (code "142") (name "Net-(J12-PadP$1)") (class "Default")
      (node (ref "J12") (pin "P$1") (pinfunction "P$1_P$1") (pintype "bidirectional"))
      (node (ref "J12") (pin "P$2") (pinfunction "P$2_P$2") (pintype "bidirectional"))
    )
    (net (code "143") (name "Net-(J13-PadP$1)") (class "Default")
      (node (ref "J13") (pin "P$1") (pinfunction "P$1_P$1") (pintype "bidirectional"))
      (node (ref "J13") (pin "P$2") (pinfunction "P$2_P$2") (pintype "bidirectional"))
    )
    (net (code "144") (name "Net-(J22-PadP$1)") (class "Default")
      (node (ref "J22") (pin "P$1") (pinfunction "P$1_P$1") (pintype "bidirectional"))
      (node (ref "J22") (pin "P$2") (pinfunction "P$2_P$2") (pintype "bidirectional"))
    )
    (net (code "145") (name "Net-(J24-PadP$1)") (class "Default")
      (node (ref "J24") (pin "P$1") (pinfunction "P$1_P$1") (pintype "bidirectional"))
      (node (ref "J24") (pin "P$2") (pinfunction "P$2_P$2") (pintype "bidirectional"))
      (node (ref "J24") (pin "P$3") (pinfunction "P$3_P$3") (pintype "bidirectional"))
      (node (ref "R2") (pin "1") (pinfunction "1_1") (pintype "passive"))
    )
    (net (code "146") (name "Net-(J43-PadP$2)") (class "Default")
      (node (ref "J43") (pin "P$2") (pinfunction "P$2_P$2") (pintype "bidirectional"))
      (node (ref "P2") (pin "1") (pinfunction "1_1") (pintype "bidirectional"))
      (node (ref "R39") (pin "1") (pinfunction "1_1") (pintype "passive"))
      (node (ref "SV17") (pin "10") (pinfunction "10_10") (pintype "passive"))
      (node (ref "SV17") (pin "9") (pinfunction "9_9") (pintype "passive"))
      (node (ref "SV19") (pin "5") (pinfunction "5_5") (pintype "passive"))
    )
    (net (code "147") (name "Net-(J43-PadP$3)") (class "Default")
      (node (ref "J43") (pin "P$3") (pinfunction "P$3_P$3") (pintype "bidirectional"))
      (node (ref "SV17") (pin "7") (pinfunction "7_7") (pintype "passive"))
      (node (ref "SV17") (pin "8") (pinfunction "8_8") (pintype "passive"))
      (node (ref "SV19") (pin "4") (pinfunction "4_4") (pintype "passive"))
    )
    (net (code "148") (name "Net-(J88-PadP$1)") (class "Default")
      (node (ref "J88") (pin "P$1") (pinfunction "P$1_P$1") (pintype "bidirectional"))
      (node (ref "J91") (pin "P$1") (pinfunction "P$1_P$1") (pintype "bidirectional"))
      (node (ref "J91") (pin "P$2") (pinfunction "P$2_P$2") (pintype "bidirectional"))
    )
    (net (code "149") (name "Net-(J88-PadP$3)") (class "Default")
      (node (ref "J88") (pin "P$3") (pinfunction "P$3_P$3") (pintype "bidirectional"))
      (node (ref "J92") (pin "P$1") (pinfunction "P$1_P$1") (pintype "bidirectional"))
      (node (ref "J92") (pin "P$2") (pinfunction "P$2_P$2") (pintype "bidirectional"))
    )
    (net (code "150") (name "Net-(J88-PadP$4)") (class "Default")
      (node (ref "J88") (pin "P$4") (pinfunction "P$4_P$4") (pintype "bidirectional"))
      (node (ref "J93") (pin "P$1") (pinfunction "P$1_P$1") (pintype "bidirectional"))
      (node (ref "J93") (pin "P$2") (pinfunction "P$2_P$2") (pintype "bidirectional"))
    )
    (net (code "151") (name "Net-(J88-R+)") (class "Default")
      (node (ref "J88") (pin "P$2") (pinfunction "R+_P$2") (pintype "bidirectional"))
      (node (ref "J89") (pin "P$1") (pinfunction "P$1_P$1") (pintype "bidirectional"))
      (node (ref "J89") (pin "P$2") (pinfunction "P$2_P$2") (pintype "bidirectional"))
    )
    (net (code "152") (name "Net-(J88-R-)") (class "Default")
      (node (ref "J88") (pin "P$5") (pinfunction "R-_P$5") (pintype "bidirectional"))
      (node (ref "J90") (pin "P$1") (pinfunction "P$1_P$1") (pintype "bidirectional"))
      (node (ref "J90") (pin "P$2") (pinfunction "P$2_P$2") (pintype "bidirectional"))
    )
    (net (code "153") (name "Net-(LED1-PadA)") (class "Default")
      (node (ref "LED1") (pin "A") (pinfunction "A_A") (pintype "passive"))
      (node (ref "R11") (pin "1") (pinfunction "1_1") (pintype "passive"))
    )
    (net (code "154") (name "Net-(LED2-PadA)") (class "Default")
      (node (ref "LED2") (pin "A") (pinfunction "A_A") (pintype "passive"))
      (node (ref "R12") (pin "1") (pinfunction "1_1") (pintype "passive"))
    )
    (net (code "155") (name "Net-(LED3-PadA)") (class "Default")
      (node (ref "LED3") (pin "A") (pinfunction "A_A") (pintype "passive"))
      (node (ref "R13") (pin "1") (pinfunction "1_1") (pintype "passive"))
    )
    (net (code "156") (name "Net-(LED4-PadA)") (class "Default")
      (node (ref "LED4") (pin "A") (pinfunction "A_A") (pintype "passive"))
      (node (ref "R14") (pin "1") (pinfunction "1_1") (pintype "passive"))
    )
    (net (code "157") (name "Net-(LED5-PadA)") (class "Default")
      (node (ref "LED5") (pin "A") (pinfunction "A_A") (pintype "passive"))
      (node (ref "R15") (pin "1") (pinfunction "1_1") (pintype "passive"))
    )
    (net (code "158") (name "Net-(LED6-PadA)") (class "Default")
      (node (ref "LED6") (pin "A") (pinfunction "A_A") (pintype "passive"))
      (node (ref "R16") (pin "1") (pinfunction "1_1") (pintype "passive"))
    )
    (net (code "159") (name "Net-(LED7-PadA)") (class "Default")
      (node (ref "LED7") (pin "A") (pinfunction "A_A") (pintype "passive"))
      (node (ref "R17") (pin "1") (pinfunction "1_1") (pintype "passive"))
    )
    (net (code "160") (name "Net-(LED8-PadA)") (class "Default")
      (node (ref "LED8") (pin "A") (pinfunction "A_A") (pintype "passive"))
      (node (ref "R19") (pin "1") (pinfunction "1_1") (pintype "passive"))
    )
    (net (code "161") (name "Net-(LED9-PadA)") (class "Default")
      (node (ref "LED9") (pin "A") (pinfunction "A_A") (pintype "passive"))
      (node (ref "R20") (pin "1") (pinfunction "1_1") (pintype "passive"))
    )
    (net (code "162") (name "Net-(LED10-PadA)") (class "Default")
      (node (ref "LED10") (pin "A") (pinfunction "A_A") (pintype "passive"))
      (node (ref "R21") (pin "1") (pinfunction "1_1") (pintype "passive"))
    )
    (net (code "163") (name "Net-(LED11-PadA)") (class "Default")
      (node (ref "LED11") (pin "A") (pinfunction "A_A") (pintype "passive"))
      (node (ref "R22") (pin "1") (pinfunction "1_1") (pintype "passive"))
    )
    (net (code "164") (name "Net-(LED12-PadA)") (class "Default")
      (node (ref "LED12") (pin "A") (pinfunction "A_A") (pintype "passive"))
      (node (ref "R23") (pin "1") (pinfunction "1_1") (pintype "passive"))
    )
    (net (code "165") (name "Net-(LED13-PadA)") (class "Default")
      (node (ref "LED13") (pin "A") (pinfunction "A_A") (pintype "passive"))
      (node (ref "R28") (pin "1") (pinfunction "1_1") (pintype "passive"))
    )
    (net (code "166") (name "Net-(LED14-PadA)") (class "Default")
      (node (ref "LED14") (pin "A") (pinfunction "A_A") (pintype "passive"))
      (node (ref "R29") (pin "1") (pinfunction "1_1") (pintype "passive"))
    )
    (net (code "167") (name "Net-(LED15-PadA)") (class "Default")
      (node (ref "LED15") (pin "A") (pinfunction "A_A") (pintype "passive"))
      (node (ref "R30") (pin "1") (pinfunction "1_1") (pintype "passive"))
    )
    (net (code "168") (name "Net-(LED16-PadA)") (class "Default")
      (node (ref "LED16") (pin "A") (pinfunction "A_A") (pintype "passive"))
      (node (ref "R31") (pin "1") (pinfunction "1_1") (pintype "passive"))
    )
    (net (code "169") (name "Net-(LED17-PadA)") (class "Default")
      (node (ref "LED17") (pin "A") (pinfunction "A_A") (pintype "passive"))
      (node (ref "R36") (pin "1") (pinfunction "1_1") (pintype "passive"))
    )
    (net (code "170") (name "Net-(LED18-PadA)") (class "Default")
      (node (ref "LED18") (pin "A") (pinfunction "A_A") (pintype "passive"))
      (node (ref "R45") (pin "1") (pinfunction "1_1") (pintype "passive"))
    )
    (net (code "171") (name "Net-(R45-Pad2)") (class "Default")
      (node (ref "R45") (pin "2") (pinfunction "2_2") (pintype "passive"))
      (node (ref "SV16") (pin "17") (pinfunction "17_17") (pintype "passive"))
      (node (ref "SV16") (pin "18") (pinfunction "18_18") (pintype "passive"))
      (node (ref "SV18") (pin "9") (pinfunction "9_9") (pintype "passive"))
    )
    (net (code "172") (name "Net-(S1-P3)") (class "Default")
      (node (ref "R24") (pin "1") (pinfunction "1_1") (pintype "passive"))
      (node (ref "S1") (pin "P$3") (pinfunction "P3_P$3") (pintype "bidirectional"))
    )
    (net (code "173") (name "Net-(S130-PadP$1)") (class "Default")
      (node (ref "S130") (pin "P$1") (pinfunction "P$1_P$1") (pintype "bidirectional"))
      (node (ref "S130") (pin "P$2") (pinfunction "P$2_P$2") (pintype "bidirectional"))
      (node (ref "S130") (pin "P$3") (pinfunction "P$3_P$3") (pintype "bidirectional"))
      (node (ref "S130") (pin "P$4") (pinfunction "P$4_P$4") (pintype "bidirectional"))
      (node (ref "S130") (pin "P$5") (pinfunction "P$5_P$5") (pintype "bidirectional"))
    )
    (net (code "174") (name "Net-(S138-PadP$1)") (class "Default")
      (node (ref "S138") (pin "P$1") (pinfunction "P$1_P$1") (pintype "bidirectional"))
      (node (ref "S138") (pin "P$2") (pinfunction "P$2_P$2") (pintype "bidirectional"))
      (node (ref "S138") (pin "P$3") (pinfunction "P$3_P$3") (pintype "bidirectional"))
      (node (ref "S138") (pin "P$4") (pinfunction "P$4_P$4") (pintype "bidirectional"))
      (node (ref "S138") (pin "P$5") (pinfunction "P$5_P$5") (pintype "bidirectional"))
    )
    (net (code "175") (name "Net-(S139-PadP$1)") (class "Default")
      (node (ref "S139") (pin "P$1") (pinfunction "P$1_P$1") (pintype "bidirectional"))
      (node (ref "S139") (pin "P$2") (pinfunction "P$2_P$2") (pintype "bidirectional"))
      (node (ref "S139") (pin "P$3") (pinfunction "P$3_P$3") (pintype "bidirectional"))
      (node (ref "S139") (pin "P$4") (pinfunction "P$4_P$4") (pintype "bidirectional"))
      (node (ref "S139") (pin "P$5") (pinfunction "P$5_P$5") (pintype "bidirectional"))
    )
    (net (code "176") (name "Net-(S147-PadP$1)") (class "Default")
      (node (ref "S147") (pin "P$1") (pinfunction "P$1_P$1") (pintype "bidirectional"))
      (node (ref "S147") (pin "P$2") (pinfunction "P$2_P$2") (pintype "bidirectional"))
      (node (ref "S147") (pin "P$3") (pinfunction "P$3_P$3") (pintype "bidirectional"))
      (node (ref "S147") (pin "P$4") (pinfunction "P$4_P$4") (pintype "bidirectional"))
      (node (ref "S147") (pin "P$5") (pinfunction "P$5_P$5") (pintype "bidirectional"))
    )
    (net (code "177") (name "Net-(S159-P3)") (class "Default")
      (node (ref "R18") (pin "1") (pinfunction "1_1") (pintype "passive"))
      (node (ref "S159") (pin "P$3") (pinfunction "P3_P$3") (pintype "bidirectional"))
    )
    (net (code "178") (name "Net-(S167-PadP$1)") (class "Default")
      (node (ref "S167") (pin "P$1") (pinfunction "P$1_P$1") (pintype "bidirectional"))
      (node (ref "S167") (pin "P$2") (pinfunction "P$2_P$2") (pintype "bidirectional"))
      (node (ref "S167") (pin "P$3") (pinfunction "P$3_P$3") (pintype "bidirectional"))
      (node (ref "S167") (pin "P$4") (pinfunction "P$4_P$4") (pintype "bidirectional"))
      (node (ref "S167") (pin "P$5") (pinfunction "P$5_P$5") (pintype "bidirectional"))
    )
    (net (code "179") (name "Net-(S168-PadP$1)") (class "Default")
      (node (ref "S168") (pin "P$1") (pinfunction "P$1_P$1") (pintype "bidirectional"))
      (node (ref "S168") (pin "P$2") (pinfunction "P$2_P$2") (pintype "bidirectional"))
      (node (ref "S168") (pin "P$3") (pinfunction "P$3_P$3") (pintype "bidirectional"))
      (node (ref "S168") (pin "P$4") (pinfunction "P$4_P$4") (pintype "bidirectional"))
      (node (ref "S168") (pin "P$5") (pinfunction "P$5_P$5") (pintype "bidirectional"))
    )
    (net (code "180") (name "Net-(S169-PadP$1)") (class "Default")
      (node (ref "S169") (pin "P$1") (pinfunction "P$1_P$1") (pintype "bidirectional"))
      (node (ref "S169") (pin "P$2") (pinfunction "P$2_P$2") (pintype "bidirectional"))
      (node (ref "S169") (pin "P$3") (pinfunction "P$3_P$3") (pintype "bidirectional"))
      (node (ref "S169") (pin "P$4") (pinfunction "P$4_P$4") (pintype "bidirectional"))
      (node (ref "S169") (pin "P$5") (pinfunction "P$5_P$5") (pintype "bidirectional"))
    )
    (net (code "181") (name "Net-(S170-PadP$1)") (class "Default")
      (node (ref "S170") (pin "P$1") (pinfunction "P$1_P$1") (pintype "bidirectional"))
      (node (ref "S170") (pin "P$2") (pinfunction "P$2_P$2") (pintype "bidirectional"))
      (node (ref "S170") (pin "P$3") (pinfunction "P$3_P$3") (pintype "bidirectional"))
      (node (ref "S170") (pin "P$4") (pinfunction "P$4_P$4") (pintype "bidirectional"))
      (node (ref "S170") (pin "P$5") (pinfunction "P$5_P$5") (pintype "bidirectional"))
    )
    (net (code "182") (name "Net-(S171-PadP$1)") (class "Default")
      (node (ref "S171") (pin "P$1") (pinfunction "P$1_P$1") (pintype "bidirectional"))
      (node (ref "S171") (pin "P$2") (pinfunction "P$2_P$2") (pintype "bidirectional"))
      (node (ref "S171") (pin "P$3") (pinfunction "P$3_P$3") (pintype "bidirectional"))
      (node (ref "S171") (pin "P$4") (pinfunction "P$4_P$4") (pintype "bidirectional"))
      (node (ref "S171") (pin "P$5") (pinfunction "P$5_P$5") (pintype "bidirectional"))
    )
    (net (code "183") (name "Net-(S172-PadP$1)") (class "Default")
      (node (ref "S172") (pin "P$1") (pinfunction "P$1_P$1") (pintype "bidirectional"))
      (node (ref "S172") (pin "P$2") (pinfunction "P$2_P$2") (pintype "bidirectional"))
      (node (ref "S172") (pin "P$3") (pinfunction "P$3_P$3") (pintype "bidirectional"))
      (node (ref "S172") (pin "P$4") (pinfunction "P$4_P$4") (pintype "bidirectional"))
      (node (ref "S172") (pin "P$5") (pinfunction "P$5_P$5") (pintype "bidirectional"))
    )
    (net (code "184") (name "Net-(S173-PadP$1)") (class "Default")
      (node (ref "S173") (pin "P$1") (pinfunction "P$1_P$1") (pintype "bidirectional"))
      (node (ref "S173") (pin "P$2") (pinfunction "P$2_P$2") (pintype "bidirectional"))
      (node (ref "S173") (pin "P$3") (pinfunction "P$3_P$3") (pintype "bidirectional"))
      (node (ref "S173") (pin "P$4") (pinfunction "P$4_P$4") (pintype "bidirectional"))
      (node (ref "S173") (pin "P$5") (pinfunction "P$5_P$5") (pintype "bidirectional"))
    )
    (net (code "185") (name "Net-(S174-PadP$1)") (class "Default")
      (node (ref "S174") (pin "P$1") (pinfunction "P$1_P$1") (pintype "bidirectional"))
      (node (ref "S174") (pin "P$2") (pinfunction "P$2_P$2") (pintype "bidirectional"))
      (node (ref "S174") (pin "P$3") (pinfunction "P$3_P$3") (pintype "bidirectional"))
      (node (ref "S174") (pin "P$4") (pinfunction "P$4_P$4") (pintype "bidirectional"))
      (node (ref "S174") (pin "P$5") (pinfunction "P$5_P$5") (pintype "bidirectional"))
    )
    (net (code "186") (name "Net-(S175-PadP$1)") (class "Default")
      (node (ref "S175") (pin "P$1") (pinfunction "P$1_P$1") (pintype "bidirectional"))
      (node (ref "S175") (pin "P$2") (pinfunction "P$2_P$2") (pintype "bidirectional"))
      (node (ref "S175") (pin "P$3") (pinfunction "P$3_P$3") (pintype "bidirectional"))
      (node (ref "S175") (pin "P$4") (pinfunction "P$4_P$4") (pintype "bidirectional"))
      (node (ref "S175") (pin "P$5") (pinfunction "P$5_P$5") (pintype "bidirectional"))
    )
    (net (code "187") (name "Net-(S176-PadP$1)") (class "Default")
      (node (ref "S176") (pin "P$1") (pinfunction "P$1_P$1") (pintype "bidirectional"))
      (node (ref "S176") (pin "P$2") (pinfunction "P$2_P$2") (pintype "bidirectional"))
      (node (ref "S176") (pin "P$3") (pinfunction "P$3_P$3") (pintype "bidirectional"))
      (node (ref "S176") (pin "P$4") (pinfunction "P$4_P$4") (pintype "bidirectional"))
      (node (ref "S176") (pin "P$5") (pinfunction "P$5_P$5") (pintype "bidirectional"))
    )
    (net (code "188") (name "Net-(S177-PadP$1)") (class "Default")
      (node (ref "S177") (pin "P$1") (pinfunction "P$1_P$1") (pintype "bidirectional"))
      (node (ref "S177") (pin "P$2") (pinfunction "P$2_P$2") (pintype "bidirectional"))
      (node (ref "S177") (pin "P$3") (pinfunction "P$3_P$3") (pintype "bidirectional"))
      (node (ref "S177") (pin "P$4") (pinfunction "P$4_P$4") (pintype "bidirectional"))
      (node (ref "S177") (pin "P$5") (pinfunction "P$5_P$5") (pintype "bidirectional"))
    )
    (net (code "189") (name "Net-(S178-PadP$1)") (class "Default")
      (node (ref "S178") (pin "P$1") (pinfunction "P$1_P$1") (pintype "bidirectional"))
      (node (ref "S178") (pin "P$2") (pinfunction "P$2_P$2") (pintype "bidirectional"))
      (node (ref "S178") (pin "P$3") (pinfunction "P$3_P$3") (pintype "bidirectional"))
      (node (ref "S178") (pin "P$4") (pinfunction "P$4_P$4") (pintype "bidirectional"))
      (node (ref "S178") (pin "P$5") (pinfunction "P$5_P$5") (pintype "bidirectional"))
    )
    (net (code "190") (name "Net-(S179-PadP$1)") (class "Default")
      (node (ref "S179") (pin "P$1") (pinfunction "P$1_P$1") (pintype "bidirectional"))
      (node (ref "S179") (pin "P$2") (pinfunction "P$2_P$2") (pintype "bidirectional"))
      (node (ref "S179") (pin "P$3") (pinfunction "P$3_P$3") (pintype "bidirectional"))
      (node (ref "S179") (pin "P$4") (pinfunction "P$4_P$4") (pintype "bidirectional"))
      (node (ref "S179") (pin "P$5") (pinfunction "P$5_P$5") (pintype "bidirectional"))
    )
    (net (code "191") (name "Net-(S180-PadP$1)") (class "Default")
      (node (ref "S180") (pin "P$1") (pinfunction "P$1_P$1") (pintype "bidirectional"))
      (node (ref "S180") (pin "P$2") (pinfunction "P$2_P$2") (pintype "bidirectional"))
      (node (ref "S180") (pin "P$3") (pinfunction "P$3_P$3") (pintype "bidirectional"))
      (node (ref "S180") (pin "P$4") (pinfunction "P$4_P$4") (pintype "bidirectional"))
      (node (ref "S180") (pin "P$5") (pinfunction "P$5_P$5") (pintype "bidirectional"))
    )
    (net (code "192") (name "Net-(S181-PadP$1)") (class "Default")
      (node (ref "S181") (pin "P$1") (pinfunction "P$1_P$1") (pintype "bidirectional"))
      (node (ref "S181") (pin "P$2") (pinfunction "P$2_P$2") (pintype "bidirectional"))
      (node (ref "S181") (pin "P$3") (pinfunction "P$3_P$3") (pintype "bidirectional"))
      (node (ref "S181") (pin "P$4") (pinfunction "P$4_P$4") (pintype "bidirectional"))
      (node (ref "S181") (pin "P$5") (pinfunction "P$5_P$5") (pintype "bidirectional"))
    )
    (net (code "193") (name "Net-(S182-PadP$1)") (class "Default")
      (node (ref "S182") (pin "P$1") (pinfunction "P$1_P$1") (pintype "bidirectional"))
      (node (ref "S182") (pin "P$2") (pinfunction "P$2_P$2") (pintype "bidirectional"))
      (node (ref "S182") (pin "P$3") (pinfunction "P$3_P$3") (pintype "bidirectional"))
      (node (ref "S182") (pin "P$4") (pinfunction "P$4_P$4") (pintype "bidirectional"))
      (node (ref "S182") (pin "P$5") (pinfunction "P$5_P$5") (pintype "bidirectional"))
    )
    (net (code "194") (name "Net-(S183-PadP$1)") (class "Default")
      (node (ref "S183") (pin "P$1") (pinfunction "P$1_P$1") (pintype "bidirectional"))
      (node (ref "S183") (pin "P$2") (pinfunction "P$2_P$2") (pintype "bidirectional"))
      (node (ref "S183") (pin "P$3") (pinfunction "P$3_P$3") (pintype "bidirectional"))
      (node (ref "S183") (pin "P$4") (pinfunction "P$4_P$4") (pintype "bidirectional"))
      (node (ref "S183") (pin "P$5") (pinfunction "P$5_P$5") (pintype "bidirectional"))
    )
    (net (code "195") (name "Net-(S184-PadP$1)") (class "Default")
      (node (ref "S184") (pin "P$1") (pinfunction "P$1_P$1") (pintype "bidirectional"))
      (node (ref "S184") (pin "P$2") (pinfunction "P$2_P$2") (pintype "bidirectional"))
      (node (ref "S184") (pin "P$3") (pinfunction "P$3_P$3") (pintype "bidirectional"))
      (node (ref "S184") (pin "P$4") (pinfunction "P$4_P$4") (pintype "bidirectional"))
      (node (ref "S184") (pin "P$5") (pinfunction "P$5_P$5") (pintype "bidirectional"))
    )
    (net (code "196") (name "Net-(S185-PadP$1)") (class "Default")
      (node (ref "S185") (pin "P$1") (pinfunction "P$1_P$1") (pintype "bidirectional"))
      (node (ref "S185") (pin "P$2") (pinfunction "P$2_P$2") (pintype "bidirectional"))
      (node (ref "S185") (pin "P$3") (pinfunction "P$3_P$3") (pintype "bidirectional"))
      (node (ref "S185") (pin "P$4") (pinfunction "P$4_P$4") (pintype "bidirectional"))
      (node (ref "S185") (pin "P$5") (pinfunction "P$5_P$5") (pintype "bidirectional"))
    )
    (net (code "197") (name "Net-(S186-PadP$1)") (class "Default")
      (node (ref "S186") (pin "P$1") (pinfunction "P$1_P$1") (pintype "bidirectional"))
      (node (ref "S186") (pin "P$2") (pinfunction "P$2_P$2") (pintype "bidirectional"))
      (node (ref "S186") (pin "P$3") (pinfunction "P$3_P$3") (pintype "bidirectional"))
      (node (ref "S186") (pin "P$4") (pinfunction "P$4_P$4") (pintype "bidirectional"))
      (node (ref "S186") (pin "P$5") (pinfunction "P$5_P$5") (pintype "bidirectional"))
    )
    (net (code "198") (name "Net-(S187-PadP$1)") (class "Default")
      (node (ref "S187") (pin "P$1") (pinfunction "P$1_P$1") (pintype "bidirectional"))
      (node (ref "S187") (pin "P$2") (pinfunction "P$2_P$2") (pintype "bidirectional"))
      (node (ref "S187") (pin "P$3") (pinfunction "P$3_P$3") (pintype "bidirectional"))
      (node (ref "S187") (pin "P$4") (pinfunction "P$4_P$4") (pintype "bidirectional"))
      (node (ref "S187") (pin "P$5") (pinfunction "P$5_P$5") (pintype "bidirectional"))
    )
    (net (code "199") (name "Net-(S188-PadP$1)") (class "Default")
      (node (ref "S188") (pin "P$1") (pinfunction "P$1_P$1") (pintype "bidirectional"))
      (node (ref "S188") (pin "P$2") (pinfunction "P$2_P$2") (pintype "bidirectional"))
      (node (ref "S188") (pin "P$3") (pinfunction "P$3_P$3") (pintype "bidirectional"))
      (node (ref "S188") (pin "P$4") (pinfunction "P$4_P$4") (pintype "bidirectional"))
      (node (ref "S188") (pin "P$5") (pinfunction "P$5_P$5") (pintype "bidirectional"))
    )
    (net (code "200") (name "Net-(S189-PadP$1)") (class "Default")
      (node (ref "S189") (pin "P$1") (pinfunction "P$1_P$1") (pintype "bidirectional"))
      (node (ref "S189") (pin "P$2") (pinfunction "P$2_P$2") (pintype "bidirectional"))
      (node (ref "S189") (pin "P$3") (pinfunction "P$3_P$3") (pintype "bidirectional"))
      (node (ref "S189") (pin "P$4") (pinfunction "P$4_P$4") (pintype "bidirectional"))
      (node (ref "S189") (pin "P$5") (pinfunction "P$5_P$5") (pintype "bidirectional"))
    )
    (net (code "201") (name "Net-(S210-PadP$1)") (class "Default")
      (node (ref "S210") (pin "P$1") (pinfunction "P$1_P$1") (pintype "bidirectional"))
      (node (ref "S210") (pin "P$2") (pinfunction "P$2_P$2") (pintype "bidirectional"))
      (node (ref "S210") (pin "P$3") (pinfunction "P$3_P$3") (pintype "bidirectional"))
      (node (ref "S210") (pin "P$4") (pinfunction "P$4_P$4") (pintype "bidirectional"))
      (node (ref "S210") (pin "P$5") (pinfunction "P$5_P$5") (pintype "bidirectional"))
    )
    (net (code "202") (name "Net-(S211-PadP$1)") (class "Default")
      (node (ref "S211") (pin "P$1") (pinfunction "P$1_P$1") (pintype "bidirectional"))
      (node (ref "S211") (pin "P$2") (pinfunction "P$2_P$2") (pintype "bidirectional"))
      (node (ref "S211") (pin "P$3") (pinfunction "P$3_P$3") (pintype "bidirectional"))
      (node (ref "S211") (pin "P$4") (pinfunction "P$4_P$4") (pintype "bidirectional"))
      (node (ref "S211") (pin "P$5") (pinfunction "P$5_P$5") (pintype "bidirectional"))
    )
    (net (code "203") (name "Net-(S212-PadP$1)") (class "Default")
      (node (ref "S212") (pin "P$1") (pinfunction "P$1_P$1") (pintype "bidirectional"))
      (node (ref "S212") (pin "P$2") (pinfunction "P$2_P$2") (pintype "bidirectional"))
      (node (ref "S212") (pin "P$3") (pinfunction "P$3_P$3") (pintype "bidirectional"))
      (node (ref "S212") (pin "P$4") (pinfunction "P$4_P$4") (pintype "bidirectional"))
      (node (ref "S212") (pin "P$5") (pinfunction "P$5_P$5") (pintype "bidirectional"))
    )
    (net (code "204") (name "Net-(S213-PadP$1)") (class "Default")
      (node (ref "S213") (pin "P$1") (pinfunction "P$1_P$1") (pintype "bidirectional"))
      (node (ref "S213") (pin "P$2") (pinfunction "P$2_P$2") (pintype "bidirectional"))
      (node (ref "S213") (pin "P$3") (pinfunction "P$3_P$3") (pintype "bidirectional"))
      (node (ref "S213") (pin "P$4") (pinfunction "P$4_P$4") (pintype "bidirectional"))
      (node (ref "S213") (pin "P$5") (pinfunction "P$5_P$5") (pintype "bidirectional"))
    )
    (net (code "205") (name "Net-(S214-PadP$1)") (class "Default")
      (node (ref "S214") (pin "P$1") (pinfunction "P$1_P$1") (pintype "bidirectional"))
      (node (ref "S214") (pin "P$2") (pinfunction "P$2_P$2") (pintype "bidirectional"))
      (node (ref "S214") (pin "P$3") (pinfunction "P$3_P$3") (pintype "bidirectional"))
      (node (ref "S214") (pin "P$4") (pinfunction "P$4_P$4") (pintype "bidirectional"))
      (node (ref "S214") (pin "P$5") (pinfunction "P$5_P$5") (pintype "bidirectional"))
    )
    (net (code "206") (name "Net-(S215-PadP$1)") (class "Default")
      (node (ref "S215") (pin "P$1") (pinfunction "P$1_P$1") (pintype "bidirectional"))
      (node (ref "S215") (pin "P$2") (pinfunction "P$2_P$2") (pintype "bidirectional"))
      (node (ref "S215") (pin "P$3") (pinfunction "P$3_P$3") (pintype "bidirectional"))
      (node (ref "S215") (pin "P$4") (pinfunction "P$4_P$4") (pintype "bidirectional"))
      (node (ref "S215") (pin "P$5") (pinfunction "P$5_P$5") (pintype "bidirectional"))
    )
    (net (code "207") (name "Net-(S216-PadP$1)") (class "Default")
      (node (ref "S216") (pin "P$1") (pinfunction "P$1_P$1") (pintype "bidirectional"))
      (node (ref "S216") (pin "P$2") (pinfunction "P$2_P$2") (pintype "bidirectional"))
      (node (ref "S216") (pin "P$3") (pinfunction "P$3_P$3") (pintype "bidirectional"))
      (node (ref "S216") (pin "P$4") (pinfunction "P$4_P$4") (pintype "bidirectional"))
      (node (ref "S216") (pin "P$5") (pinfunction "P$5_P$5") (pintype "bidirectional"))
    )
    (net (code "208") (name "Net-(S217-PadP$1)") (class "Default")
      (node (ref "S217") (pin "P$1") (pinfunction "P$1_P$1") (pintype "bidirectional"))
      (node (ref "S217") (pin "P$2") (pinfunction "P$2_P$2") (pintype "bidirectional"))
      (node (ref "S217") (pin "P$3") (pinfunction "P$3_P$3") (pintype "bidirectional"))
      (node (ref "S217") (pin "P$4") (pinfunction "P$4_P$4") (pintype "bidirectional"))
      (node (ref "S217") (pin "P$5") (pinfunction "P$5_P$5") (pintype "bidirectional"))
    )
    (net (code "209") (name "Net-(S218-PadP$1)") (class "Default")
      (node (ref "S218") (pin "P$1") (pinfunction "P$1_P$1") (pintype "bidirectional"))
      (node (ref "S218") (pin "P$2") (pinfunction "P$2_P$2") (pintype "bidirectional"))
      (node (ref "S218") (pin "P$3") (pinfunction "P$3_P$3") (pintype "bidirectional"))
      (node (ref "S218") (pin "P$4") (pinfunction "P$4_P$4") (pintype "bidirectional"))
      (node (ref "S218") (pin "P$5") (pinfunction "P$5_P$5") (pintype "bidirectional"))
    )
    (net (code "210") (name "Net-(S219-PadP$1)") (class "Default")
      (node (ref "S219") (pin "P$1") (pinfunction "P$1_P$1") (pintype "bidirectional"))
      (node (ref "S219") (pin "P$2") (pinfunction "P$2_P$2") (pintype "bidirectional"))
      (node (ref "S219") (pin "P$3") (pinfunction "P$3_P$3") (pintype "bidirectional"))
      (node (ref "S219") (pin "P$4") (pinfunction "P$4_P$4") (pintype "bidirectional"))
      (node (ref "S219") (pin "P$5") (pinfunction "P$5_P$5") (pintype "bidirectional"))
    )
    (net (code "211") (name "Net-(S220-PadP$1)") (class "Default")
      (node (ref "S220") (pin "P$1") (pinfunction "P$1_P$1") (pintype "bidirectional"))
      (node (ref "S220") (pin "P$2") (pinfunction "P$2_P$2") (pintype "bidirectional"))
      (node (ref "S220") (pin "P$3") (pinfunction "P$3_P$3") (pintype "bidirectional"))
      (node (ref "S220") (pin "P$4") (pinfunction "P$4_P$4") (pintype "bidirectional"))
      (node (ref "S220") (pin "P$5") (pinfunction "P$5_P$5") (pintype "bidirectional"))
    )
    (net (code "212") (name "Net-(S221-PadP$1)") (class "Default")
      (node (ref "S221") (pin "P$1") (pinfunction "P$1_P$1") (pintype "bidirectional"))
      (node (ref "S221") (pin "P$2") (pinfunction "P$2_P$2") (pintype "bidirectional"))
      (node (ref "S221") (pin "P$3") (pinfunction "P$3_P$3") (pintype "bidirectional"))
      (node (ref "S221") (pin "P$4") (pinfunction "P$4_P$4") (pintype "bidirectional"))
      (node (ref "S221") (pin "P$5") (pinfunction "P$5_P$5") (pintype "bidirectional"))
    )
    (net (code "213") (name "Net-(S222-PadP$1)") (class "Default")
      (node (ref "S222") (pin "P$1") (pinfunction "P$1_P$1") (pintype "bidirectional"))
      (node (ref "S222") (pin "P$2") (pinfunction "P$2_P$2") (pintype "bidirectional"))
      (node (ref "S222") (pin "P$3") (pinfunction "P$3_P$3") (pintype "bidirectional"))
      (node (ref "S222") (pin "P$4") (pinfunction "P$4_P$4") (pintype "bidirectional"))
      (node (ref "S222") (pin "P$5") (pinfunction "P$5_P$5") (pintype "bidirectional"))
    )
    (net (code "214") (name "Net-(S223-PadP$1)") (class "Default")
      (node (ref "S223") (pin "P$1") (pinfunction "P$1_P$1") (pintype "bidirectional"))
      (node (ref "S223") (pin "P$2") (pinfunction "P$2_P$2") (pintype "bidirectional"))
      (node (ref "S223") (pin "P$3") (pinfunction "P$3_P$3") (pintype "bidirectional"))
      (node (ref "S223") (pin "P$4") (pinfunction "P$4_P$4") (pintype "bidirectional"))
      (node (ref "S223") (pin "P$5") (pinfunction "P$5_P$5") (pintype "bidirectional"))
    )
    (net (code "215") (name "Net-(S224-PadP$1)") (class "Default")
      (node (ref "S224") (pin "P$1") (pinfunction "P$1_P$1") (pintype "bidirectional"))
      (node (ref "S224") (pin "P$2") (pinfunction "P$2_P$2") (pintype "bidirectional"))
      (node (ref "S224") (pin "P$3") (pinfunction "P$3_P$3") (pintype "bidirectional"))
      (node (ref "S224") (pin "P$4") (pinfunction "P$4_P$4") (pintype "bidirectional"))
      (node (ref "S224") (pin "P$5") (pinfunction "P$5_P$5") (pintype "bidirectional"))
    )
    (net (code "216") (name "Net-(S225-PadP$1)") (class "Default")
      (node (ref "S225") (pin "P$1") (pinfunction "P$1_P$1") (pintype "bidirectional"))
      (node (ref "S225") (pin "P$2") (pinfunction "P$2_P$2") (pintype "bidirectional"))
      (node (ref "S225") (pin "P$3") (pinfunction "P$3_P$3") (pintype "bidirectional"))
      (node (ref "S225") (pin "P$4") (pinfunction "P$4_P$4") (pintype "bidirectional"))
      (node (ref "S225") (pin "P$5") (pinfunction "P$5_P$5") (pintype "bidirectional"))
    )
    (net (code "217") (name "Net-(S226-PadP$1)") (class "Default")
      (node (ref "S226") (pin "P$1") (pinfunction "P$1_P$1") (pintype "bidirectional"))
      (node (ref "S226") (pin "P$2") (pinfunction "P$2_P$2") (pintype "bidirectional"))
      (node (ref "S226") (pin "P$3") (pinfunction "P$3_P$3") (pintype "bidirectional"))
      (node (ref "S226") (pin "P$4") (pinfunction "P$4_P$4") (pintype "bidirectional"))
      (node (ref "S226") (pin "P$5") (pinfunction "P$5_P$5") (pintype "bidirectional"))
    )
    (net (code "218") (name "Net-(SV2-Pad7)") (class "Default")
      (node (ref "SV2") (pin "7") (pinfunction "7_7") (pintype "passive"))
      (node (ref "SV2") (pin "8") (pinfunction "8_8") (pintype "passive"))
    )
    (net (code "219") (name "Net-(SV2-Pad10)") (class "Default")
      (node (ref "SV2") (pin "10") (pinfunction "10_10") (pintype "passive"))
      (node (ref "SV2") (pin "9") (pinfunction "9_9") (pintype "passive"))
    )
    (net (code "220") (name "Net-(SV2-Pad11)") (class "Default")
      (node (ref "SV2") (pin "11") (pinfunction "11_11") (pintype "passive"))
      (node (ref "SV2") (pin "12") (pinfunction "12_12") (pintype "passive"))
    )
    (net (code "221") (name "Net-(SV2-Pad15)") (class "Default")
      (node (ref "SV2") (pin "15") (pinfunction "15_15") (pintype "passive"))
      (node (ref "SV2") (pin "16") (pinfunction "16_16") (pintype "passive"))
    )
    (net (code "222") (name "Net-(SV2-Pad17)") (class "Default")
      (node (ref "SV2") (pin "17") (pinfunction "17_17") (pintype "passive"))
      (node (ref "SV2") (pin "18") (pinfunction "18_18") (pintype "passive"))
    )
    (net (code "223") (name "Net-(SV2-Pad21)") (class "Default")
      (node (ref "SV2") (pin "21") (pinfunction "21_21") (pintype "passive"))
      (node (ref "SV2") (pin "22") (pinfunction "22_22") (pintype "passive"))
    )
    (net (code "224") (name "Net-(SV2-Pad23)") (class "Default")
      (node (ref "SV2") (pin "23") (pinfunction "23_23") (pintype "passive"))
      (node (ref "SV2") (pin "24") (pinfunction "24_24") (pintype "passive"))
    )
    (net (code "225") (name "Net-(SV2-Pad25)") (class "Default")
      (node (ref "SV2") (pin "25") (pinfunction "25_25") (pintype "passive"))
      (node (ref "SV2") (pin "26") (pinfunction "26_26") (pintype "passive"))
    )
    (net (code "226") (name "Net-(SV2-Pad27)") (class "Default")
      (node (ref "SV2") (pin "27") (pinfunction "27_27") (pintype "passive"))
      (node (ref "SV2") (pin "28") (pinfunction "28_28") (pintype "passive"))
    )
    (net (code "227") (name "Net-(SV2-Pad31)") (class "Default")
      (node (ref "SV2") (pin "31") (pinfunction "31_31") (pintype "passive"))
      (node (ref "SV2") (pin "32") (pinfunction "32_32") (pintype "passive"))
    )
    (net (code "228") (name "Net-(SV2-Pad35)") (class "Default")
      (node (ref "SV2") (pin "35") (pinfunction "35_35") (pintype "passive"))
      (node (ref "SV2") (pin "36") (pinfunction "36_36") (pintype "passive"))
    )
    (net (code "229") (name "Net-(SV2-Pad37)") (class "Default")
      (node (ref "SV2") (pin "37") (pinfunction "37_37") (pintype "passive"))
      (node (ref "SV2") (pin "38") (pinfunction "38_38") (pintype "passive"))
    )
    (net (code "230") (name "Net-(SV2-Pad39)") (class "Default")
      (node (ref "SV2") (pin "39") (pinfunction "39_39") (pintype "passive"))
      (node (ref "SV2") (pin "40") (pinfunction "40_40") (pintype "passive"))
    )
    (net (code "231") (name "Net-(SV4-Pad1)") (class "Default")
      (node (ref "SV4") (pin "1") (pinfunction "1_1") (pintype "passive"))
      (node (ref "SV4") (pin "2") (pinfunction "2_2") (pintype "passive"))
    )
    (net (code "232") (name "Net-(SV4-Pad3)") (class "Default")
      (node (ref "SV4") (pin "3") (pinfunction "3_3") (pintype "passive"))
      (node (ref "SV4") (pin "4") (pinfunction "4_4") (pintype "passive"))
    )
    (net (code "233") (name "Net-(SV4-Pad5)") (class "Default")
      (node (ref "SV4") (pin "5") (pinfunction "5_5") (pintype "passive"))
      (node (ref "SV4") (pin "6") (pinfunction "6_6") (pintype "passive"))
    )
    (net (code "234") (name "Net-(SV4-Pad7)") (class "Default")
      (node (ref "SV4") (pin "7") (pinfunction "7_7") (pintype "passive"))
      (node (ref "SV4") (pin "8") (pinfunction "8_8") (pintype "passive"))
    )
    (net (code "235") (name "Net-(SV4-Pad11)") (class "Default")
      (node (ref "SV4") (pin "11") (pinfunction "11_11") (pintype "passive"))
      (node (ref "SV4") (pin "12") (pinfunction "12_12") (pintype "passive"))
    )
    (net (code "236") (name "Net-(SV4-Pad13)") (class "Default")
      (node (ref "SV4") (pin "13") (pinfunction "13_13") (pintype "passive"))
      (node (ref "SV4") (pin "14") (pinfunction "14_14") (pintype "passive"))
    )
    (net (code "237") (name "Net-(SV4-Pad15)") (class "Default")
      (node (ref "SV4") (pin "15") (pinfunction "15_15") (pintype "passive"))
      (node (ref "SV4") (pin "16") (pinfunction "16_16") (pintype "passive"))
    )
    (net (code "238") (name "Net-(SV4-Pad17)") (class "Default")
      (node (ref "SV4") (pin "17") (pinfunction "17_17") (pintype "passive"))
      (node (ref "SV4") (pin "18") (pinfunction "18_18") (pintype "passive"))
    )
    (net (code "239") (name "Net-(SV4-Pad19)") (class "Default")
      (node (ref "SV4") (pin "19") (pinfunction "19_19") (pintype "passive"))
      (node (ref "SV4") (pin "20") (pinfunction "20_20") (pintype "passive"))
    )
    (net (code "240") (name "Net-(SV4-Pad21)") (class "Default")
      (node (ref "SV4") (pin "21") (pinfunction "21_21") (pintype "passive"))
      (node (ref "SV4") (pin "22") (pinfunction "22_22") (pintype "passive"))
    )
    (net (code "241") (name "Net-(SV4-Pad23)") (class "Default")
      (node (ref "SV4") (pin "23") (pinfunction "23_23") (pintype "passive"))
      (node (ref "SV4") (pin "24") (pinfunction "24_24") (pintype "passive"))
    )
    (net (code "242") (name "Net-(SV4-Pad27)") (class "Default")
      (node (ref "SV4") (pin "27") (pinfunction "27_27") (pintype "passive"))
      (node (ref "SV4") (pin "28") (pinfunction "28_28") (pintype "passive"))
    )
    (net (code "243") (name "Net-(SV4-Pad29)") (class "Default")
      (node (ref "SV4") (pin "29") (pinfunction "29_29") (pintype "passive"))
      (node (ref "SV4") (pin "30") (pinfunction "30_30") (pintype "passive"))
    )
    (net (code "244") (name "Net-(SV4-Pad31)") (class "Default")
      (node (ref "SV4") (pin "31") (pinfunction "31_31") (pintype "passive"))
      (node (ref "SV4") (pin "32") (pinfunction "32_32") (pintype "passive"))
    )
    (net (code "245") (name "Net-(SV4-Pad33)") (class "Default")
      (node (ref "SV4") (pin "33") (pinfunction "33_33") (pintype "passive"))
      (node (ref "SV4") (pin "34") (pinfunction "34_34") (pintype "passive"))
    )
    (net (code "246") (name "Net-(SV4-Pad35)") (class "Default")
      (node (ref "SV4") (pin "35") (pinfunction "35_35") (pintype "passive"))
      (node (ref "SV4") (pin "36") (pinfunction "36_36") (pintype "passive"))
    )
    (net (code "247") (name "Net-(SV4-Pad37)") (class "Default")
      (node (ref "SV4") (pin "37") (pinfunction "37_37") (pintype "passive"))
      (node (ref "SV4") (pin "38") (pinfunction "38_38") (pintype "passive"))
    )
    (net (code "248") (name "Net-(SV5-Pad1)") (class "Default")
      (node (ref "SV5") (pin "1") (pinfunction "1_1") (pintype "passive"))
      (node (ref "SV5") (pin "2") (pinfunction "2_2") (pintype "passive"))
    )
    (net (code "249") (name "Net-(SV5-Pad3)") (class "Default")
      (node (ref "SV5") (pin "3") (pinfunction "3_3") (pintype "passive"))
      (node (ref "SV5") (pin "4") (pinfunction "4_4") (pintype "passive"))
    )
    (net (code "250") (name "Net-(SV5-Pad5)") (class "Default")
      (node (ref "SV5") (pin "5") (pinfunction "5_5") (pintype "passive"))
      (node (ref "SV5") (pin "6") (pinfunction "6_6") (pintype "passive"))
    )
    (net (code "251") (name "Net-(SV6-Pad5)") (class "Default")
      (node (ref "SV6") (pin "5") (pinfunction "5_5") (pintype "passive"))
      (node (ref "SV6") (pin "6") (pinfunction "6_6") (pintype "passive"))
    )
    (net (code "252") (name "Net-(SV16-Pad3)") (class "Default")
      (node (ref "SV16") (pin "3") (pinfunction "3_3") (pintype "passive"))
      (node (ref "SV16") (pin "4") (pinfunction "4_4") (pintype "passive"))
      (node (ref "SV18") (pin "2") (pinfunction "2_2") (pintype "passive"))
    )
    (net (code "253") (name "Net-(SV16-Pad5)") (class "Default")
      (node (ref "SV16") (pin "5") (pinfunction "5_5") (pintype "passive"))
      (node (ref "SV16") (pin "6") (pinfunction "6_6") (pintype "passive"))
      (node (ref "SV18") (pin "3") (pinfunction "3_3") (pintype "passive"))
    )
    (net (code "254") (name "Net-(SV16-Pad7)") (class "Default")
      (node (ref "SV16") (pin "7") (pinfunction "7_7") (pintype "passive"))
      (node (ref "SV16") (pin "8") (pinfunction "8_8") (pintype "passive"))
      (node (ref "SV18") (pin "4") (pinfunction "4_4") (pintype "passive"))
    )
    (net (code "255") (name "Net-(SV16-Pad10)") (class "Default")
      (node (ref "SV16") (pin "10") (pinfunction "10_10") (pintype "passive"))
      (node (ref "SV16") (pin "9") (pinfunction "9_9") (pintype "passive"))
      (node (ref "SV18") (pin "5") (pinfunction "5_5") (pintype "passive"))
    )
    (net (code "256") (name "Net-(SV16-Pad11)") (class "Default")
      (node (ref "SV16") (pin "11") (pinfunction "11_11") (pintype "passive"))
      (node (ref "SV16") (pin "12") (pinfunction "12_12") (pintype "passive"))
      (node (ref "SV18") (pin "6") (pinfunction "6_6") (pintype "passive"))
    )
    (net (code "257") (name "Net-(SV16-Pad13)") (class "Default")
      (node (ref "SV16") (pin "13") (pinfunction "13_13") (pintype "passive"))
      (node (ref "SV16") (pin "14") (pinfunction "14_14") (pintype "passive"))
      (node (ref "SV18") (pin "7") (pinfunction "7_7") (pintype "passive"))
    )
    (net (code "258") (name "Net-(SV16-Pad15)") (class "Default")
      (node (ref "SV16") (pin "15") (pinfunction "15_15") (pintype "passive"))
      (node (ref "SV16") (pin "16") (pinfunction "16_16") (pintype "passive"))
      (node (ref "SV18") (pin "8") (pinfunction "8_8") (pintype "passive"))
    )
    (net (code "259") (name "Net-(SV16-Pad19)") (class "Default")
      (node (ref "SV16") (pin "19") (pinfunction "19_19") (pintype "passive"))
      (node (ref "SV16") (pin "20") (pinfunction "20_20") (pintype "passive"))
      (node (ref "SV18") (pin "10") (pinfunction "10_10") (pintype "passive"))
    )
    (net (code "260") (name "Net-(SV17-Pad3)") (class "Default")
      (node (ref "SV17") (pin "3") (pinfunction "3_3") (pintype "passive"))
      (node (ref "SV17") (pin "4") (pinfunction "4_4") (pintype "passive"))
      (node (ref "SV19") (pin "2") (pinfunction "2_2") (pintype "passive"))
    )
    (net (code "261") (name "Net-(SV17-Pad5)") (class "Default")
      (node (ref "SV17") (pin "5") (pinfunction "5_5") (pintype "passive"))
      (node (ref "SV17") (pin "6") (pinfunction "6_6") (pintype "passive"))
      (node (ref "SV19") (pin "3") (pinfunction "3_3") (pintype "passive"))
    )
    (net (code "262") (name "Net-(SV17-Pad15)") (class "Default")
      (node (ref "SV17") (pin "15") (pinfunction "15_15") (pintype "passive"))
      (node (ref "SV17") (pin "16") (pinfunction "16_16") (pintype "passive"))
      (node (ref "SV19") (pin "8") (pinfunction "8_8") (pintype "passive"))
    )
    (net (code "263") (name "Net-(SV17-Pad17)") (class "Default")
      (node (ref "SV17") (pin "17") (pinfunction "17_17") (pintype "passive"))
      (node (ref "SV17") (pin "18") (pinfunction "18_18") (pintype "passive"))
      (node (ref "SV19") (pin "9") (pinfunction "9_9") (pintype "passive"))
    )
    (net (code "264") (name "Net-(SV17-Pad19)") (class "Default")
      (node (ref "SV17") (pin "19") (pinfunction "19_19") (pintype "passive"))
      (node (ref "SV17") (pin "20") (pinfunction "20_20") (pintype "passive"))
      (node (ref "SV19") (pin "10") (pinfunction "10_10") (pintype "passive"))
    )
    (net (code "265") (name "Net-(T1-B)") (class "Default")
      (node (ref "R1") (pin "2") (pinfunction "2_2") (pintype "passive"))
      (node (ref "T1") (pin "1") (pinfunction "B_1") (pintype "passive"))
    )
    (net (code "266") (name "Net-(T1-C)") (class "Default")
      (node (ref "J4") (pin "P$1") (pinfunction "P$1_P$1") (pintype "bidirectional"))
      (node (ref "J4") (pin "P$2") (pinfunction "P$2_P$2") (pintype "bidirectional"))
      (node (ref "J4") (pin "P$3") (pinfunction "P$3_P$3") (pintype "bidirectional"))
      (node (ref "T1") (pin "2") (pinfunction "C_2") (pintype "passive"))
    )
    (net (code "267") (name "Net-(T2-B)") (class "Default")
      (node (ref "R2") (pin "2") (pinfunction "2_2") (pintype "passive"))
      (node (ref "T2") (pin "1") (pinfunction "B_1") (pintype "passive"))
    )
    (net (code "268") (name "Net-(T2-C)") (class "Default")
      (node (ref "J23") (pin "P$1") (pinfunction "P$1_P$1") (pintype "bidirectional"))
      (node (ref "J23") (pin "P$2") (pinfunction "P$2_P$2") (pintype "bidirectional"))
      (node (ref "J23") (pin "P$3") (pinfunction "P$3_P$3") (pintype "bidirectional"))
      (node (ref "T2") (pin "2") (pinfunction "C_2") (pintype "passive"))
    )
    (net (code "269") (name "Net-(U$1-P3_SCLK)") (class "Default")
      (node (ref "J125") (pin "P$1") (pinfunction "P$1_P$1") (pintype "bidirectional"))
      (node (ref "J125") (pin "P$2") (pinfunction "P$2_P$2") (pintype "bidirectional"))
      (node (ref "J125") (pin "P$3") (pinfunction "P$3_P$3") (pintype "bidirectional"))
      (node (ref "U$1") (pin "3") (pinfunction "P3_SCLK_3") (pintype "bidirectional"))
    )
    (net (code "270") (name "Net-(U$1-P4_SDA{slash}SPIMOSI)") (class "Default")
      (node (ref "J126") (pin "P$1") (pinfunction "P$1_P$1") (pintype "bidirectional"))
      (node (ref "J126") (pin "P$2") (pinfunction "P$2_P$2") (pintype "bidirectional"))
      (node (ref "J126") (pin "P$3") (pinfunction "P$3_P$3") (pintype "bidirectional"))
      (node (ref "U$1") (pin "4") (pinfunction "P4_SDA/SPIMOSI_4") (pintype "bidirectional"))
    )
    (net (code "271") (name "Net-(U$1-P5_EDA{slash}AUX-DA)") (class "Default")
      (node (ref "J127") (pin "P$1") (pinfunction "P$1_P$1") (pintype "bidirectional"))
      (node (ref "J127") (pin "P$2") (pinfunction "P$2_P$2") (pintype "bidirectional"))
      (node (ref "J127") (pin "P$3") (pinfunction "P$3_P$3") (pintype "bidirectional"))
      (node (ref "U$1") (pin "5") (pinfunction "P5_EDA/AUX-DA_5") (pintype "bidirectional"))
    )
    (net (code "272") (name "Net-(U$1-P6_ECL{slash}AUX-CL)") (class "Default")
      (node (ref "J128") (pin "P$1") (pinfunction "P$1_P$1") (pintype "bidirectional"))
      (node (ref "J128") (pin "P$2") (pinfunction "P$2_P$2") (pintype "bidirectional"))
      (node (ref "J128") (pin "P$3") (pinfunction "P$3_P$3") (pintype "bidirectional"))
      (node (ref "U$1") (pin "6") (pinfunction "P6_ECL/AUX-CL_6") (pintype "bidirectional"))
    )
    (net (code "273") (name "Net-(U$1-P7_ADO{slash}SPIMISO)") (class "Default")
      (node (ref "J129") (pin "P$1") (pinfunction "P$1_P$1") (pintype "bidirectional"))
      (node (ref "J129") (pin "P$2") (pinfunction "P$2_P$2") (pintype "bidirectional"))
      (node (ref "J129") (pin "P$3") (pinfunction "P$3_P$3") (pintype "bidirectional"))
      (node (ref "U$1") (pin "7") (pinfunction "P7_ADO/SPIMISO_7") (pintype "bidirectional"))
    )
    (net (code "274") (name "Net-(U$1-P8_INT)") (class "Default")
      (node (ref "J130") (pin "P$1") (pinfunction "P$1_P$1") (pintype "bidirectional"))
      (node (ref "J130") (pin "P$2") (pinfunction "P$2_P$2") (pintype "bidirectional"))
      (node (ref "J130") (pin "P$3") (pinfunction "P$3_P$3") (pintype "bidirectional"))
      (node (ref "U$1") (pin "8") (pinfunction "P8_INT_8") (pintype "bidirectional"))
    )
    (net (code "275") (name "Net-(U$1-P9_NCS)") (class "Default")
      (node (ref "J131") (pin "P$1") (pinfunction "P$1_P$1") (pintype "bidirectional"))
      (node (ref "J131") (pin "P$2") (pinfunction "P$2_P$2") (pintype "bidirectional"))
      (node (ref "J131") (pin "P$3") (pinfunction "P$3_P$3") (pintype "bidirectional"))
      (node (ref "U$1") (pin "9") (pinfunction "P9_NCS_9") (pintype "bidirectional"))
    )
    (net (code "276") (name "Net-(U$1-P10_FSYNC)") (class "Default")
      (node (ref "J132") (pin "P$1") (pinfunction "P$1_P$1") (pintype "bidirectional"))
      (node (ref "J132") (pin "P$2") (pinfunction "P$2_P$2") (pintype "bidirectional"))
      (node (ref "J132") (pin "P$3") (pinfunction "P$3_P$3") (pintype "bidirectional"))
      (node (ref "U$1") (pin "10") (pinfunction "P10_FSYNC_10") (pintype "bidirectional"))
    )
    (net (code "277") (name "Net-(U1-MODE)") (class "Default")
      (node (ref "JP2") (pin "1") (pinfunction "1_1") (pintype "passive"))
      (node (ref "R4") (pin "1") (pinfunction "1_1") (pintype "passive"))
      (node (ref "U1") (pin "14") (pinfunction "MODE_14") (pintype "bidirectional"))
    )
    (net (code "278") (name "Net-(U1-PHASE)") (class "Default")
      (node (ref "J196") (pin "P$1") (pinfunction "P$1_P$1") (pintype "bidirectional"))
      (node (ref "J196") (pin "P$2") (pinfunction "P$2_P$2") (pintype "bidirectional"))
      (node (ref "J25") (pin "P$1") (pinfunction "P$1_P$1") (pintype "bidirectional"))
      (node (ref "J25") (pin "P$2") (pinfunction "P$2_P$2") (pintype "bidirectional"))
      (node (ref "U1") (pin "7") (pinfunction "PHASE_7") (pintype "bidirectional"))
    )
    (net (code "279") (name "Net-(U1-RC)") (class "Default")
      (node (ref "C14") (pin "1") (pinfunction "1_1") (pintype "passive"))
      (node (ref "R3") (pin "2") (pinfunction "2_2") (pintype "passive"))
      (node (ref "U1") (pin "3") (pinfunction "RC_3") (pintype "bidirectional"))
    )
    (net (code "280") (name "Net-(U1-~{BRAKE})") (class "Default")
      (node (ref "R8") (pin "1") (pinfunction "1_1") (pintype "passive"))
      (node (ref "U1") (pin "1") (pinfunction "~{BRAKE}_1") (pintype "bidirectional"))
    )
    (net (code "281") (name "Net-(U2-CPH)") (class "Default")
      (node (ref "C19") (pin "2") (pinfunction "2_2") (pintype "passive"))
      (node (ref "U2") (pin "P$13") (pinfunction "CPH_P$13") (pintype "bidirectional"))
    )
    (net (code "282") (name "Net-(U2-CPL)") (class "Default")
      (node (ref "C19") (pin "1") (pinfunction "1_1") (pintype "passive"))
      (node (ref "U2") (pin "P$14") (pinfunction "CPL_P$14") (pintype "bidirectional"))
    )
    (net (code "283") (name "Net-(U2-IPROPI)") (class "Default")
      (node (ref "R41") (pin "1") (pinfunction "1_1") (pintype "passive"))
      (node (ref "U2") (pin "P$6") (pinfunction "IPROPI_P$6") (pintype "bidirectional"))
    )
    (net (code "284") (name "Net-(U2-NFAULT)") (class "Default")
      (node (ref "J78") (pin "P$1") (pinfunction "P$1_P$1") (pintype "bidirectional"))
      (node (ref "J78") (pin "P$2") (pinfunction "P$2_P$2") (pintype "bidirectional"))
      (node (ref "R42") (pin "2") (pinfunction "2_2") (pintype "passive"))
      (node (ref "U2") (pin "P$4") (pinfunction "NFAULT_P$4") (pintype "bidirectional"))
    )
    (net (code "285") (name "Net-(U2-VCP)") (class "Default")
      (node (ref "C17") (pin "1") (pinfunction "1_1") (pintype "passive"))
      (node (ref "U2") (pin "P$12") (pinfunction "VCP_P$12") (pintype "bidirectional"))
    )
    (net (code "286") (name "Net-(U2-VREF)") (class "Default")
      (node (ref "TRIMPOT1") (pin "3") (pinfunction "3_3") (pintype "passive"))
      (node (ref "TRIMPOT1") (pin "4") (pinfunction "4_4") (pintype "passive"))
      (node (ref "U2") (pin "P$5") (pinfunction "VREF_P$5") (pintype "bidirectional"))
    )
    (net (code "287") (name "Net-(U3-P1_OSCI)") (class "Default")
      (node (ref "Q1") (pin "2") (pinfunction "2_2") (pintype "passive"))
      (node (ref "U3") (pin "1") (pinfunction "P1_OSCI_1") (pintype "bidirectional"))
    )
    (net (code "288") (name "Net-(U3-P2_OSC0)") (class "Default")
      (node (ref "Q1") (pin "1") (pinfunction "1_1") (pintype "passive"))
      (node (ref "U3") (pin "2") (pinfunction "P2_OSC0_2") (pintype "bidirectional"))
    )
    (net (code "289") (name "Net-(U3-P3_VBACK)") (class "Default")
      (node (ref "G1") (pin "+") (pinfunction "+_+") (pintype "passive"))
      (node (ref "U3") (pin "3") (pinfunction "P3_VBACK_3") (pintype "bidirectional"))
    )
    (net (code "290") (name "Net-(U3-P7_IRQ)") (class "Default")
      (node (ref "J1") (pin "P$1") (pinfunction "P$1_P$1") (pintype "bidirectional"))
      (node (ref "J1") (pin "P$2") (pinfunction "P$2_P$2") (pintype "bidirectional"))
      (node (ref "J1") (pin "P$3") (pinfunction "P$3_P$3") (pintype "bidirectional"))
      (node (ref "U3") (pin "7") (pinfunction "P7_IRQ_7") (pintype "bidirectional"))
    )
    (net (code "291") (name "Net-(U4-CPH)") (class "Default")
      (node (ref "C24") (pin "2") (pinfunction "2_2") (pintype "passive"))
      (node (ref "U4") (pin "P$13") (pinfunction "CPH_P$13") (pintype "bidirectional"))
    )
    (net (code "292") (name "Net-(U4-CPL)") (class "Default")
      (node (ref "C24") (pin "1") (pinfunction "1_1") (pintype "passive"))
      (node (ref "U4") (pin "P$14") (pinfunction "CPL_P$14") (pintype "bidirectional"))
    )
    (net (code "293") (name "Net-(U4-IPROPI)") (class "Default")
      (node (ref "R43") (pin "1") (pinfunction "1_1") (pintype "passive"))
      (node (ref "U4") (pin "P$6") (pinfunction "IPROPI_P$6") (pintype "bidirectional"))
    )
    (net (code "294") (name "Net-(U4-NFAULT)") (class "Default")
      (node (ref "J81") (pin "P$1") (pinfunction "P$1_P$1") (pintype "bidirectional"))
      (node (ref "J81") (pin "P$2") (pinfunction "P$2_P$2") (pintype "bidirectional"))
      (node (ref "R44") (pin "2") (pinfunction "2_2") (pintype "passive"))
      (node (ref "U4") (pin "P$4") (pinfunction "NFAULT_P$4") (pintype "bidirectional"))
    )
    (net (code "295") (name "Net-(U4-VCP)") (class "Default")
      (node (ref "C23") (pin "1") (pinfunction "1_1") (pintype "passive"))
      (node (ref "U4") (pin "P$12") (pinfunction "VCP_P$12") (pintype "bidirectional"))
    )
    (net (code "296") (name "Net-(U4-VREF)") (class "Default")
      (node (ref "TRIMPOT2") (pin "3") (pinfunction "3_3") (pintype "passive"))
      (node (ref "TRIMPOT2") (pin "4") (pinfunction "4_4") (pintype "passive"))
      (node (ref "U4") (pin "P$5") (pinfunction "VREF_P$5") (pintype "bidirectional"))
    )
    (net (code "297") (name "Net-(U5-MODE)") (class "Default")
      (node (ref "JP3") (pin "1") (pinfunction "1_1") (pintype "passive"))
      (node (ref "R5") (pin "1") (pinfunction "1_1") (pintype "passive"))
      (node (ref "U5") (pin "14") (pinfunction "MODE_14") (pintype "bidirectional"))
    )
    (net (code "298") (name "Net-(U5-PHASE)") (class "Default")
      (node (ref "J197") (pin "P$1") (pinfunction "P$1_P$1") (pintype "bidirectional"))
      (node (ref "J197") (pin "P$2") (pinfunction "P$2_P$2") (pintype "bidirectional"))
      (node (ref "J34") (pin "P$1") (pinfunction "P$1_P$1") (pintype "bidirectional"))
      (node (ref "J34") (pin "P$2") (pinfunction "P$2_P$2") (pintype "bidirectional"))
      (node (ref "U5") (pin "7") (pinfunction "PHASE_7") (pintype "bidirectional"))
    )
    (net (code "299") (name "Net-(U5-RC)") (class "Default")
      (node (ref "C2") (pin "1") (pinfunction "1_1") (pintype "passive"))
      (node (ref "R7") (pin "2") (pinfunction "2_2") (pintype "passive"))
      (node (ref "U5") (pin "3") (pinfunction "RC_3") (pintype "bidirectional"))
    )
    (net (code "300") (name "Net-(U5-~{BRAKE})") (class "Default")
      (node (ref "R6") (pin "1") (pinfunction "1_1") (pintype "passive"))
      (node (ref "U5") (pin "1") (pinfunction "~{BRAKE}_1") (pintype "bidirectional"))
    )
    (net (code "301") (name "Net-(U6-IN2)") (class "Default")
      (node (ref "SV10") (pin "2") (pinfunction "2_2") (pintype "passive"))
      (node (ref "U6") (pin "P$2") (pinfunction "IN2_P$2") (pintype "bidirectional"))
    )
    (net (code "302") (name "Net-(U6-IN3)") (class "Default")
      (node (ref "SV10") (pin "3") (pinfunction "3_3") (pintype "passive"))
      (node (ref "U6") (pin "P$3") (pinfunction "IN3_P$3") (pintype "bidirectional"))
    )
    (net (code "303") (name "Net-(U6-OUT1)") (class "Default")
      (node (ref "SV9") (pin "1") (pinfunction "1_1") (pintype "passive"))
      (node (ref "U6") (pin "P$7") (pinfunction "OUT1_P$7") (pintype "bidirectional"))
    )
    (net (code "304") (name "Net-(U6-OUT3)") (class "Default")
      (node (ref "SV9") (pin "3") (pinfunction "3_3") (pintype "passive"))
      (node (ref "U6") (pin "P$5") (pinfunction "OUT3_P$5") (pintype "bidirectional"))
    )
    (net (code "305") (name "Net-(U7-~{HOLD})") (class "Default")
      (node (ref "R25") (pin "1") (pinfunction "1_1") (pintype "passive"))
      (node (ref "U7") (pin "7") (pinfunction "~{HOLD}_7") (pintype "bidirectional"))
    )
    (net (code "306") (name "Net-(U8-VDD)") (class "Default")
      (node (ref "C11") (pin "1") (pinfunction "1_1") (pintype "passive"))
      (node (ref "U8") (pin "1") (pinfunction "VDD_1") (pintype "bidirectional"))
    )
    (net (code "307") (name "Net-(U8-VDD2)") (class "Default")
      (node (ref "C8") (pin "1") (pinfunction "1_1") (pintype "passive"))
      (node (ref "U8") (pin "11") (pinfunction "VDD2_11") (pintype "bidirectional"))
    )
    (net (code "308") (name "Net-(U8-{slash}XRS)") (class "Default")
      (node (ref "P1") (pin "1") (pinfunction "1_1") (pintype "bidirectional"))
      (node (ref "R38") (pin "1") (pinfunction "1_1") (pintype "passive"))
      (node (ref "U8") (pin "17") (pinfunction "/XRS_17") (pintype "bidirectional"))
    )
    (net (code "309") (name "POWER") (class "Default")
      (node (ref "B2") (pin "P$1") (pinfunction "BAT+_P$1") (pintype "bidirectional"))
      (node (ref "C1") (pin "+") (pinfunction "+_+") (pintype "passive"))
      (node (ref "C12") (pin "+") (pinfunction "+_+") (pintype "passive"))
      (node (ref "C13") (pin "+") (pinfunction "+_+") (pintype "passive"))
      (node (ref "C15") (pin "+") (pinfunction "+_+") (pintype "passive"))
      (node (ref "C16") (pin "1") (pinfunction "1_1") (pintype "passive"))
      (node (ref "C17") (pin "2") (pinfunction "2_2") (pintype "passive"))
      (node (ref "C20") (pin "+") (pinfunction "+_+") (pintype "passive"))
      (node (ref "C22") (pin "1") (pinfunction "1_1") (pintype "passive"))
      (node (ref "C23") (pin "2") (pinfunction "2_2") (pintype "passive"))
      (node (ref "C25") (pin "+") (pinfunction "+_+") (pintype "passive"))
      (node (ref "C27") (pin "+") (pinfunction "+_+") (pintype "passive"))
      (node (ref "C28") (pin "+") (pinfunction "+_+") (pintype "passive"))
      (node (ref "DCDC3.3V") (pin "1") (pinfunction "1_1") (pintype "passive"))
      (node (ref "DCDC5V") (pin "1") (pinfunction "1_1") (pintype "passive"))
      (node (ref "J5") (pin "1") (pinfunction "1_1") (pintype "passive"))
      (node (ref "POWER") (pin "2") (pinfunction "2_2") (pintype "passive"))
      (node (ref "S141") (pin "P$1") (pinfunction "P$1_P$1") (pintype "bidirectional"))
      (node (ref "S141") (pin "P$2") (pinfunction "P$2_P$2") (pintype "bidirectional"))
      (node (ref "S141") (pin "P$3") (pinfunction "P$3_P$3") (pintype "bidirectional"))
      (node (ref "S141") (pin "P$4") (pinfunction "P$4_P$4") (pintype "bidirectional"))
      (node (ref "S141") (pin "P$5") (pinfunction "P$5_P$5") (pintype "bidirectional"))
      (node (ref "U1") (pin "16") (pinfunction "VBB_16") (pintype "bidirectional"))
      (node (ref "U1") (pin "9") (pinfunction "VBB_9") (pintype "bidirectional"))
      (node (ref "U2") (pin "P$11") (pinfunction "VM_P$11") (pintype "bidirectional"))
      (node (ref "U4") (pin "P$11") (pinfunction "VM_P$11") (pintype "bidirectional"))
      (node (ref "U5") (pin "16") (pinfunction "VBB_16") (pintype "bidirectional"))
      (node (ref "U5") (pin "9") (pinfunction "VBB_9") (pintype "bidirectional"))
    )
    (net (code "310") (name "RESET") (class "Default")
      (node (ref "J98") (pin "P$1") (pinfunction "P$1_P$1") (pintype "bidirectional"))
      (node (ref "J98") (pin "P$2") (pinfunction "P$2_P$2") (pintype "bidirectional"))
      (node (ref "J98") (pin "P$3") (pinfunction "P$3_P$3") (pintype "bidirectional"))
      (node (ref "L1") (pin "P$16") (pinfunction "RST_P$16") (pintype "bidirectional"))
    )
    (net (code "311") (name "RESET_2") (class "Default")
      (node (ref "J157") (pin "P$1") (pinfunction "P$1_P$1") (pintype "bidirectional"))
      (node (ref "J157") (pin "P$2") (pinfunction "P$2_P$2") (pintype "bidirectional"))
      (node (ref "J157") (pin "P$3") (pinfunction "P$3_P$3") (pintype "bidirectional"))
      (node (ref "L1") (pin "P$56") (pinfunction "RST_2_P$56") (pintype "bidirectional"))
    )
    (net (code "312") (name "SCL") (class "Default")
      (node (ref "J2") (pin "P$1") (pinfunction "P$1_P$1") (pintype "bidirectional"))
      (node (ref "J2") (pin "P$2") (pinfunction "P$2_P$2") (pintype "bidirectional"))
      (node (ref "J2") (pin "P$3") (pinfunction "P$3_P$3") (pintype "bidirectional"))
      (node (ref "U3") (pin "6") (pinfunction "P6_SCL_6") (pintype "bidirectional"))
    )
    (net (code "313") (name "SDA") (class "Default")
      (node (ref "J3") (pin "P$1") (pinfunction "P$1_P$1") (pintype "bidirectional"))
      (node (ref "J3") (pin "P$2") (pinfunction "P$2_P$2") (pintype "bidirectional"))
      (node (ref "J3") (pin "P$3") (pinfunction "P$3_P$3") (pintype "bidirectional"))
      (node (ref "U3") (pin "5") (pinfunction "P5_SDA_5") (pintype "bidirectional"))
    )
    (net (code "314") (name "TCK") (class "Default")
      (node (ref "SV14") (pin "11") (pinfunction "11_11") (pintype "passive"))
      (node (ref "SV14") (pin "9") (pinfunction "9_9") (pintype "passive"))
      (node (ref "U8") (pin "31") (pinfunction "GPIO38/XCLKIN(TCK)_31") (pintype "bidirectional"))
    )
    (net (code "315") (name "TDI") (class "Default")
      (node (ref "SV14") (pin "3") (pinfunction "3_3") (pintype "passive"))
      (node (ref "U8") (pin "28") (pinfunction "GPIO35(TDI)_28") (pintype "bidirectional"))
    )
    (net (code "316") (name "TDO") (class "Default")
      (node (ref "R33") (pin "2") (pinfunction "2_2") (pintype "passive"))
      (node (ref "SV14") (pin "7") (pinfunction "7_7") (pintype "passive"))
      (node (ref "U8") (pin "30") (pinfunction "GPIO37(TDO)_30") (pintype "bidirectional"))
    )
    (net (code "317") (name "TMS") (class "Default")
      (node (ref "SV14") (pin "1") (pinfunction "1_1") (pintype "passive"))
      (node (ref "U8") (pin "29") (pinfunction "GPIO36(TMS)_29") (pintype "bidirectional"))
    )
    (net (code "318") (name "TRSTN") (class "Default")
      (node (ref "R32") (pin "1") (pinfunction "1_1") (pintype "passive"))
      (node (ref "SV14") (pin "2") (pinfunction "2_2") (pintype "passive"))
      (node (ref "U8") (pin "16") (pinfunction "/TRST_16") (pintype "bidirectional"))
    )
    (net (code "319") (name "VCC") (class "Default")
      (node (ref "C10") (pin "1") (pinfunction "1_1") (pintype "passive"))
      (node (ref "C18") (pin "1") (pinfunction "1_1") (pintype "passive"))
      (node (ref "C21") (pin "1") (pinfunction "1_1") (pintype "passive"))
      (node (ref "C3") (pin "1") (pinfunction "1_1") (pintype "passive"))
      (node (ref "C4") (pin "1") (pinfunction "1_1") (pintype "passive"))
      (node (ref "C5") (pin "1") (pinfunction "1_1") (pintype "passive"))
      (node (ref "C6") (pin "1") (pinfunction "1_1") (pintype "passive"))
      (node (ref "C7") (pin "1") (pinfunction "1_1") (pintype "passive"))
      (node (ref "C9") (pin "1") (pinfunction "1_1") (pintype "passive"))
      (node (ref "DCDC3.3V") (pin "3") (pinfunction "3_3") (pintype "passive"))
      (node (ref "ETH1") (pin "P$10") (pinfunction "3V3_1_P$10") (pintype "bidirectional"))
      (node (ref "ETH1") (pin "P$11") (pinfunction "3V3_2_P$11") (pintype "bidirectional"))
      (node (ref "IC1") (pin "14") (pinfunction "VCC_14") (pintype "power_in"))
      (node (ref "IC2") (pin "14") (pinfunction "VCC_14") (pintype "power_in"))
      (node (ref "IC3") (pin "14") (pinfunction "VCC_14") (pintype "power_in"))
      (node (ref "J10") (pin "P$1") (pinfunction "P$1_P$1") (pintype "bidirectional"))
      (node (ref "J10") (pin "P$2") (pinfunction "P$2_P$2") (pintype "bidirectional"))
      (node (ref "J10") (pin "P$3") (pinfunction "P$3_P$3") (pintype "bidirectional"))
      (node (ref "J123") (pin "P$1") (pinfunction "P$1_P$1") (pintype "bidirectional"))
      (node (ref "J123") (pin "P$2") (pinfunction "P$2_P$2") (pintype "bidirectional"))
      (node (ref "J123") (pin "P$3") (pinfunction "P$3_P$3") (pintype "bidirectional"))
      (node (ref "J177") (pin "P$1") (pinfunction "P$1_P$1") (pintype "bidirectional"))
      (node (ref "J177") (pin "P$2") (pinfunction "P$2_P$2") (pintype "bidirectional"))
      (node (ref "J177") (pin "P$3") (pinfunction "P$3_P$3") (pintype "bidirectional"))
      (node (ref "L1") (pin "P$1") (pinfunction "3.3V_1_P$1") (pintype "bidirectional"))
      (node (ref "L1") (pin "P$41") (pinfunction "3.3V_2_P$41") (pintype "bidirectional"))
      (node (ref "R10") (pin "1") (pinfunction "1_1") (pintype "passive"))
      (node (ref "R11") (pin "2") (pinfunction "2_2") (pintype "passive"))
      (node (ref "R12") (pin "2") (pinfunction "2_2") (pintype "passive"))
      (node (ref "R13") (pin "2") (pinfunction "2_2") (pintype "passive"))
      (node (ref "R14") (pin "2") (pinfunction "2_2") (pintype "passive"))
      (node (ref "R15") (pin "2") (pinfunction "2_2") (pintype "passive"))
      (node (ref "R16") (pin "2") (pinfunction "2_2") (pintype "passive"))
      (node (ref "R17") (pin "2") (pinfunction "2_2") (pintype "passive"))
      (node (ref "R18") (pin "2") (pinfunction "2_2") (pintype "passive"))
      (node (ref "R19") (pin "2") (pinfunction "2_2") (pintype "passive"))
      (node (ref "R20") (pin "2") (pinfunction "2_2") (pintype "passive"))
      (node (ref "R21") (pin "2") (pinfunction "2_2") (pintype "passive"))
      (node (ref "R22") (pin "2") (pinfunction "2_2") (pintype "passive"))
      (node (ref "R23") (pin "2") (pinfunction "2_2") (pintype "passive"))
      (node (ref "R24") (pin "2") (pinfunction "2_2") (pintype "passive"))
      (node (ref "R25") (pin "2") (pinfunction "2_2") (pintype "passive"))
      (node (ref "R27") (pin "2") (pinfunction "2_2") (pintype "passive"))
      (node (ref "R28") (pin "2") (pinfunction "2_2") (pintype "passive"))
      (node (ref "R29") (pin "2") (pinfunction "2_2") (pintype "passive"))
      (node (ref "R30") (pin "2") (pinfunction "2_2") (pintype "passive"))
      (node (ref "R31") (pin "2") (pinfunction "2_2") (pintype "passive"))
      (node (ref "R33") (pin "1") (pinfunction "1_1") (pintype "passive"))
      (node (ref "R34") (pin "1") (pinfunction "1_1") (pintype "passive"))
      (node (ref "R35") (pin "1") (pinfunction "1_1") (pintype "passive"))
      (node (ref "R36") (pin "2") (pinfunction "2_2") (pintype "passive"))
      (node (ref "R37") (pin "2") (pinfunction "2_2") (pintype "passive"))
      (node (ref "R38") (pin "2") (pinfunction "2_2") (pintype "passive"))
      (node (ref "R39") (pin "2") (pinfunction "2_2") (pintype "passive"))
      (node (ref "R4") (pin "2") (pinfunction "2_2") (pintype "passive"))
      (node (ref "R42") (pin "1") (pinfunction "1_1") (pintype "passive"))
      (node (ref "R44") (pin "1") (pinfunction "1_1") (pintype "passive"))
      (node (ref "R5") (pin "2") (pinfunction "2_2") (pintype "passive"))
      (node (ref "R6") (pin "2") (pinfunction "2_2") (pintype "passive"))
      (node (ref "R8") (pin "2") (pinfunction "2_2") (pintype "passive"))
      (node (ref "R9") (pin "1") (pinfunction "1_1") (pintype "passive"))
      (node (ref "S53") (pin "P$1") (pinfunction "P$1_P$1") (pintype "bidirectional"))
      (node (ref "S53") (pin "P$10") (pinfunction "P$10_P$10") (pintype "bidirectional"))
      (node (ref "S53") (pin "P$2") (pinfunction "P$2_P$2") (pintype "bidirectional"))
      (node (ref "S53") (pin "P$3") (pinfunction "P$3_P$3") (pintype "bidirectional"))
      (node (ref "S53") (pin "P$4") (pinfunction "P$4_P$4") (pintype "bidirectional"))
      (node (ref "S53") (pin "P$5") (pinfunction "P$5_P$5") (pintype "bidirectional"))
      (node (ref "S53") (pin "P$6") (pinfunction "P$6_P$6") (pintype "bidirectional"))
      (node (ref "S53") (pin "P$7") (pinfunction "P$7_P$7") (pintype "bidirectional"))
      (node (ref "S53") (pin "P$8") (pinfunction "P$8_P$8") (pintype "bidirectional"))
      (node (ref "S53") (pin "P$9") (pinfunction "P$9_P$9") (pintype "bidirectional"))
      (node (ref "S58") (pin "P$1") (pinfunction "P$1_P$1") (pintype "bidirectional"))
      (node (ref "S58") (pin "P$10") (pinfunction "P$10_P$10") (pintype "bidirectional"))
      (node (ref "S58") (pin "P$2") (pinfunction "P$2_P$2") (pintype "bidirectional"))
      (node (ref "S58") (pin "P$3") (pinfunction "P$3_P$3") (pintype "bidirectional"))
      (node (ref "S58") (pin "P$4") (pinfunction "P$4_P$4") (pintype "bidirectional"))
      (node (ref "S58") (pin "P$5") (pinfunction "P$5_P$5") (pintype "bidirectional"))
      (node (ref "S58") (pin "P$6") (pinfunction "P$6_P$6") (pintype "bidirectional"))
      (node (ref "S58") (pin "P$7") (pinfunction "P$7_P$7") (pintype "bidirectional"))
      (node (ref "S58") (pin "P$8") (pinfunction "P$8_P$8") (pintype "bidirectional"))
      (node (ref "S58") (pin "P$9") (pinfunction "P$9_P$9") (pintype "bidirectional"))
      (node (ref "SV11") (pin "2") (pinfunction "2_2") (pintype "passive"))
      (node (ref "SV12") (pin "2") (pinfunction "2_2") (pintype "passive"))
      (node (ref "SV13") (pin "3") (pinfunction "3_3") (pintype "passive"))
      (node (ref "SV13") (pin "7") (pinfunction "7_7") (pintype "passive"))
      (node (ref "SV14") (pin "5") (pinfunction "5_5") (pintype "passive"))
      (node (ref "SV16") (pin "1") (pinfunction "1_1") (pintype "passive"))
      (node (ref "SV16") (pin "2") (pinfunction "2_2") (pintype "passive"))
      (node (ref "SV18") (pin "1") (pinfunction "1_1") (pintype "passive"))
      (node (ref "SV6") (pin "1") (pinfunction "1_1") (pintype "passive"))
      (node (ref "SV6") (pin "2") (pinfunction "2_2") (pintype "passive"))
      (node (ref "TRIMPOT1") (pin "1") (pinfunction "1_1") (pintype "passive"))
      (node (ref "TRIMPOT1") (pin "2") (pinfunction "2_2") (pintype "passive"))
      (node (ref "TRIMPOT2") (pin "1") (pinfunction "1_1") (pintype "passive"))
      (node (ref "TRIMPOT2") (pin "2") (pinfunction "2_2") (pintype "passive"))
      (node (ref "U$1") (pin "1") (pinfunction "P1_VCC_1") (pintype "bidirectional"))
      (node (ref "U1") (pin "2") (pinfunction "REF_2") (pintype "bidirectional"))
      (node (ref "U1") (pin "6") (pinfunction "VCC_6") (pintype "bidirectional"))
      (node (ref "U3") (pin "8") (pinfunction "P8_VCC_8") (pintype "bidirectional"))
      (node (ref "U5") (pin "2") (pinfunction "REF_2") (pintype "bidirectional"))
      (node (ref "U5") (pin "6") (pinfunction "VCC_6") (pintype "bidirectional"))
      (node (ref "U6") (pin "P$8") (pinfunction "V+_P$8") (pintype "bidirectional"))
      (node (ref "U7") (pin "8") (pinfunction "VCC_8") (pintype "bidirectional"))
      (node (ref "U8") (pin "22") (pinfunction "VDDA_22") (pintype "bidirectional"))
      (node (ref "U8") (pin "4") (pinfunction "VDDIO_4") (pintype "bidirectional"))
    )
    (net (code "320") (name "unconnected-(ETH1-NC-PadP$9)") (class "Default")
      (node (ref "ETH1") (pin "P$9") (pinfunction "NC_P$9") (pintype "bidirectional"))
    )
    (net (code "321") (name "unconnected-(G1-+-Pad+@1)") (class "Default")
      (node (ref "G1") (pin "+@1") (pinfunction "+_+@1") (pintype "passive"))
    )
    (net (code "322") (name "unconnected-(J8-PadP$1)") (class "Default")
      (node (ref "J8") (pin "P$1") (pinfunction "P$1_P$1") (pintype "bidirectional"))
    )
    (net (code "323") (name "unconnected-(J8-PadP$2)") (class "Default")
      (node (ref "J8") (pin "P$2") (pinfunction "P$2_P$2") (pintype "bidirectional"))
    )
    (net (code "324") (name "unconnected-(SV12-Pad3)") (class "Default")
      (node (ref "SV12") (pin "3") (pinfunction "3_3") (pintype "passive"))
    )
    (net (code "325") (name "unconnected-(SV12-Pad5)") (class "Default")
      (node (ref "SV12") (pin "5") (pinfunction "5_5") (pintype "passive"))
    )
    (net (code "326") (name "unconnected-(SV13-Pad4)") (class "Default")
      (node (ref "SV13") (pin "4") (pinfunction "4_4") (pintype "passive"))
    )
    (net (code "327") (name "unconnected-(SV13-Pad6)") (class "Default")
      (node (ref "SV13") (pin "6") (pinfunction "6_6") (pintype "passive"))
    )
    (net (code "328") (name "unconnected-(SV14-Pad6)") (class "Default")
      (node (ref "SV14") (pin "6") (pinfunction "6_6") (pintype "passive"))
    )
    (net (code "329") (name "unconnected-(SV14-Pad13)") (class "Default")
      (node (ref "SV14") (pin "13") (pinfunction "13_13") (pintype "passive"))
    )
    (net (code "330") (name "unconnected-(SV14-Pad14)") (class "Default")
      (node (ref "SV14") (pin "14") (pinfunction "14_14") (pintype "passive"))
    )
    (net (code "331") (name "unconnected-(U7-DNU-Pad3)") (class "Default")
      (node (ref "U7") (pin "3") (pinfunction "DNU_3") (pintype "bidirectional"))
    )
    (net (code "332") (name "unconnected-(U8-TEST-Pad38)") (class "Default")
      (node (ref "U8") (pin "38") (pinfunction "TEST_38") (pintype "bidirectional"))
    )
  )
)
